# dsp_ice_rev2_release.net
KiCad netlist of a schematic drawn in EAGLE
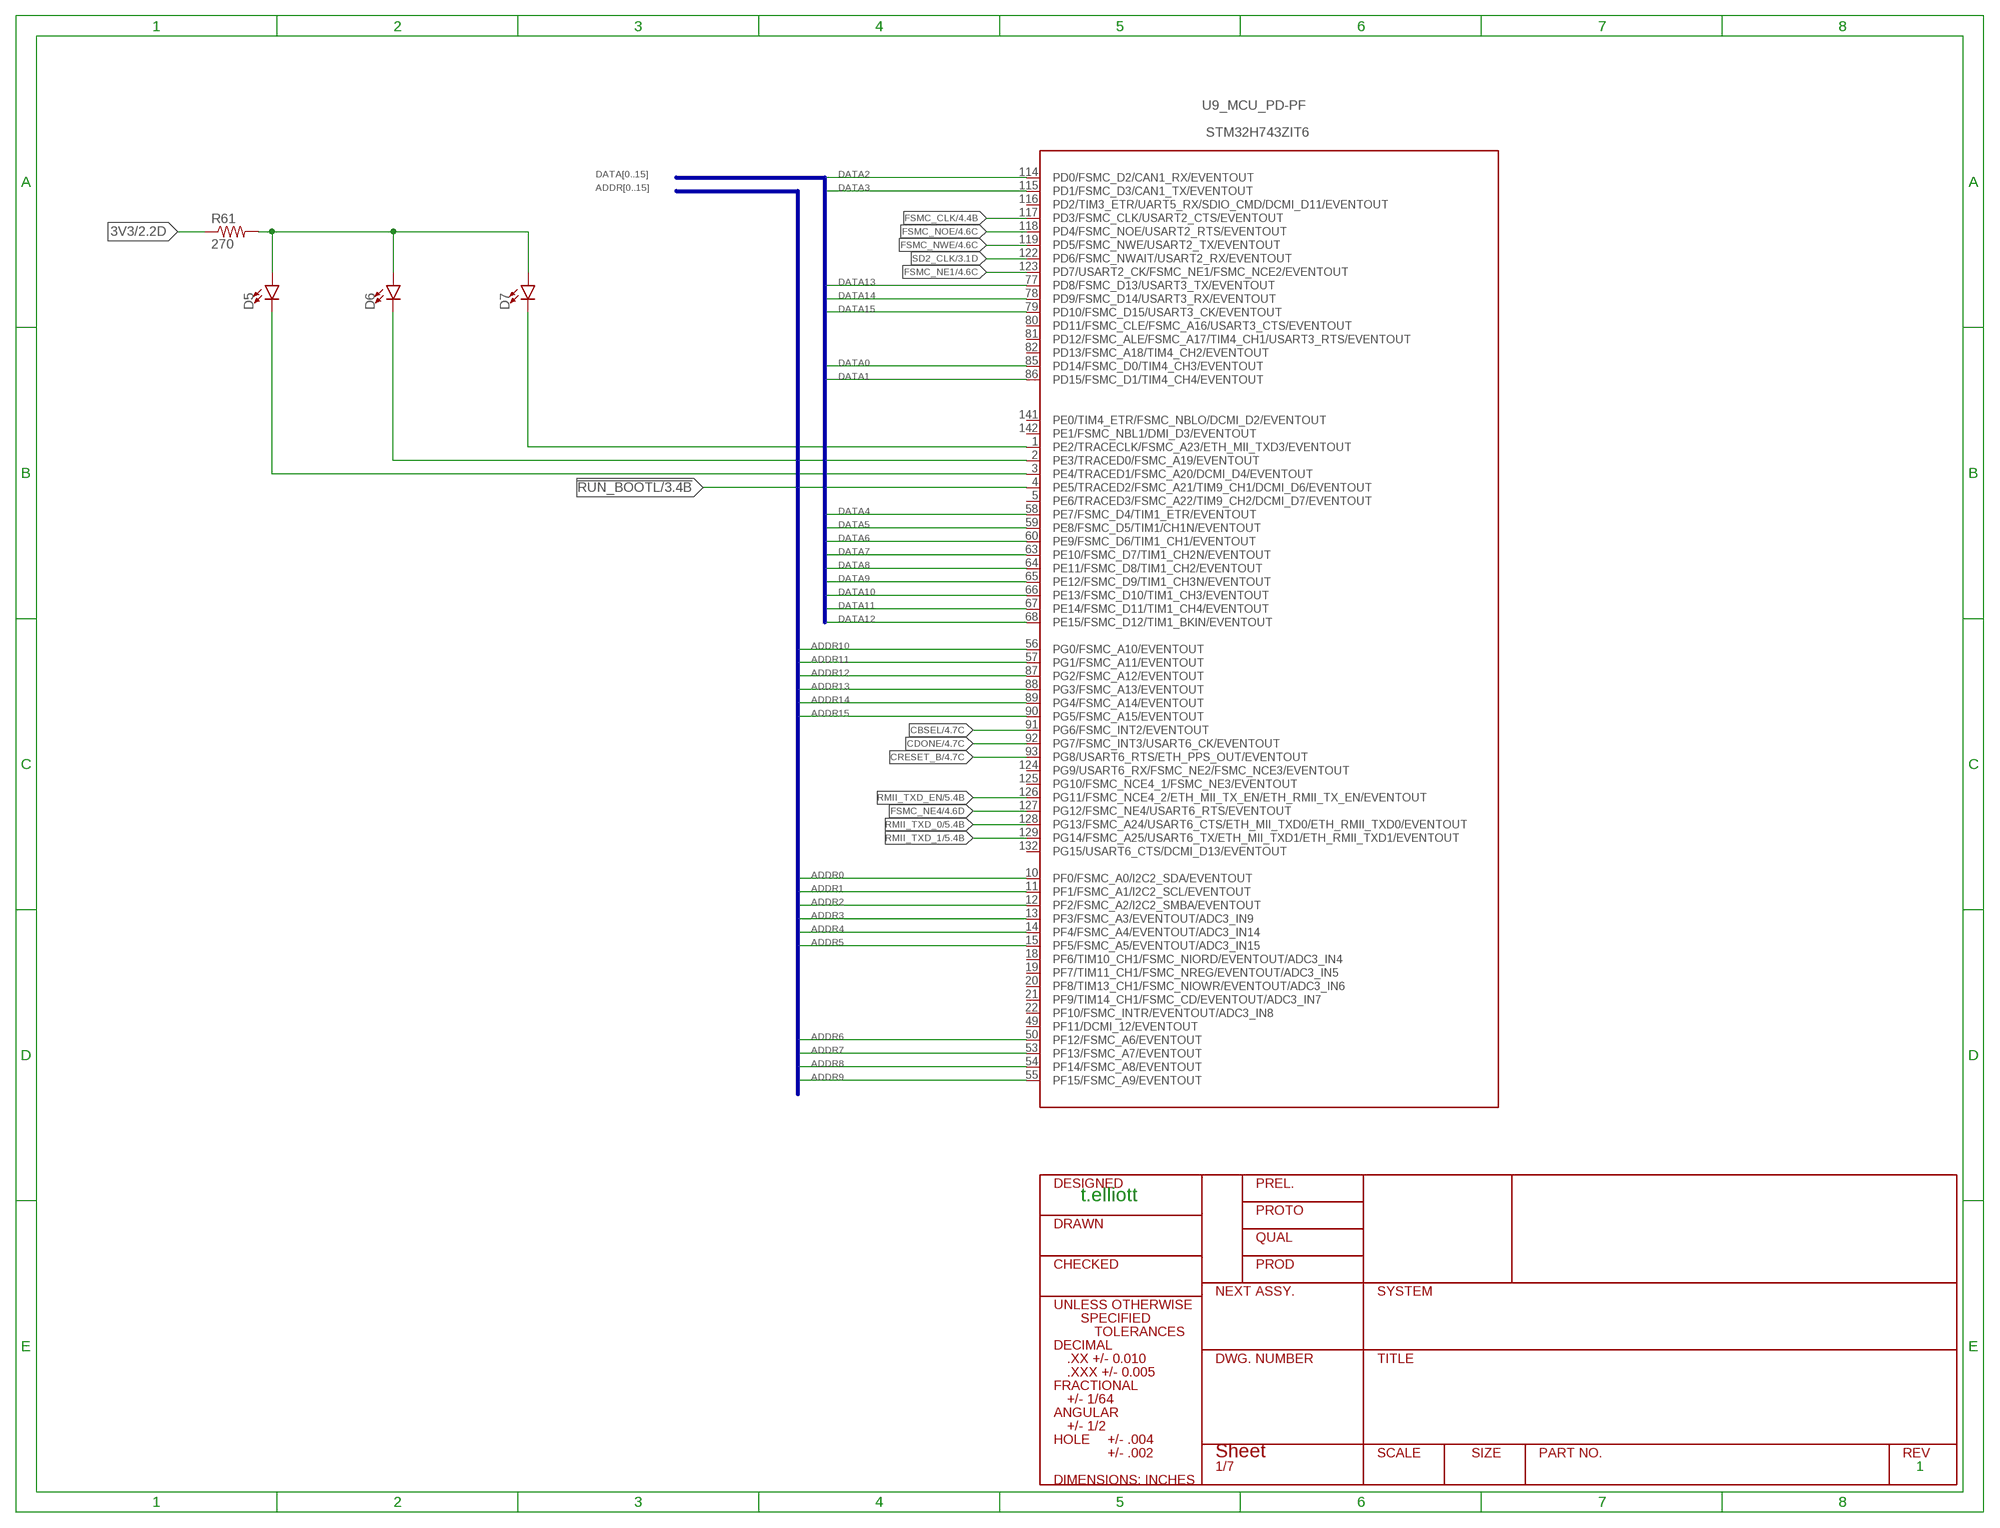
[diagram p0: schematic, sheet 1]
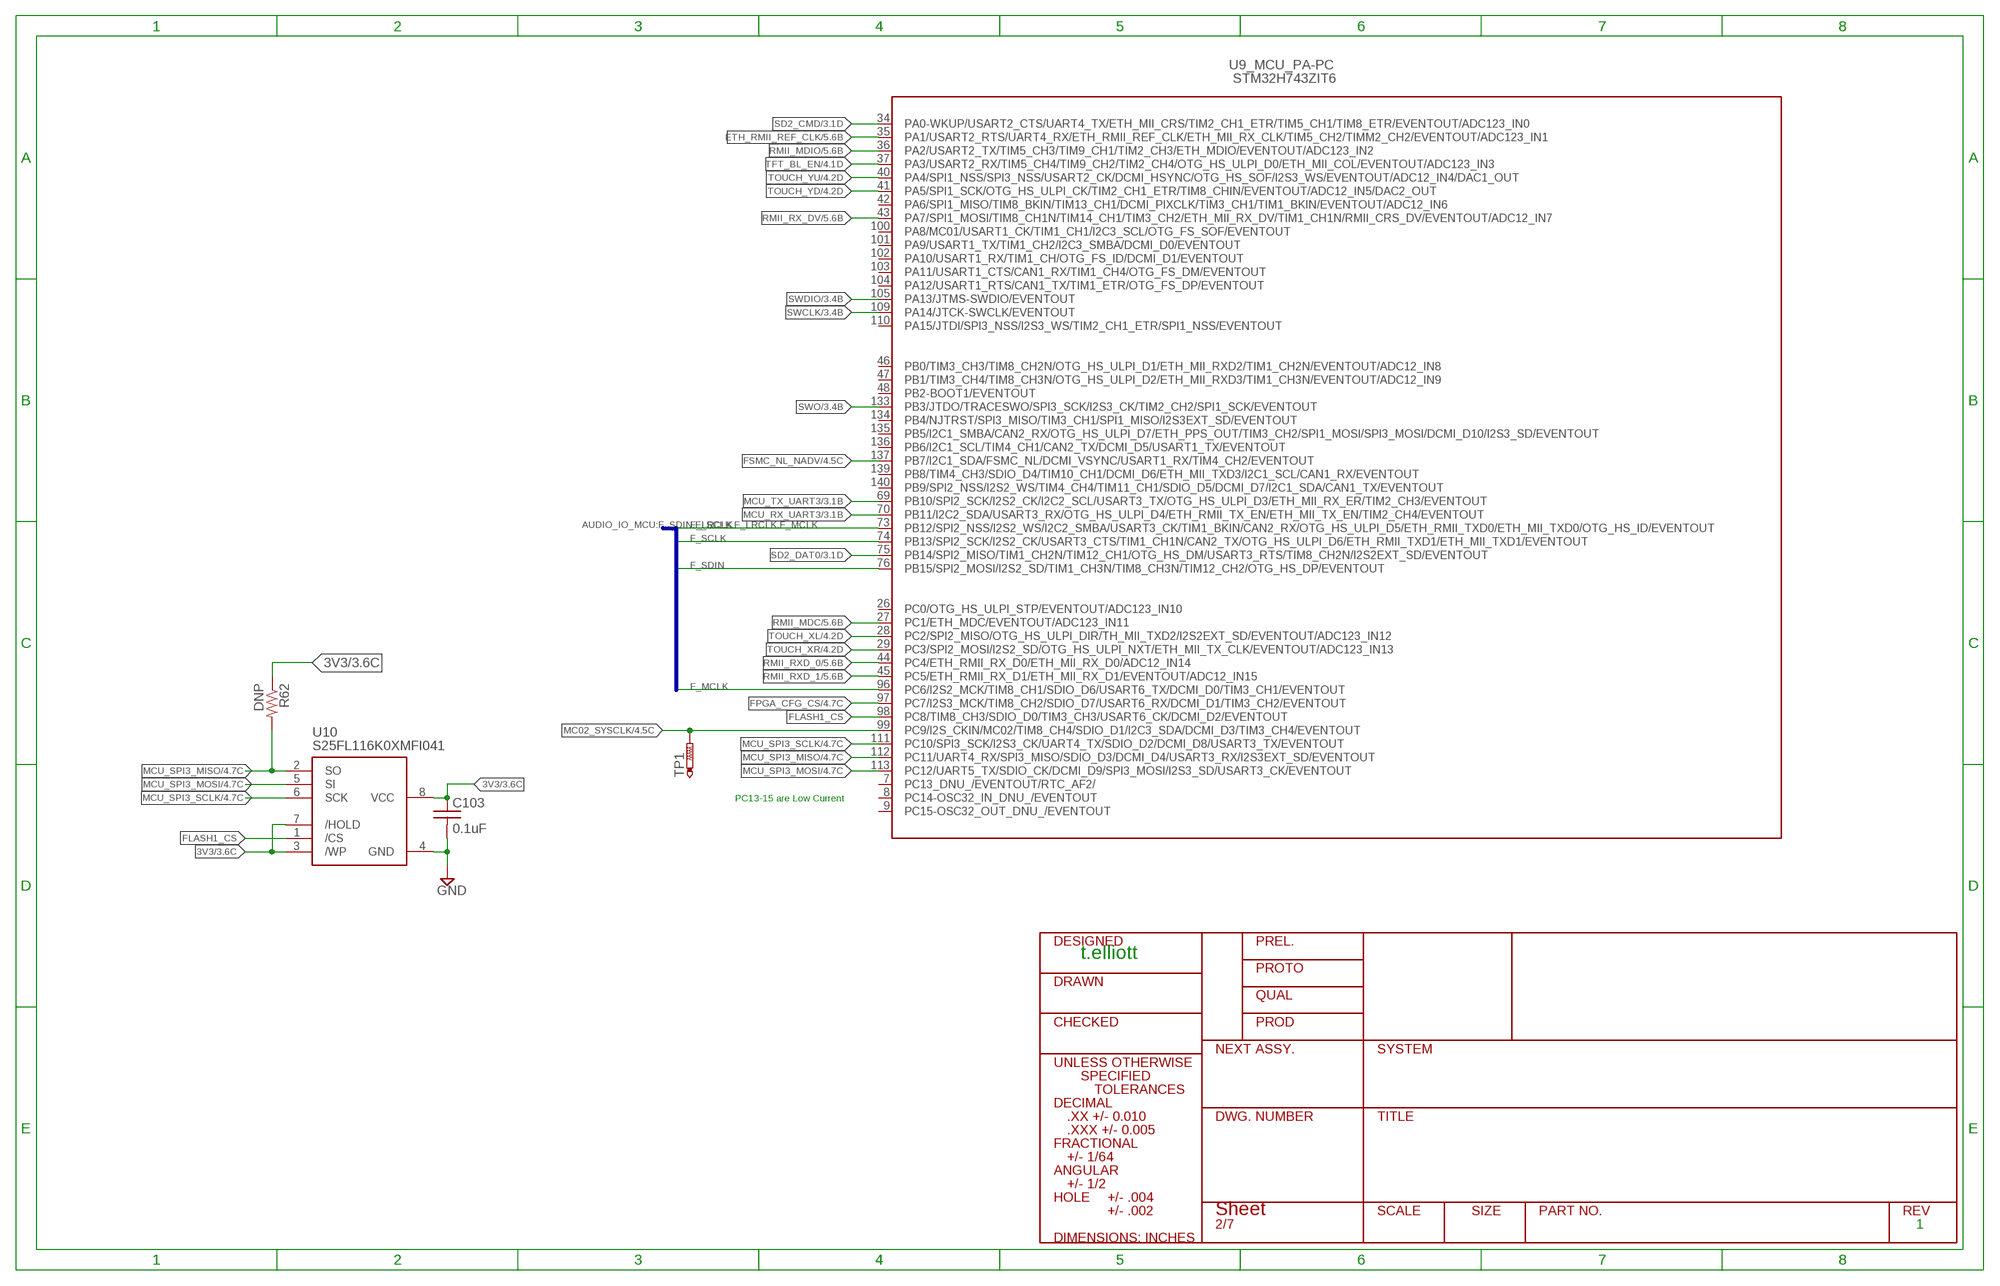
[diagram p1: schematic, sheet 2]
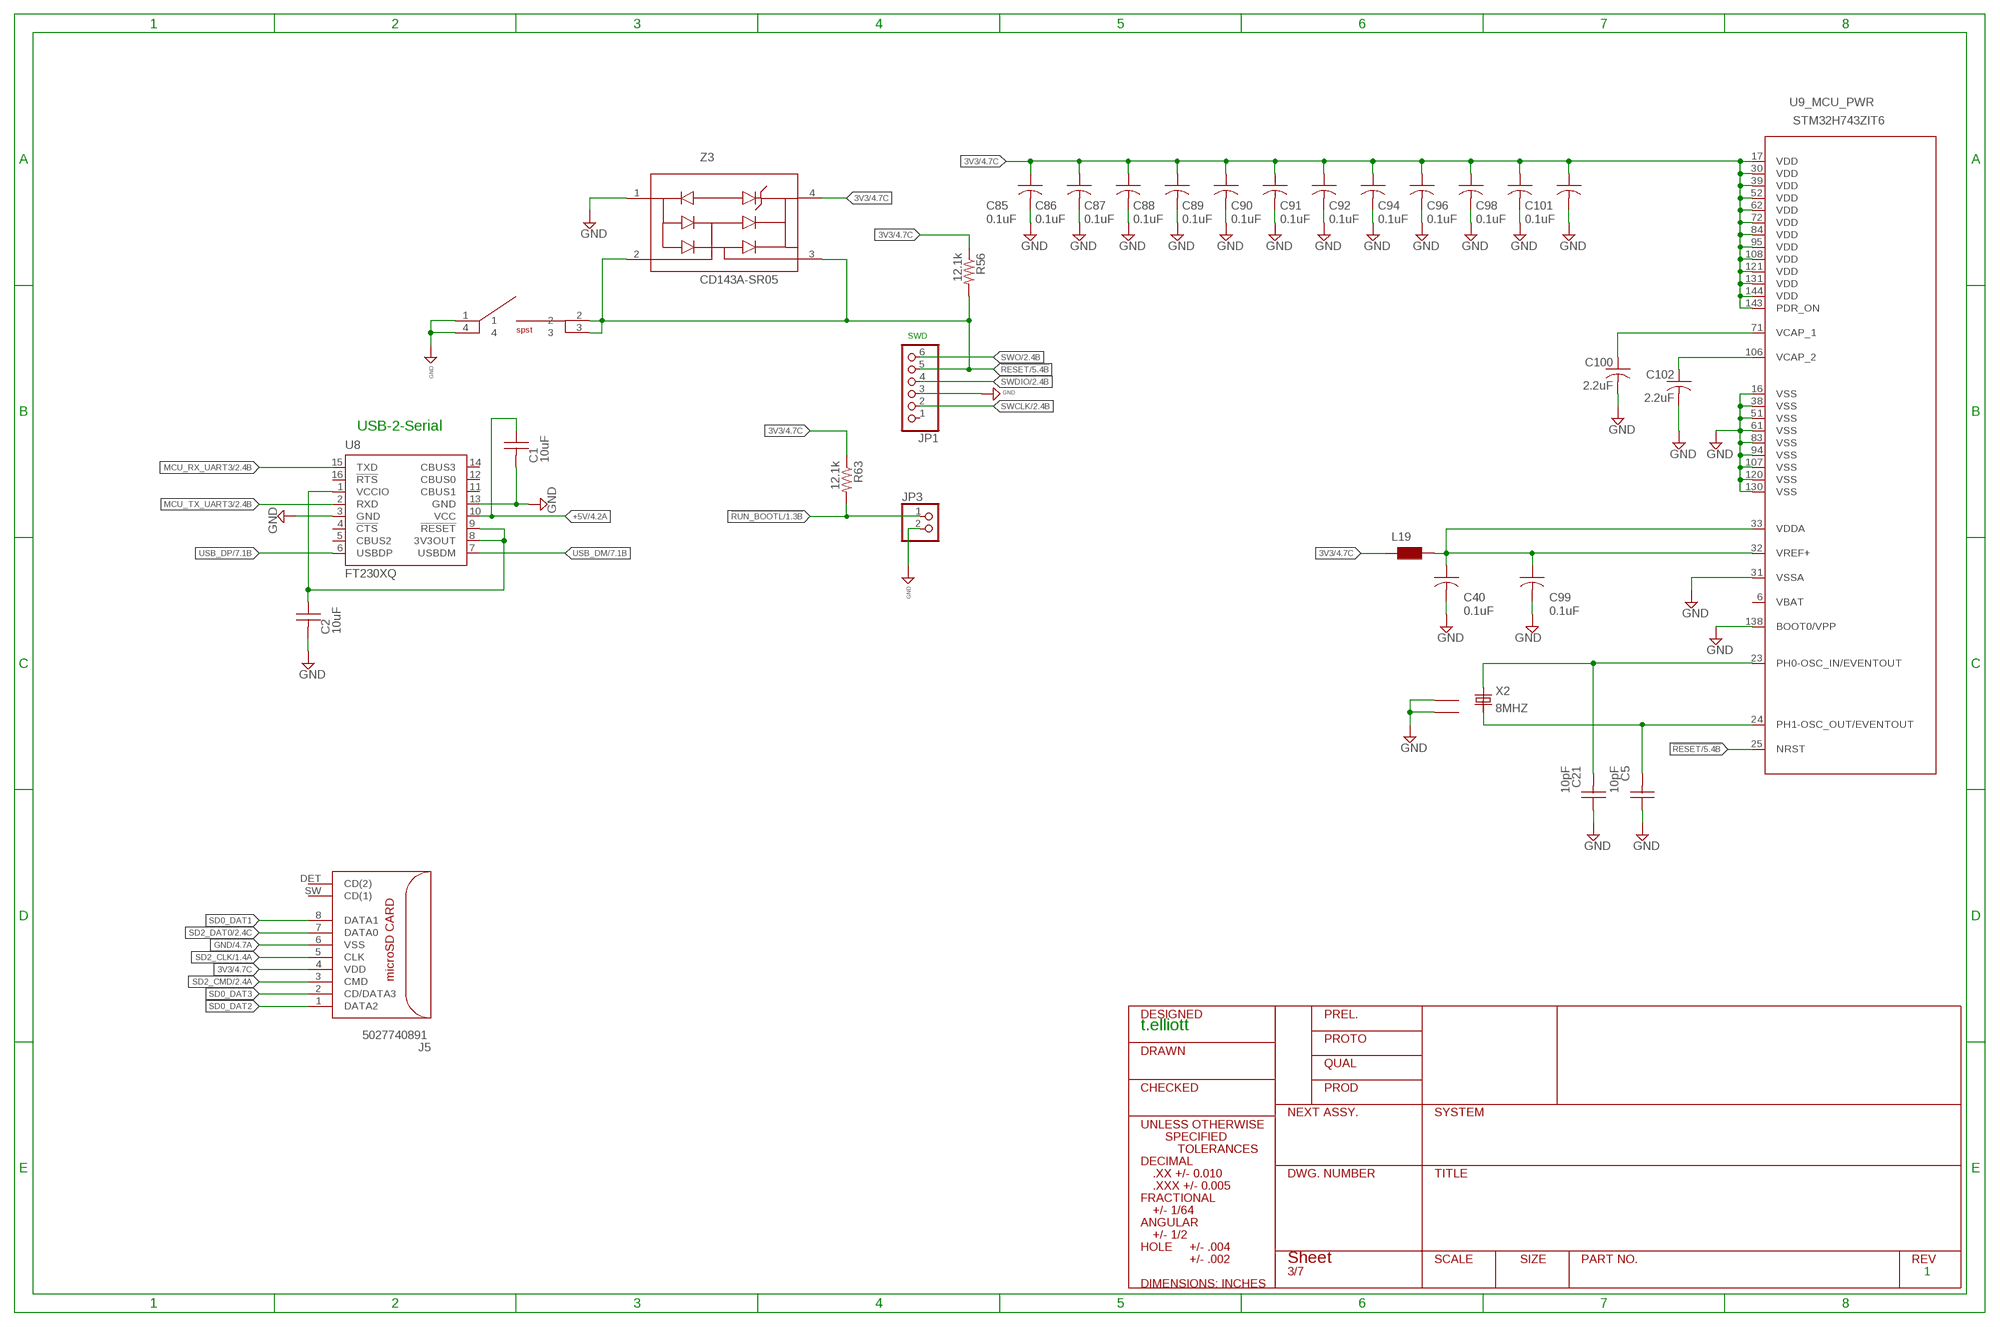
[diagram p2: schematic, sheet 3]
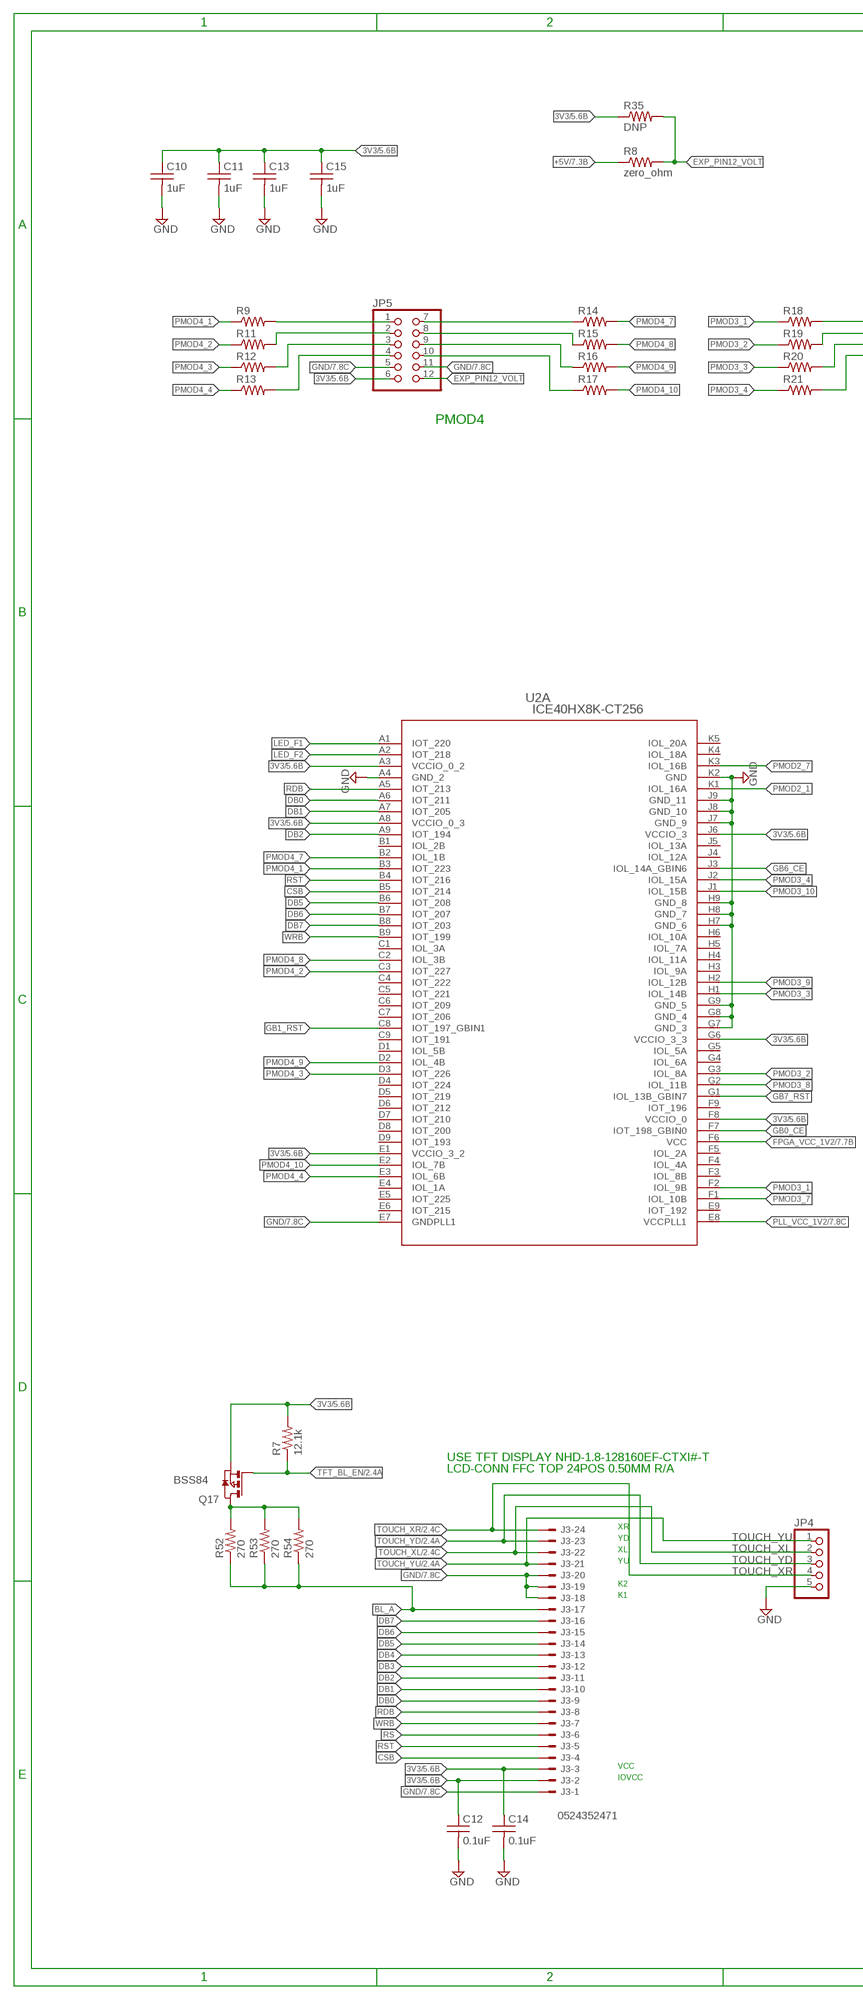
[diagram p3: schematic, sheet 4, part 1 of 2]
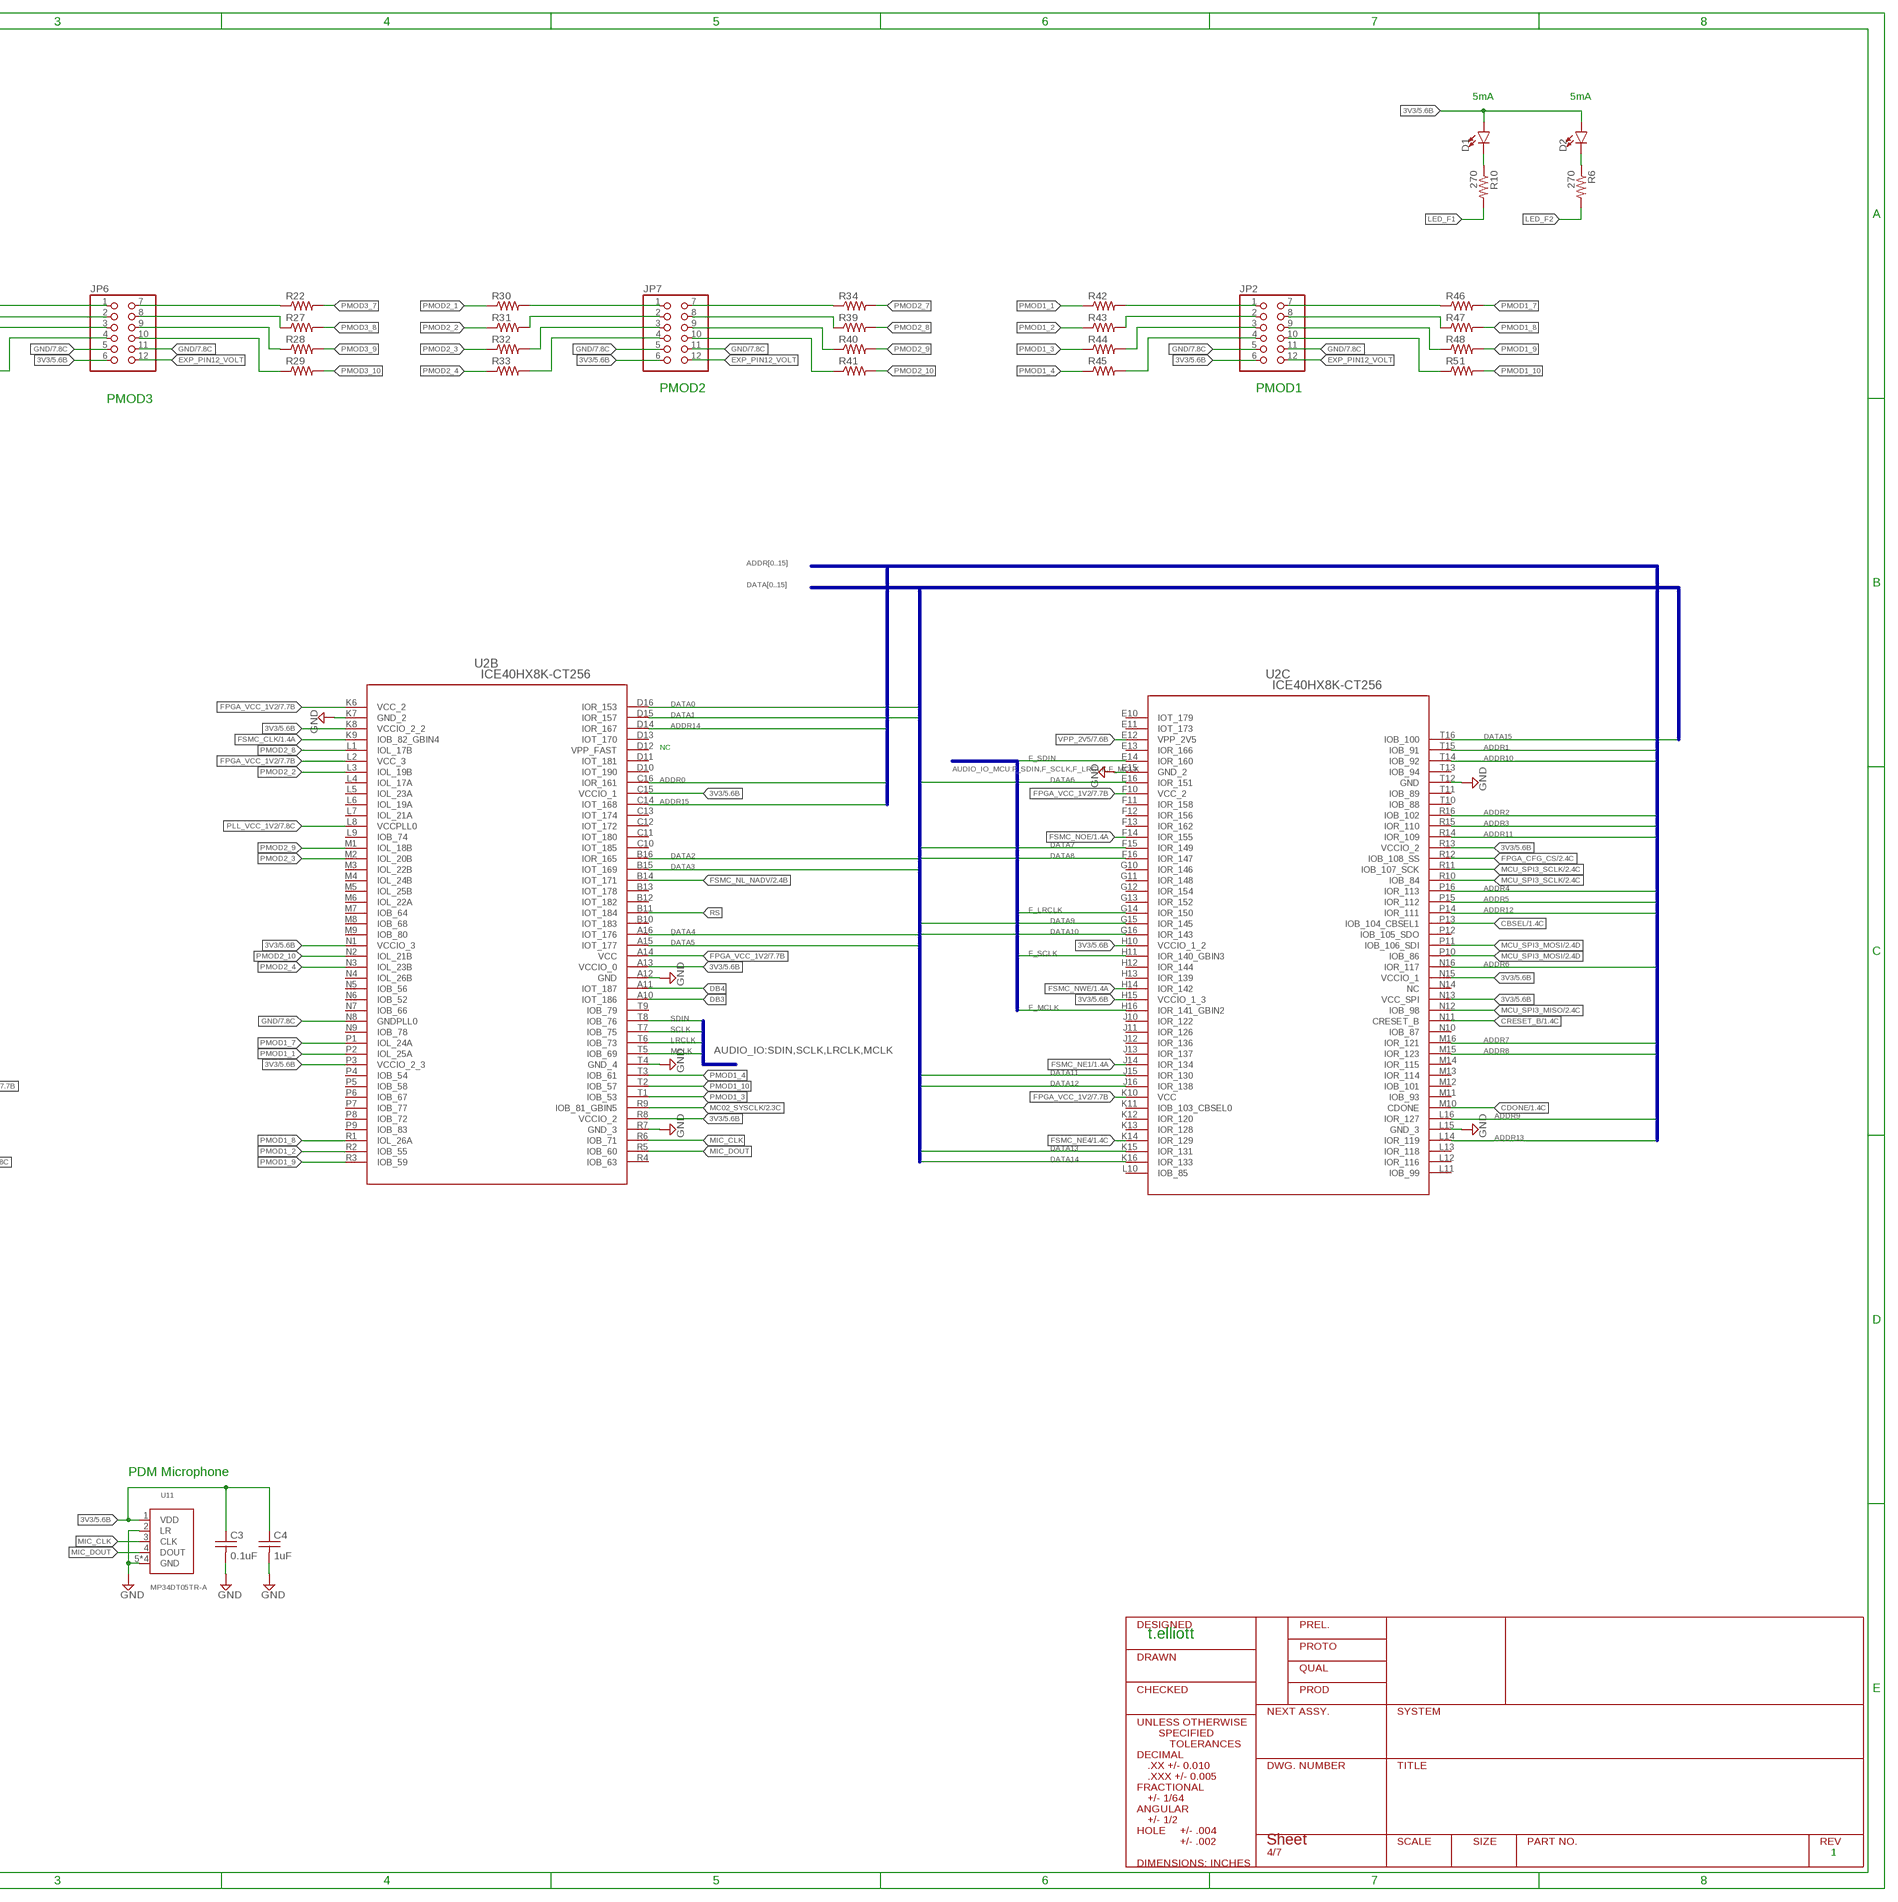
[diagram p4: schematic, sheet 4, part 2 of 2]
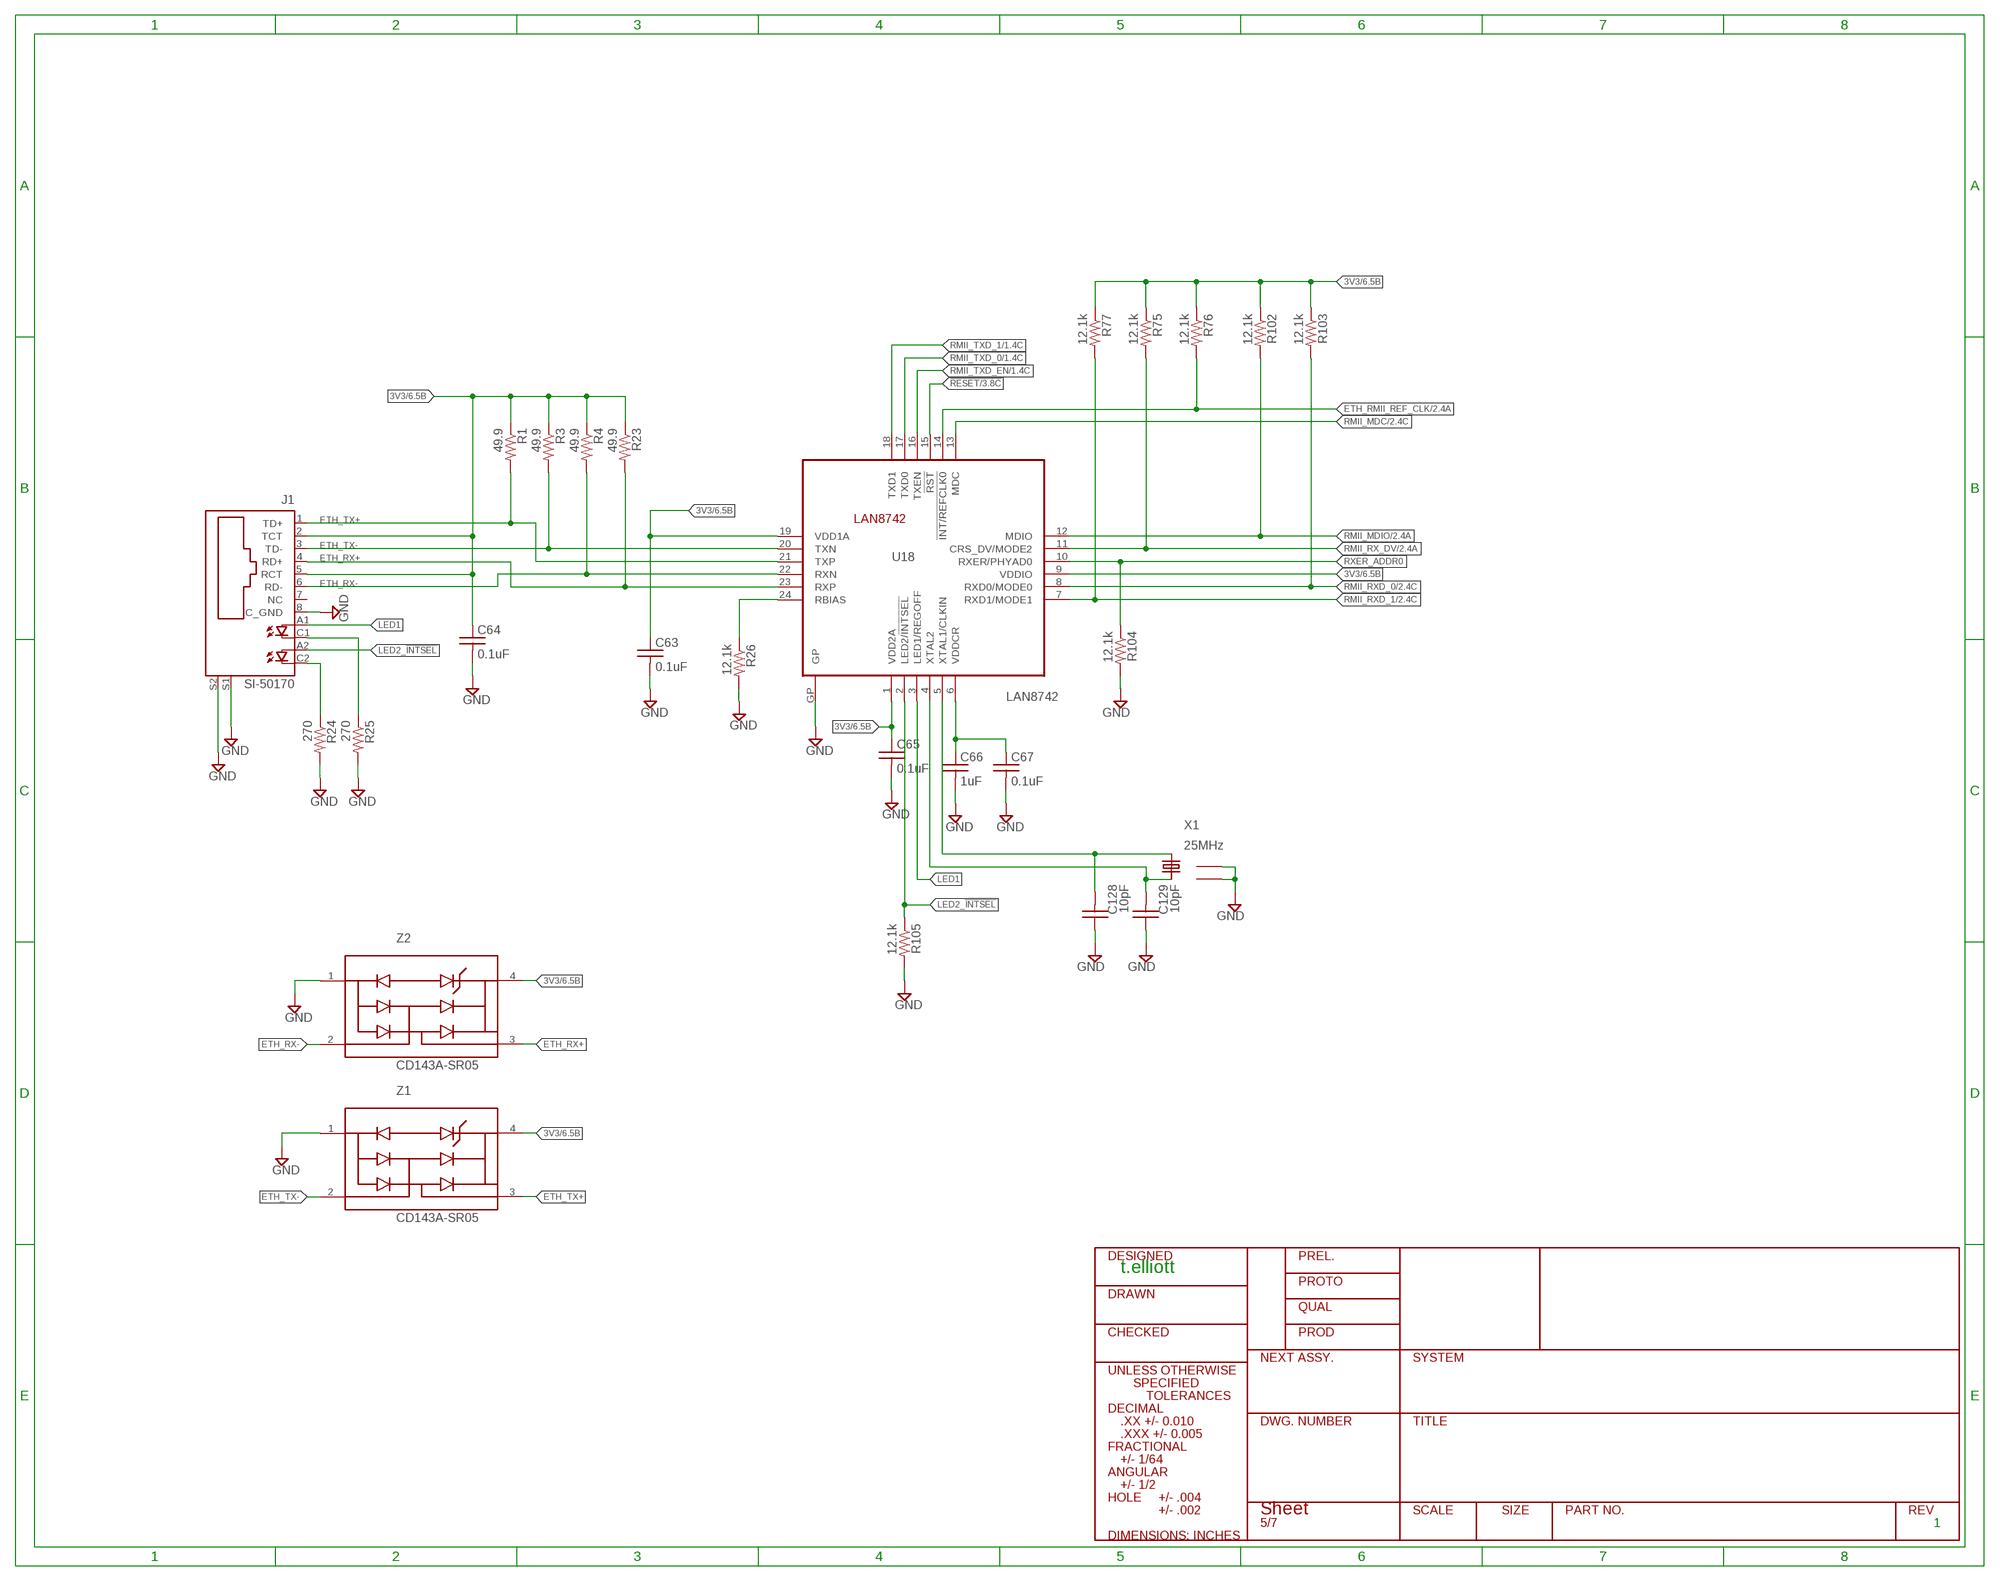
[diagram p5: schematic, sheet 5]
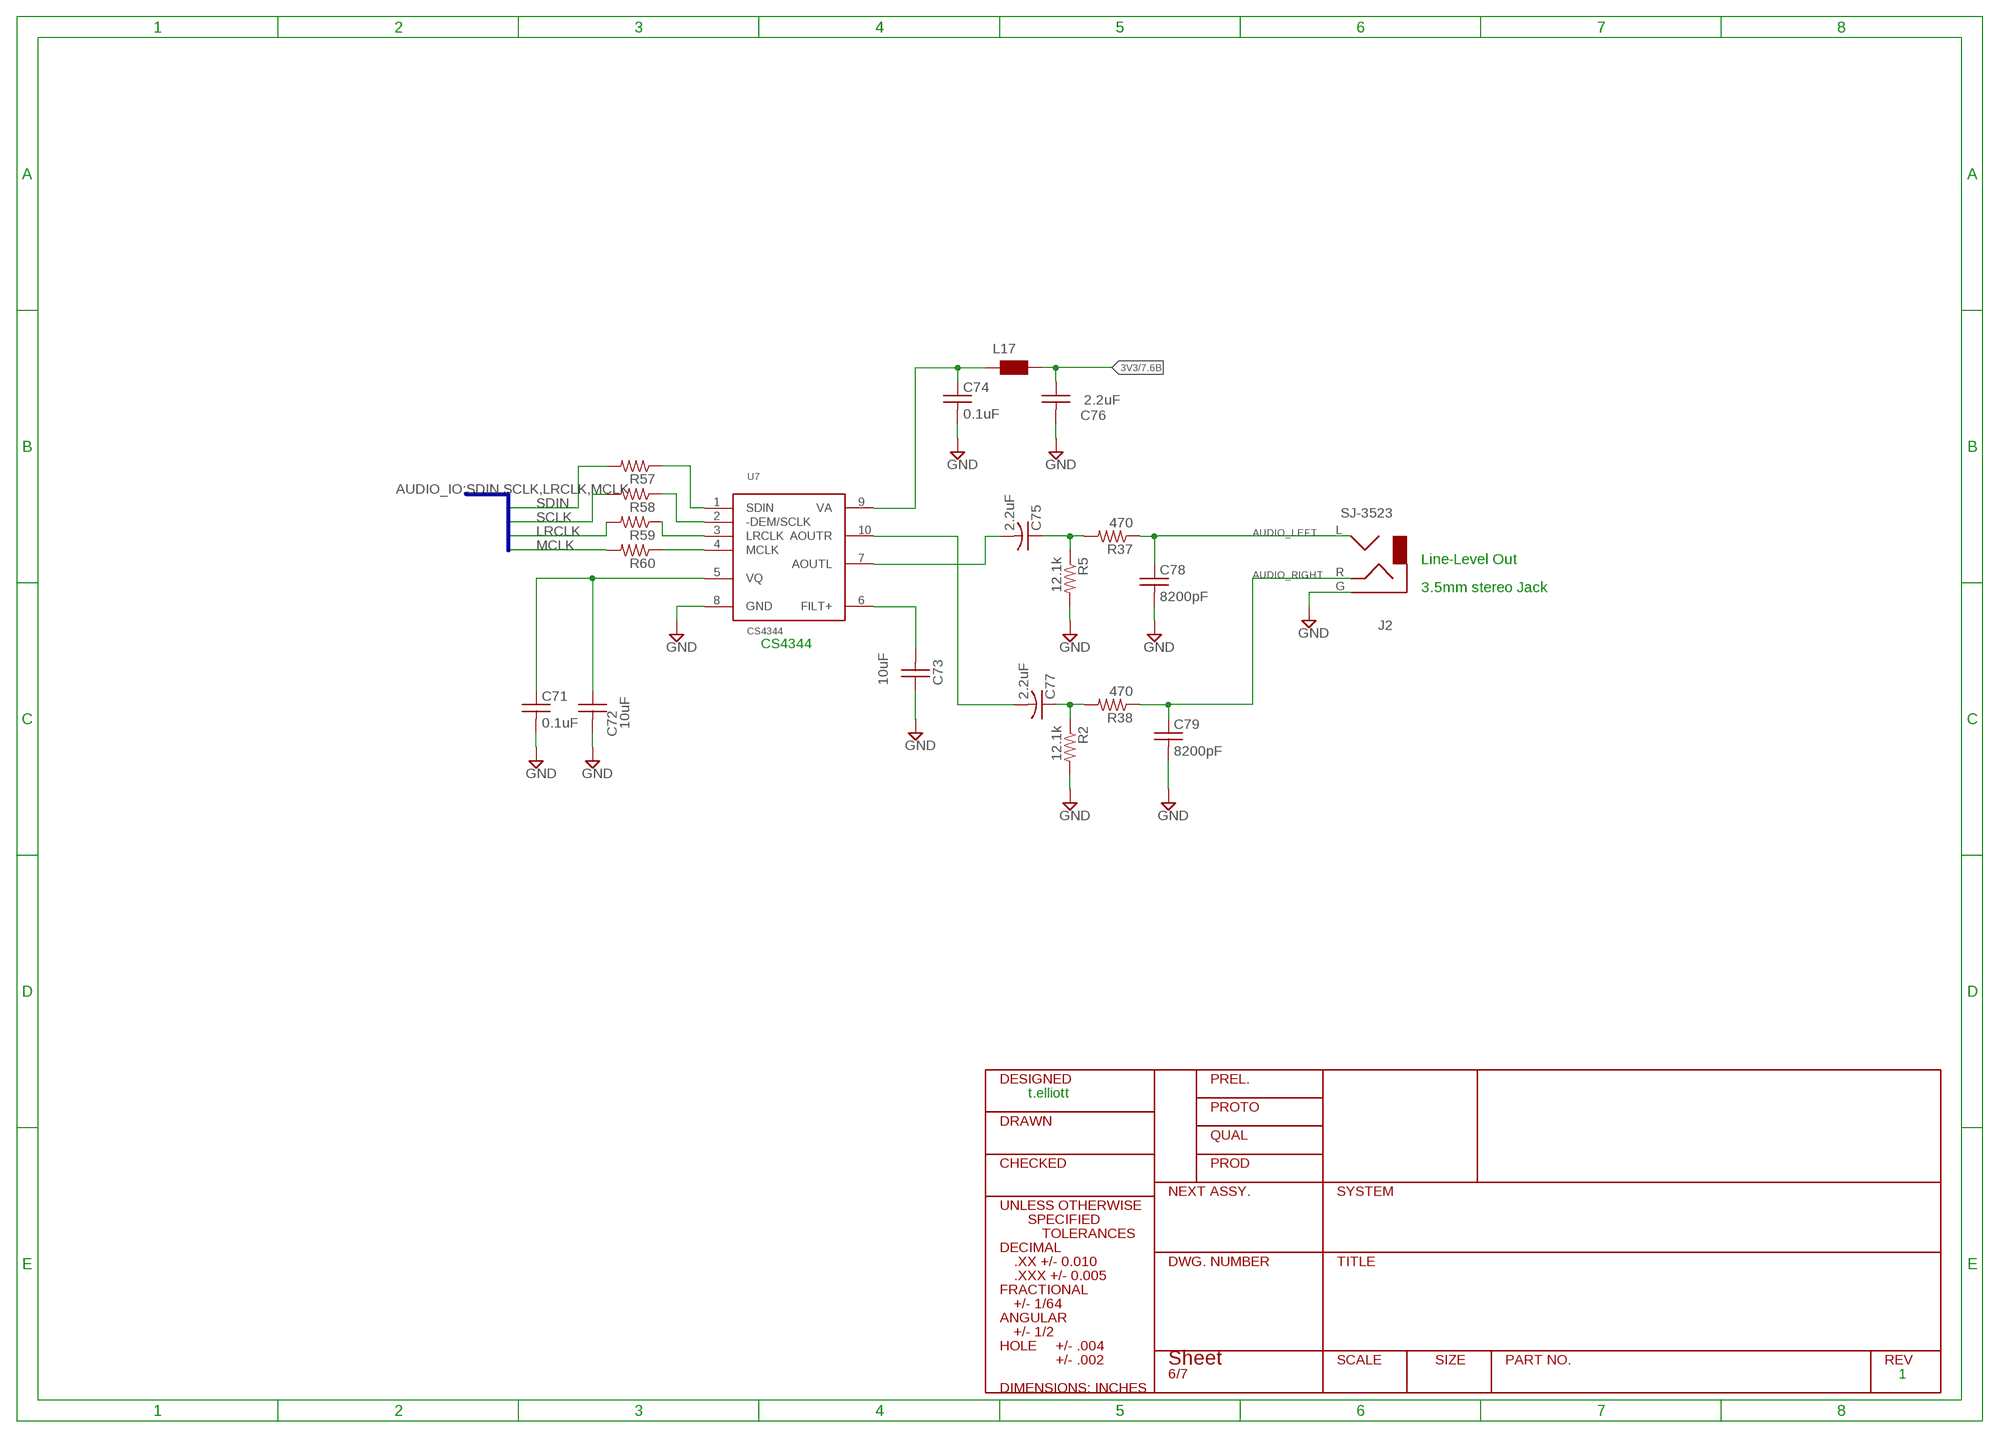
[diagram p6: schematic, sheet 6]
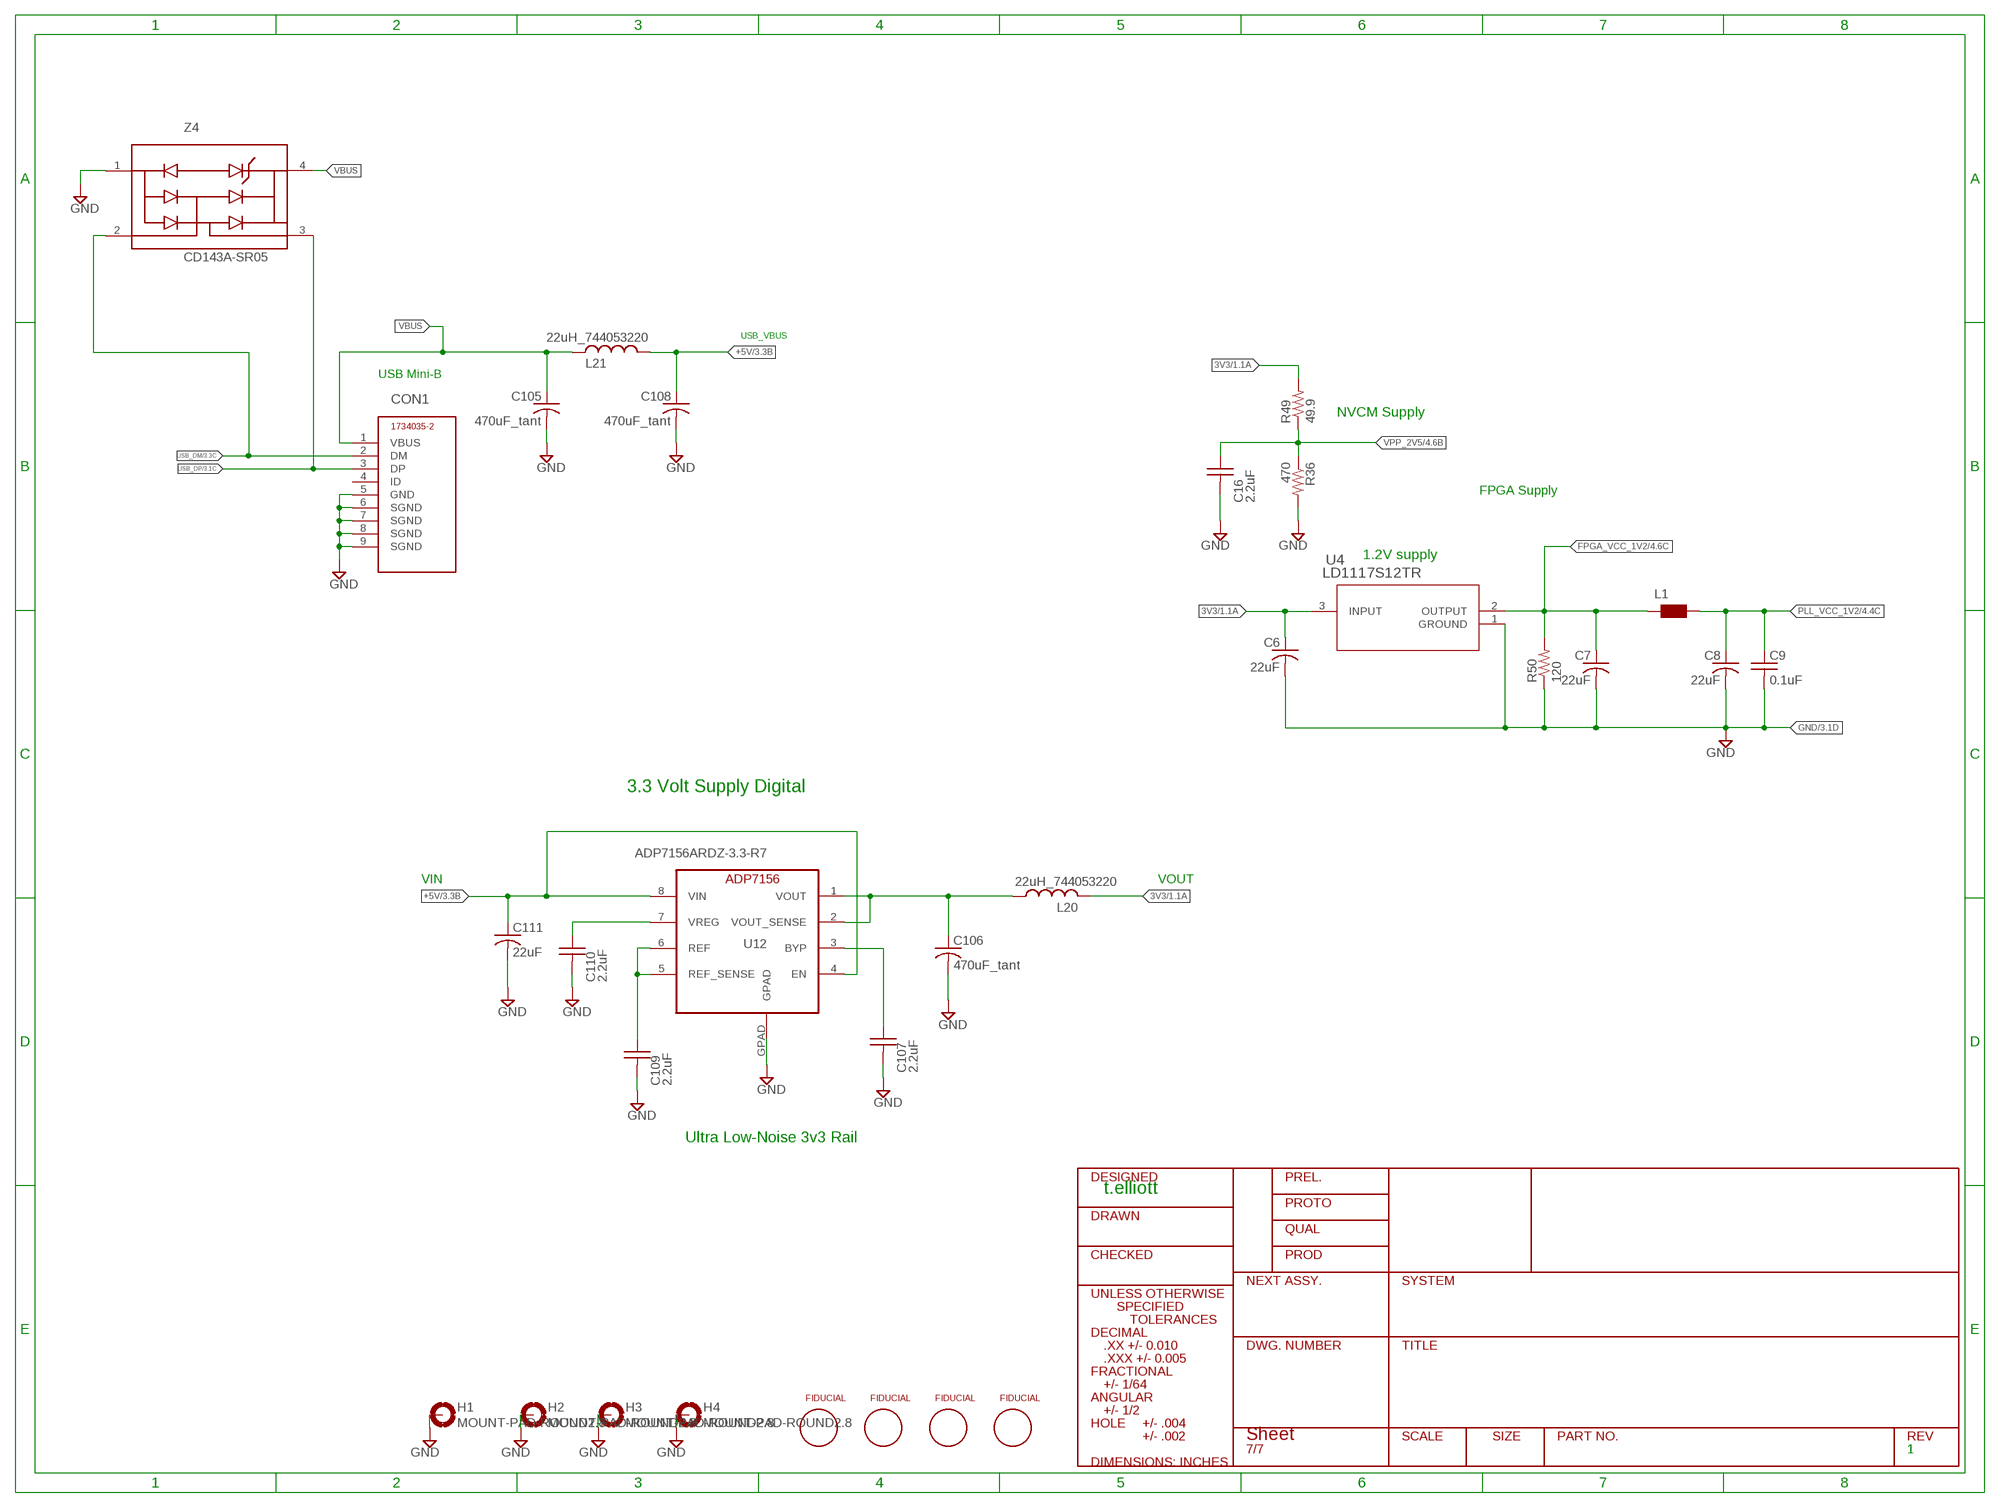
[diagram p7: schematic, sheet 7]

(export (version "E")
  (design (tool "Eeschema 10.0.6"))
  (components
    (comp (ref "C3")
      (value "0.1uF")
      (footprint "eagle-import:C0603")
      (libsource (lib "eagle-import") (part "C-USC0603"))
    )
    (comp (ref "C4")
      (value "1uF")
      (footprint "eagle-import:C0603")
      (libsource (lib "eagle-import") (part "C-USC0603"))
    )
    (comp (ref "C10")
      (value "1uF")
      (footprint "eagle-import:C0603")
      (libsource (lib "eagle-import") (part "C-USC0603"))
    )
    (comp (ref "C11")
      (value "1uF")
      (footprint "eagle-import:C0603")
      (libsource (lib "eagle-import") (part "C-USC0603"))
    )
    (comp (ref "C12")
      (value "0.1uF")
      (footprint "eagle-import:C0603")
      (libsource (lib "eagle-import") (part "C-USC0603"))
    )
    (comp (ref "C13")
      (value "1uF")
      (footprint "eagle-import:C0603")
      (libsource (lib "eagle-import") (part "C-USC0603"))
    )
    (comp (ref "C14")
      (value "0.1uF")
      (footprint "eagle-import:C0603")
      (libsource (lib "eagle-import") (part "C-USC0603"))
    )
    (comp (ref "C15")
      (value "1uF")
      (footprint "eagle-import:C0603")
      (libsource (lib "eagle-import") (part "C-USC0603"))
    )
    (comp (ref "D1")
      (value "LED1206")
      (footprint "eagle-import:LED-1206")
      (libsource (lib "eagle-import") (part "LED1206"))
    )
    (comp (ref "D2")
      (value "LED1206")
      (footprint "eagle-import:LED-1206")
      (libsource (lib "eagle-import") (part "LED1206"))
    )
    (comp (ref "J3")
      (value "0524352471")
      (footprint "eagle-import:52745-2490")
      (libsource (lib "eagle-import") (part "52745-2490"))
    )
    (comp (ref "JP2")
      (value "PINHD-2X6")
      (footprint "eagle-import:2X06")
      (libsource (lib "eagle-import") (part "PINHD-2X6"))
    )
    (comp (ref "JP4")
      (value "PINHD-1X5")
      (footprint "eagle-import:1X05")
      (libsource (lib "eagle-import") (part "PINHD-1X5"))
    )
    (comp (ref "JP5")
      (value "PINHD-2X6")
      (footprint "eagle-import:2X06")
      (libsource (lib "eagle-import") (part "PINHD-2X6"))
    )
    (comp (ref "JP6")
      (value "PINHD-2X6")
      (footprint "eagle-import:2X06")
      (libsource (lib "eagle-import") (part "PINHD-2X6"))
    )
    (comp (ref "JP7")
      (value "PINHD-2X6")
      (footprint "eagle-import:2X06")
      (libsource (lib "eagle-import") (part "PINHD-2X6"))
    )
    (comp (ref "Q17")
      (value "BSS84")
      (footprint "eagle-import:SOT23_BSS84_PACKAGE")
      (libsource (lib "eagle-import") (part "BSS84"))
    )
    (comp (ref "R6")
      (value "270")
      (footprint "eagle-import:R0603")
      (libsource (lib "eagle-import") (part "R-US_R0603"))
    )
    (comp (ref "R7")
      (value "12.1k")
      (footprint "eagle-import:R0603")
      (libsource (lib "eagle-import") (part "R-US_R0603"))
    )
    (comp (ref "R8")
      (value "zero_ohm")
      (footprint "eagle-import:R1206W")
      (libsource (lib "eagle-import") (part "R-US_R1206W"))
    )
    (comp (ref "R9")
      (value "10")
      (footprint "eagle-import:R0603")
      (libsource (lib "eagle-import") (part "R-US_R0603"))
    )
    (comp (ref "R10")
      (value "270")
      (footprint "eagle-import:R0603")
      (libsource (lib "eagle-import") (part "R-US_R0603"))
    )
    (comp (ref "R11")
      (value "10")
      (footprint "eagle-import:R0603")
      (libsource (lib "eagle-import") (part "R-US_R0603"))
    )
    (comp (ref "R12")
      (value "10")
      (footprint "eagle-import:R0603")
      (libsource (lib "eagle-import") (part "R-US_R0603"))
    )
    (comp (ref "R13")
      (value "10")
      (footprint "eagle-import:R0603")
      (libsource (lib "eagle-import") (part "R-US_R0603"))
    )
    (comp (ref "R14")
      (value "10")
      (footprint "eagle-import:R0603")
      (libsource (lib "eagle-import") (part "R-US_R0603"))
    )
    (comp (ref "R15")
      (value "10")
      (footprint "eagle-import:R0603")
      (libsource (lib "eagle-import") (part "R-US_R0603"))
    )
    (comp (ref "R16")
      (value "10")
      (footprint "eagle-import:R0603")
      (libsource (lib "eagle-import") (part "R-US_R0603"))
    )
    (comp (ref "R17")
      (value "10")
      (footprint "eagle-import:R0603")
      (libsource (lib "eagle-import") (part "R-US_R0603"))
    )
    (comp (ref "R18")
      (value "10")
      (footprint "eagle-import:R0603")
      (libsource (lib "eagle-import") (part "R-US_R0603"))
    )
    (comp (ref "R19")
      (value "10")
      (footprint "eagle-import:R0603")
      (libsource (lib "eagle-import") (part "R-US_R0603"))
    )
    (comp (ref "R20")
      (value "10")
      (footprint "eagle-import:R0603")
      (libsource (lib "eagle-import") (part "R-US_R0603"))
    )
    (comp (ref "R21")
      (value "10")
      (footprint "eagle-import:R0603")
      (libsource (lib "eagle-import") (part "R-US_R0603"))
    )
    (comp (ref "R22")
      (value "10")
      (footprint "eagle-import:R0603")
      (libsource (lib "eagle-import") (part "R-US_R0603"))
    )
    (comp (ref "R27")
      (value "10")
      (footprint "eagle-import:R0603")
      (libsource (lib "eagle-import") (part "R-US_R0603"))
    )
    (comp (ref "R28")
      (value "10")
      (footprint "eagle-import:R0603")
      (libsource (lib "eagle-import") (part "R-US_R0603"))
    )
    (comp (ref "R29")
      (value "10")
      (footprint "eagle-import:R0603")
      (libsource (lib "eagle-import") (part "R-US_R0603"))
    )
    (comp (ref "R30")
      (value "10")
      (footprint "eagle-import:R0603")
      (libsource (lib "eagle-import") (part "R-US_R0603"))
    )
    (comp (ref "R31")
      (value "10")
      (footprint "eagle-import:R0603")
      (libsource (lib "eagle-import") (part "R-US_R0603"))
    )
    (comp (ref "R32")
      (value "10")
      (footprint "eagle-import:R0603")
      (libsource (lib "eagle-import") (part "R-US_R0603"))
    )
    (comp (ref "R33")
      (value "10")
      (footprint "eagle-import:R0603")
      (libsource (lib "eagle-import") (part "R-US_R0603"))
    )
    (comp (ref "R34")
      (value "10")
      (footprint "eagle-import:R0603")
      (libsource (lib "eagle-import") (part "R-US_R0603"))
    )
    (comp (ref "R35")
      (value "DNP")
      (footprint "eagle-import:R1206W")
      (libsource (lib "eagle-import") (part "R-US_R1206W"))
    )
    (comp (ref "R39")
      (value "10")
      (footprint "eagle-import:R0603")
      (libsource (lib "eagle-import") (part "R-US_R0603"))
    )
    (comp (ref "R40")
      (value "10")
      (footprint "eagle-import:R0603")
      (libsource (lib "eagle-import") (part "R-US_R0603"))
    )
    (comp (ref "R41")
      (value "10")
      (footprint "eagle-import:R0603")
      (libsource (lib "eagle-import") (part "R-US_R0603"))
    )
    (comp (ref "R42")
      (value "10")
      (footprint "eagle-import:R0603")
      (libsource (lib "eagle-import") (part "R-US_R0603"))
    )
    (comp (ref "R43")
      (value "10")
      (footprint "eagle-import:R0603")
      (libsource (lib "eagle-import") (part "R-US_R0603"))
    )
    (comp (ref "R44")
      (value "10")
      (footprint "eagle-import:R0603")
      (libsource (lib "eagle-import") (part "R-US_R0603"))
    )
    (comp (ref "R45")
      (value "10")
      (footprint "eagle-import:R0603")
      (libsource (lib "eagle-import") (part "R-US_R0603"))
    )
    (comp (ref "R46")
      (value "10")
      (footprint "eagle-import:R0603")
      (libsource (lib "eagle-import") (part "R-US_R0603"))
    )
    (comp (ref "R47")
      (value "10")
      (footprint "eagle-import:R0603")
      (libsource (lib "eagle-import") (part "R-US_R0603"))
    )
    (comp (ref "R48")
      (value "10")
      (footprint "eagle-import:R0603")
      (libsource (lib "eagle-import") (part "R-US_R0603"))
    )
    (comp (ref "R51")
      (value "10")
      (footprint "eagle-import:R0603")
      (libsource (lib "eagle-import") (part "R-US_R0603"))
    )
    (comp (ref "R52")
      (value "270")
      (footprint "eagle-import:R0603")
      (libsource (lib "eagle-import") (part "R-US_R0603"))
    )
    (comp (ref "R53")
      (value "270")
      (footprint "eagle-import:R0603")
      (libsource (lib "eagle-import") (part "R-US_R0603"))
    )
    (comp (ref "R54")
      (value "270")
      (footprint "eagle-import:R0603")
      (libsource (lib "eagle-import") (part "R-US_R0603"))
    )
    (comp (ref "U2")
      (value "ICE40HX8K-CT256")
      (footprint "eagle-import:CABGA256")
      (fields (field (name "MANUFACTURER_PART_NUMBER") "ICE40HX8KCT256"))
      (libsource (lib "eagle-import") (part "ICE40HX8K-CT256"))
    )
    (comp (ref "U11")
      (value "MP34DT05TR-A")
      (footprint "eagle-import:HCLGA5P-3X4X1MM")
      (libsource (lib "eagle-import") (part "MICROPHONE-MP34DT01"))
    )
    (comp (ref "C103")
      (value "0.1uF")
      (footprint "eagle-import:C0603")
      (libsource (lib "eagle-import") (part "misclib3_C-USC0603"))
    )
    (comp (ref "R62")
      (value "DNP")
      (footprint "eagle-import:R0603")
      (libsource (lib "eagle-import") (part "R-US_R0603"))
    )
    (comp (ref "TP1")
      (value "PTR1TP08R")
      (footprint "eagle-import:TP08R")
      (libsource (lib "eagle-import") (part "PTR1TP08R"))
    )
    (comp (ref "U9")
      (value "STM32H743ZIT6")
      (footprint "eagle-import:STM32F407_144")
      (libsource (lib "eagle-import") (part "STM32F407_144_MG144"))
    )
    (comp (ref "U10")
      (value "S25FL116K0XMFI041")
      (footprint "eagle-import:SO8")
      (libsource (lib "eagle-import") (part "AT25F512ASOIC"))
    )
    (comp (ref "C1")
      (value "10uF")
      (footprint "eagle-import:C0805")
      (libsource (lib "eagle-import") (part "misclib3_C-USC0805"))
    )
    (comp (ref "C2")
      (value "10uF")
      (footprint "eagle-import:C0805")
      (libsource (lib "eagle-import") (part "misclib3_C-USC0805"))
    )
    (comp (ref "C5")
      (value "10pF")
      (footprint "eagle-import:C0402")
      (libsource (lib "eagle-import") (part "C-USC0402"))
    )
    (comp (ref "C21")
      (value "10pF")
      (footprint "eagle-import:C0402")
      (libsource (lib "eagle-import") (part "C-USC0402"))
    )
    (comp (ref "C40")
      (value "0.1uF")
      (footprint "eagle-import:0402")
      (libsource (lib "eagle-import") (part "CAPACITOR0402"))
    )
    (comp (ref "C85")
      (value "0.1uF")
      (footprint "eagle-import:0402")
      (libsource (lib "eagle-import") (part "CAPACITOR0402"))
    )
    (comp (ref "C86")
      (value "0.1uF")
      (footprint "eagle-import:0402")
      (libsource (lib "eagle-import") (part "CAPACITOR0402"))
    )
    (comp (ref "C87")
      (value "0.1uF")
      (footprint "eagle-import:0402")
      (libsource (lib "eagle-import") (part "CAPACITOR0402"))
    )
    (comp (ref "C88")
      (value "0.1uF")
      (footprint "eagle-import:0402")
      (libsource (lib "eagle-import") (part "CAPACITOR0402"))
    )
    (comp (ref "C89")
      (value "0.1uF")
      (footprint "eagle-import:0402")
      (libsource (lib "eagle-import") (part "CAPACITOR0402"))
    )
    (comp (ref "C90")
      (value "0.1uF")
      (footprint "eagle-import:0402")
      (libsource (lib "eagle-import") (part "CAPACITOR0402"))
    )
    (comp (ref "C91")
      (value "0.1uF")
      (footprint "eagle-import:0402")
      (libsource (lib "eagle-import") (part "CAPACITOR0402"))
    )
    (comp (ref "C92")
      (value "0.1uF")
      (footprint "eagle-import:0402")
      (libsource (lib "eagle-import") (part "CAPACITOR0402"))
    )
    (comp (ref "C94")
      (value "0.1uF")
      (footprint "eagle-import:0402")
      (libsource (lib "eagle-import") (part "CAPACITOR0402"))
    )
    (comp (ref "C96")
      (value "0.1uF")
      (footprint "eagle-import:0402")
      (libsource (lib "eagle-import") (part "CAPACITOR0402"))
    )
    (comp (ref "C98")
      (value "0.1uF")
      (footprint "eagle-import:0402")
      (libsource (lib "eagle-import") (part "CAPACITOR0402"))
    )
    (comp (ref "C99")
      (value "0.1uF")
      (footprint "eagle-import:0402")
      (libsource (lib "eagle-import") (part "CAPACITOR0402"))
    )
    (comp (ref "C100")
      (value "2.2uF")
      (footprint "eagle-import:C0805")
      (libsource (lib "eagle-import") (part "resistor_C-USC0805"))
    )
    (comp (ref "C101")
      (value "0.1uF")
      (footprint "eagle-import:0402")
      (libsource (lib "eagle-import") (part "CAPACITOR0402"))
    )
    (comp (ref "C102")
      (value "2.2uF")
      (footprint "eagle-import:C0805")
      (libsource (lib "eagle-import") (part "resistor_C-USC0805"))
    )
    (comp (ref "J5")
      (value "5027740891")
      (footprint "eagle-import:SD-502774-001")
      (libsource (lib "eagle-import") (part "SD-502774-001"))
    )
    (comp (ref "JP1")
      (value "PINHD-1X6")
      (footprint "eagle-import:1X06")
      (libsource (lib "eagle-import") (part "PINHD-1X6"))
    )
    (comp (ref "JP3")
      (value "PINHD-1X2")
      (footprint "eagle-import:1X02")
      (libsource (lib "eagle-import") (part "PINHD-1X2"))
    )
    (comp (ref "L19")
      (value "WE-CBF_0603")
      (footprint "eagle-import:0603")
      (libsource (lib "eagle-import") (part "WE-CBF_0603"))
    )
    (comp (ref "R56")
      (value "12.1k")
      (footprint "eagle-import:R0603")
      (libsource (lib "eagle-import") (part "R-US_R0603"))
    )
    (comp (ref "R63")
      (value "12.1k")
      (footprint "eagle-import:R0603")
      (libsource (lib "eagle-import") (part "R-US_R0603"))
    )
    (comp (ref "SW3")
      (value "HOKURIKU_KSM06_6X6MM_SWITCH1")
      (footprint "eagle-import:TACTILE_6X6MM")
      (libsource (lib "eagle-import") (part "HOKURIKU_KSM06_6X6MM_SWITCH1"))
    )
    (comp (ref "U8")
      (value "FT230XQ")
      (footprint "eagle-import:QFN16")
      (libsource (lib "eagle-import") (part "FT230XQ"))
    )
    (comp (ref "X2")
      (value "8MHZ")
      (footprint "eagle-import:ECS-250-20-30B-DU_CRYSTAL")
      (libsource (lib "eagle-import") (part "ECS-250-20-30B-DUDU"))
    )
    (comp (ref "Z3")
      (value "CD143A-SR05")
      (footprint "eagle-import:SR2.8.TCT_1PRIMARY")
      (libsource (lib "eagle-import") (part "SR2.8_TVS"))
    )
    (comp (ref "D5")
      (value "LED1206")
      (footprint "eagle-import:LED-1206")
      (libsource (lib "eagle-import") (part "LED1206"))
    )
    (comp (ref "D6")
      (value "LED1206")
      (footprint "eagle-import:LED-1206")
      (libsource (lib "eagle-import") (part "LED1206"))
    )
    (comp (ref "D7")
      (value "LED1206")
      (footprint "eagle-import:LED-1206")
      (libsource (lib "eagle-import") (part "LED1206"))
    )
    (comp (ref "R61")
      (value "270")
      (footprint "eagle-import:R0603")
      (libsource (lib "eagle-import") (part "R-US_R0603"))
    )
    (comp (ref "C6")
      (value "22uF")
      (footprint "eagle-import:1210K")
      (libsource (lib "eagle-import") (part "CAPACITOR1210K"))
    )
    (comp (ref "C7")
      (value "22uF")
      (footprint "eagle-import:1210K")
      (libsource (lib "eagle-import") (part "CAPACITOR1210K"))
    )
    (comp (ref "C8")
      (value "22uF")
      (footprint "eagle-import:1210K")
      (libsource (lib "eagle-import") (part "CAPACITOR1210K"))
    )
    (comp (ref "C9")
      (value "0.1uF")
      (footprint "eagle-import:C0603")
      (libsource (lib "eagle-import") (part "misclib3_C-USC0603"))
    )
    (comp (ref "C16")
      (value "2.2uF")
      (footprint "eagle-import:C0805")
      (libsource (lib "eagle-import") (part "misclib3_C-USC0805"))
    )
    (comp (ref "C105")
      (value "470uF_tant")
      (footprint "eagle-import:1210K")
      (libsource (lib "eagle-import") (part "CAPACITOR1210K"))
    )
    (comp (ref "C106")
      (value "470uF_tant")
      (footprint "eagle-import:1210K")
      (libsource (lib "eagle-import") (part "CAPACITOR1210K"))
    )
    (comp (ref "C107")
      (value "2.2uF")
      (footprint "eagle-import:C0805")
      (libsource (lib "eagle-import") (part "misclib3_C-USC0805"))
    )
    (comp (ref "C108")
      (value "470uF_tant")
      (footprint "eagle-import:1210K")
      (libsource (lib "eagle-import") (part "CAPACITOR1210K"))
    )
    (comp (ref "C109")
      (value "2.2uF")
      (footprint "eagle-import:C0805")
      (libsource (lib "eagle-import") (part "misclib3_C-USC0805"))
    )
    (comp (ref "C110")
      (value "2.2uF")
      (footprint "eagle-import:C0805")
      (libsource (lib "eagle-import") (part "misclib3_C-USC0805"))
    )
    (comp (ref "C111")
      (value "22uF")
      (footprint "eagle-import:1210K")
      (libsource (lib "eagle-import") (part "CAPACITOR1210K"))
    )
    (comp (ref "CON1")
      (value "1734035-2")
      (footprint "eagle-import:1734035-2")
      (libsource (lib "eagle-import") (part "1734035-2"))
    )
    (comp (ref "FID1")
      (value "FIDUCIALSMD")
      (footprint "eagle-import:FIDUCIAL")
      (libsource (lib "eagle-import") (part "FIDUCIALSMD"))
    )
    (comp (ref "FID2")
      (value "FIDUCIALSMD")
      (footprint "eagle-import:FIDUCIAL")
      (libsource (lib "eagle-import") (part "FIDUCIALSMD"))
    )
    (comp (ref "FID3")
      (value "FIDUCIALSMD")
      (footprint "eagle-import:FIDUCIAL")
      (libsource (lib "eagle-import") (part "FIDUCIALSMD"))
    )
    (comp (ref "FID4")
      (value "FIDUCIALSMD")
      (footprint "eagle-import:FIDUCIAL")
      (libsource (lib "eagle-import") (part "FIDUCIALSMD"))
    )
    (comp (ref "H1")
      (value "MOUNT-PAD-ROUND2.8")
      (footprint "eagle-import:2,8-PAD")
      (libsource (lib "eagle-import") (part "MOUNT-PAD-ROUND2.8"))
    )
    (comp (ref "H2")
      (value "MOUNT-PAD-ROUND2.8")
      (footprint "eagle-import:2,8-PAD")
      (libsource (lib "eagle-import") (part "MOUNT-PAD-ROUND2.8"))
    )
    (comp (ref "H3")
      (value "MOUNT-PAD-ROUND2.8")
      (footprint "eagle-import:2,8-PAD")
      (libsource (lib "eagle-import") (part "MOUNT-PAD-ROUND2.8"))
    )
    (comp (ref "H4")
      (value "MOUNT-PAD-ROUND2.8")
      (footprint "eagle-import:2,8-PAD")
      (libsource (lib "eagle-import") (part "MOUNT-PAD-ROUND2.8"))
    )
    (comp (ref "L1")
      (value "WE-CBF_0603")
      (footprint "eagle-import:0603")
      (libsource (lib "eagle-import") (part "WE-CBF_0603"))
    )
    (comp (ref "L20")
      (value "22uH_744053220")
      (footprint "eagle-import:POWER-CHOKE_WE-TPC")
      (libsource (lib "eagle-import") (part "L-USWE-TPC"))
    )
    (comp (ref "L21")
      (value "22uH_744053220")
      (footprint "eagle-import:POWER-CHOKE_WE-TPC")
      (libsource (lib "eagle-import") (part "L-USWE-TPC"))
    )
    (comp (ref "R36")
      (value "470")
      (footprint "eagle-import:R0402")
      (libsource (lib "eagle-import") (part "misclib3_R-US_R0402"))
    )
    (comp (ref "R49")
      (value "49.9")
      (footprint "eagle-import:R0603")
      (libsource (lib "eagle-import") (part "R-US_R0603"))
    )
    (comp (ref "R50")
      (value "120")
      (footprint "eagle-import:R0603")
      (libsource (lib "eagle-import") (part "R-US_R0603"))
    )
    (comp (ref "U4")
      (value "LD1117S12TR")
      (footprint "eagle-import:SOT-223")
      (libsource (lib "eagle-import") (part "LD1117S12TR"))
    )
    (comp (ref "U12")
      (value "ADP7156ARDZ-3.3-R7")
      (footprint "eagle-import:SO8")
      (libsource (lib "eagle-import") (part "ADP7156SO8"))
    )
    (comp (ref "Z4")
      (value "CD143A-SR05")
      (footprint "eagle-import:SR2.8.TCT_1PRIMARY")
      (libsource (lib "eagle-import") (part "SR2.8_TVS"))
    )
    (comp (ref "C71")
      (value "0.1uF")
      (footprint "eagle-import:C0603")
      (libsource (lib "eagle-import") (part "misclib3_C-USC0603"))
    )
    (comp (ref "C72")
      (value "10uF")
      (footprint "eagle-import:C0805")
      (libsource (lib "eagle-import") (part "misclib3_C-USC0805"))
    )
    (comp (ref "C73")
      (value "10uF")
      (footprint "eagle-import:C0805")
      (libsource (lib "eagle-import") (part "misclib3_C-USC0805"))
    )
    (comp (ref "C74")
      (value "0.1uF")
      (footprint "eagle-import:C0603")
      (libsource (lib "eagle-import") (part "misclib3_C-USC0603"))
    )
    (comp (ref "C75")
      (value "2.2uF")
      (footprint "eagle-import:C0805")
      (libsource (lib "eagle-import") (part "resistor_C-USC0805"))
    )
    (comp (ref "C76")
      (value "2.2uF")
      (footprint "eagle-import:C0805")
      (libsource (lib "eagle-import") (part "misclib3_C-USC0805"))
    )
    (comp (ref "C77")
      (value "2.2uF")
      (footprint "eagle-import:C0805")
      (libsource (lib "eagle-import") (part "resistor_C-USC0805"))
    )
    (comp (ref "C78")
      (value "8200pF")
      (footprint "eagle-import:C0603")
      (libsource (lib "eagle-import") (part "misclib3_C-USC0603"))
    )
    (comp (ref "C79")
      (value "8200pF")
      (footprint "eagle-import:C0603")
      (libsource (lib "eagle-import") (part "misclib3_C-USC0603"))
    )
    (comp (ref "J2")
      (value "SJ-3523")
      (footprint "eagle-import:SJ-3523")
      (libsource (lib "eagle-import") (part "CUI_SJ-3523SMT"))
    )
    (comp (ref "L17")
      (value "WE-CBF_0603")
      (footprint "eagle-import:0603")
      (libsource (lib "eagle-import") (part "WE-CBF_0603"))
    )
    (comp (ref "R2")
      (value "12.1k")
      (footprint "eagle-import:R0603")
      (libsource (lib "eagle-import") (part "R-US_R0603"))
    )
    (comp (ref "R5")
      (value "12.1k")
      (footprint "eagle-import:R0603")
      (libsource (lib "eagle-import") (part "R-US_R0603"))
    )
    (comp (ref "R37")
      (value "470")
      (footprint "eagle-import:R0402")
      (libsource (lib "eagle-import") (part "misclib3_R-US_R0402"))
    )
    (comp (ref "R38")
      (value "470")
      (footprint "eagle-import:R0402")
      (libsource (lib "eagle-import") (part "misclib3_R-US_R0402"))
    )
    (comp (ref "R57")
      (value "470")
      (footprint "eagle-import:R0402")
      (libsource (lib "eagle-import") (part "misclib3_R-US_R0402"))
    )
    (comp (ref "R58")
      (value "470")
      (footprint "eagle-import:R0402")
      (libsource (lib "eagle-import") (part "misclib3_R-US_R0402"))
    )
    (comp (ref "R59")
      (value "470")
      (footprint "eagle-import:R0402")
      (libsource (lib "eagle-import") (part "misclib3_R-US_R0402"))
    )
    (comp (ref "R60")
      (value "470")
      (footprint "eagle-import:R0402")
      (libsource (lib "eagle-import") (part "misclib3_R-US_R0402"))
    )
    (comp (ref "U7")
      (value "CS4344")
      (footprint "eagle-import:MSOP10")
      (libsource (lib "eagle-import") (part "CS4344"))
    )
    (comp (ref "C63")
      (value "0.1uF")
      (footprint "eagle-import:C0603")
      (libsource (lib "eagle-import") (part "C-USC0603"))
    )
    (comp (ref "C64")
      (value "0.1uF")
      (footprint "eagle-import:C0603")
      (libsource (lib "eagle-import") (part "C-USC0603"))
    )
    (comp (ref "C65")
      (value "0.1uF")
      (footprint "eagle-import:C0603")
      (libsource (lib "eagle-import") (part "C-USC0603"))
    )
    (comp (ref "C66")
      (value "1uF")
      (footprint "eagle-import:C0603")
      (libsource (lib "eagle-import") (part "C-USC0603"))
    )
    (comp (ref "C67")
      (value "0.1uF")
      (footprint "eagle-import:C0603")
      (libsource (lib "eagle-import") (part "C-USC0603"))
    )
    (comp (ref "C128")
      (value "10pF")
      (footprint "eagle-import:C0402")
      (libsource (lib "eagle-import") (part "C-USC0402"))
    )
    (comp (ref "C129")
      (value "10pF")
      (footprint "eagle-import:C0402")
      (libsource (lib "eagle-import") (part "C-USC0402"))
    )
    (comp (ref "J1")
      (value "SI-50170")
      (footprint "eagle-import:SI-50170")
      (libsource (lib "eagle-import") (part "SI-50170"))
    )
    (comp (ref "R1")
      (value "49.9")
      (footprint "eagle-import:R0603")
      (libsource (lib "eagle-import") (part "R-US_R0603"))
    )
    (comp (ref "R3")
      (value "49.9")
      (footprint "eagle-import:R0603")
      (libsource (lib "eagle-import") (part "R-US_R0603"))
    )
    (comp (ref "R4")
      (value "49.9")
      (footprint "eagle-import:R0603")
      (libsource (lib "eagle-import") (part "R-US_R0603"))
    )
    (comp (ref "R23")
      (value "49.9")
      (footprint "eagle-import:R0603")
      (libsource (lib "eagle-import") (part "R-US_R0603"))
    )
    (comp (ref "R24")
      (value "270")
      (footprint "eagle-import:R0603")
      (libsource (lib "eagle-import") (part "R-US_R0603"))
    )
    (comp (ref "R25")
      (value "270")
      (footprint "eagle-import:R0603")
      (libsource (lib "eagle-import") (part "R-US_R0603"))
    )
    (comp (ref "R26")
      (value "12.1k")
      (footprint "eagle-import:R0603")
      (libsource (lib "eagle-import") (part "R-US_R0603"))
    )
    (comp (ref "R75")
      (value "12.1k")
      (footprint "eagle-import:R0603")
      (libsource (lib "eagle-import") (part "R-US_R0603"))
    )
    (comp (ref "R76")
      (value "12.1k")
      (footprint "eagle-import:R0603")
      (libsource (lib "eagle-import") (part "R-US_R0603"))
    )
    (comp (ref "R77")
      (value "12.1k")
      (footprint "eagle-import:R0603")
      (libsource (lib "eagle-import") (part "R-US_R0603"))
    )
    (comp (ref "R102")
      (value "12.1k")
      (footprint "eagle-import:R0603")
      (libsource (lib "eagle-import") (part "R-US_R0603"))
    )
    (comp (ref "R103")
      (value "12.1k")
      (footprint "eagle-import:R0603")
      (libsource (lib "eagle-import") (part "R-US_R0603"))
    )
    (comp (ref "R104")
      (value "12.1k")
      (footprint "eagle-import:R0603")
      (libsource (lib "eagle-import") (part "R-US_R0603"))
    )
    (comp (ref "R105")
      (value "12.1k")
      (footprint "eagle-import:R0603")
      (libsource (lib "eagle-import") (part "R-US_R0603"))
    )
    (comp (ref "U18")
      (value "LAN8742")
      (footprint "eagle-import:QFN-24")
      (libsource (lib "eagle-import") (part "LAN8742"))
    )
    (comp (ref "X1")
      (value "25MHz")
      (footprint "eagle-import:ECS-250-20-30B-DU_CRYSTAL")
      (libsource (lib "eagle-import") (part "ECS-250-20-30B-DUDU"))
    )
    (comp (ref "Z1")
      (value "CD143A-SR05")
      (footprint "eagle-import:SR2.8.TCT_1PRIMARY")
      (libsource (lib "eagle-import") (part "SR2.8_TVS"))
    )
    (comp (ref "Z2")
      (value "CD143A-SR05")
      (footprint "eagle-import:SR2.8.TCT_1PRIMARY")
      (libsource (lib "eagle-import") (part "SR2.8_TVS"))
    )
  )
  (nets
    (net (code "5") (name "+5V") (class "Default")
      (node (ref "C1") (pin "1") (pinfunction "1_1") (pintype "passive"))
      (node (ref "C108") (pin "A") (pinfunction "A_A") (pintype "passive"))
      (node (ref "C111") (pin "A") (pinfunction "A_A") (pintype "passive"))
      (node (ref "L21") (pin "1") (pinfunction "1_1") (pintype "passive"))
      (node (ref "R8") (pin "1") (pinfunction "1_1") (pintype "passive"))
      (node (ref "U12") (pin "4") (pinfunction "EN_4") (pintype "passive"))
      (node (ref "U12") (pin "8") (pinfunction "VIN_8") (pintype "passive"))
      (node (ref "U8") (pin "10") (pinfunction "VCC_10") (pintype "power_in"))
    )
    (net (code "14") (name "3V3") (class "Default")
      (node (ref "C10") (pin "1") (pinfunction "1_1") (pintype "passive"))
      (node (ref "C101") (pin "1") (pinfunction "A_1") (pintype "passive"))
      (node (ref "C103") (pin "1") (pinfunction "1_1") (pintype "passive"))
      (node (ref "C11") (pin "1") (pinfunction "1_1") (pintype "passive"))
      (node (ref "C12") (pin "1") (pinfunction "1_1") (pintype "passive"))
      (node (ref "C13") (pin "1") (pinfunction "1_1") (pintype "passive"))
      (node (ref "C14") (pin "1") (pinfunction "1_1") (pintype "passive"))
      (node (ref "C15") (pin "1") (pinfunction "1_1") (pintype "passive"))
      (node (ref "C3") (pin "1") (pinfunction "1_1") (pintype "passive"))
      (node (ref "C4") (pin "1") (pinfunction "1_1") (pintype "passive"))
      (node (ref "C6") (pin "A") (pinfunction "A_A") (pintype "passive"))
      (node (ref "C63") (pin "1") (pinfunction "1_1") (pintype "passive"))
      (node (ref "C64") (pin "1") (pinfunction "1_1") (pintype "passive"))
      (node (ref "C65") (pin "1") (pinfunction "1_1") (pintype "passive"))
      (node (ref "C76") (pin "1") (pinfunction "1_1") (pintype "passive"))
      (node (ref "C85") (pin "1") (pinfunction "A_1") (pintype "passive"))
      (node (ref "C86") (pin "1") (pinfunction "A_1") (pintype "passive"))
      (node (ref "C87") (pin "1") (pinfunction "A_1") (pintype "passive"))
      (node (ref "C88") (pin "1") (pinfunction "A_1") (pintype "passive"))
      (node (ref "C89") (pin "1") (pinfunction "A_1") (pintype "passive"))
      (node (ref "C90") (pin "1") (pinfunction "A_1") (pintype "passive"))
      (node (ref "C91") (pin "1") (pinfunction "A_1") (pintype "passive"))
      (node (ref "C92") (pin "1") (pinfunction "A_1") (pintype "passive"))
      (node (ref "C94") (pin "1") (pinfunction "A_1") (pintype "passive"))
      (node (ref "C96") (pin "1") (pinfunction "A_1") (pintype "passive"))
      (node (ref "C98") (pin "1") (pinfunction "A_1") (pintype "passive"))
      (node (ref "D1") (pin "A") (pinfunction "A_A") (pintype "passive"))
      (node (ref "D2") (pin "A") (pinfunction "A_A") (pintype "passive"))
      (node (ref "J1") (pin "2") (pinfunction "TCT_2") (pintype "passive"))
      (node (ref "J1") (pin "5") (pinfunction "RCT_5") (pintype "passive"))
      (node (ref "J3") (pin "2") (pinfunction "S_2") (pintype "passive"))
      (node (ref "J3") (pin "3") (pinfunction "S_3") (pintype "passive"))
      (node (ref "J5") (pin "4") (pinfunction "VDD_4") (pintype "bidirectional"))
      (node (ref "JP2") (pin "6") (pinfunction "11_6") (pintype "passive"))
      (node (ref "JP5") (pin "6") (pinfunction "11_6") (pintype "passive"))
      (node (ref "JP6") (pin "6") (pinfunction "11_6") (pintype "passive"))
      (node (ref "JP7") (pin "6") (pinfunction "11_6") (pintype "passive"))
      (node (ref "L17") (pin "2") (pinfunction "2_2") (pintype "passive"))
      (node (ref "L19") (pin "1") (pinfunction "1_1") (pintype "passive"))
      (node (ref "L20") (pin "2") (pinfunction "2_2") (pintype "passive"))
      (node (ref "Q17") (pin "2") (pinfunction "S_2") (pintype "passive"))
      (node (ref "R1") (pin "1") (pinfunction "1_1") (pintype "passive"))
      (node (ref "R102") (pin "1") (pinfunction "1_1") (pintype "passive"))
      (node (ref "R103") (pin "1") (pinfunction "1_1") (pintype "passive"))
      (node (ref "R23") (pin "1") (pinfunction "1_1") (pintype "passive"))
      (node (ref "R3") (pin "1") (pinfunction "1_1") (pintype "passive"))
      (node (ref "R35") (pin "1") (pinfunction "1_1") (pintype "passive"))
      (node (ref "R4") (pin "1") (pinfunction "1_1") (pintype "passive"))
      (node (ref "R49") (pin "2") (pinfunction "2_2") (pintype "passive"))
      (node (ref "R56") (pin "1") (pinfunction "1_1") (pintype "passive"))
      (node (ref "R61") (pin "1") (pinfunction "1_1") (pintype "passive"))
      (node (ref "R62") (pin "1") (pinfunction "1_1") (pintype "passive"))
      (node (ref "R63") (pin "1") (pinfunction "1_1") (pintype "passive"))
      (node (ref "R7") (pin "2") (pinfunction "2_2") (pintype "passive"))
      (node (ref "R75") (pin "1") (pinfunction "1_1") (pintype "passive"))
      (node (ref "R76") (pin "1") (pinfunction "1_1") (pintype "passive"))
      (node (ref "R77") (pin "1") (pinfunction "1_1") (pintype "passive"))
      (node (ref "U10") (pin "3") (pinfunction "/WP_3") (pintype "input"))
      (node (ref "U10") (pin "7") (pinfunction "/HOLD_7") (pintype "input"))
      (node (ref "U10") (pin "8") (pinfunction "VCC_8") (pintype "power_in"))
      (node (ref "U11") (pin "1") (pinfunction "VDD_1") (pintype "passive"))
      (node (ref "U18") (pin "1") (pinfunction "VDD2A_1") (pintype "passive"))
      (node (ref "U18") (pin "19") (pinfunction "VDD1A_19") (pintype "passive"))
      (node (ref "U18") (pin "9") (pinfunction "VDDIO_9") (pintype "passive"))
      (node (ref "U2") (pin "A13") (pinfunction "VCCIO_0_A13") (pintype "power_in"))
      (node (ref "U2") (pin "A3") (pinfunction "VCCIO_0_2_A3") (pintype "power_in"))
      (node (ref "U2") (pin "A8") (pinfunction "VCCIO_0_3_A8") (pintype "power_in"))
      (node (ref "U2") (pin "C15") (pinfunction "VCCIO_1_C15") (pintype "power_in"))
      (node (ref "U2") (pin "E1") (pinfunction "VCCIO_3_2_E1") (pintype "power_in"))
      (node (ref "U2") (pin "F8") (pinfunction "VCCIO_0_F8") (pintype "power_in"))
      (node (ref "U2") (pin "G6") (pinfunction "VCCIO_3_3_G6") (pintype "power_in"))
      (node (ref "U2") (pin "H10") (pinfunction "VCCIO_1_2_H10") (pintype "power_in"))
      (node (ref "U2") (pin "H15") (pinfunction "VCCIO_1_3_H15") (pintype "power_in"))
      (node (ref "U2") (pin "J6") (pinfunction "VCCIO_3_J6") (pintype "power_in"))
      (node (ref "U2") (pin "K8") (pinfunction "VCCIO_2_2_K8") (pintype "power_in"))
      (node (ref "U2") (pin "N1") (pinfunction "VCCIO_3_N1") (pintype "power_in"))
      (node (ref "U2") (pin "N13") (pinfunction "VCC_SPI_N13") (pintype "power_in"))
      (node (ref "U2") (pin "N15") (pinfunction "VCCIO_1_N15") (pintype "power_in"))
      (node (ref "U2") (pin "P3") (pinfunction "VCCIO_2_3_P3") (pintype "power_in"))
      (node (ref "U2") (pin "R13") (pinfunction "VCCIO_2_R13") (pintype "power_in"))
      (node (ref "U2") (pin "R8") (pinfunction "VCCIO_2_R8") (pintype "power_in"))
      (node (ref "U4") (pin "3") (pinfunction "INPUT_3") (pintype "passive"))
      (node (ref "U9") (pin "108") (pinfunction "VDD_108") (pintype "passive"))
      (node (ref "U9") (pin "121") (pinfunction "VDD_121") (pintype "passive"))
      (node (ref "U9") (pin "131") (pinfunction "VDD_131") (pintype "passive"))
      (node (ref "U9") (pin "143") (pinfunction "PDR_ON_143") (pintype "passive"))
      (node (ref "U9") (pin "144") (pinfunction "VDD_144") (pintype "passive"))
      (node (ref "U9") (pin "17") (pinfunction "VDD_17") (pintype "passive"))
      (node (ref "U9") (pin "30") (pinfunction "VDD_30") (pintype "passive"))
      (node (ref "U9") (pin "39") (pinfunction "VDD_39") (pintype "passive"))
      (node (ref "U9") (pin "52") (pinfunction "VDD_52") (pintype "passive"))
      (node (ref "U9") (pin "62") (pinfunction "VDD_62") (pintype "passive"))
      (node (ref "U9") (pin "72") (pinfunction "VDD_72") (pintype "passive"))
      (node (ref "U9") (pin "84") (pinfunction "VDD_84") (pintype "passive"))
      (node (ref "U9") (pin "95") (pinfunction "VDD_95") (pintype "passive"))
      (node (ref "Z1") (pin "4") (pinfunction "REF_4") (pintype "passive"))
      (node (ref "Z2") (pin "4") (pinfunction "REF_4") (pintype "passive"))
      (node (ref "Z3") (pin "4") (pinfunction "REF_4") (pintype "passive"))
    )
    (net (code "15") (name "ADDR0") (class "Default")
      (node (ref "U2") (pin "C16") (pinfunction "IOR_161_C16") (pintype "bidirectional"))
      (node (ref "U9") (pin "10") (pinfunction "PF0/FSMC_A0/I2C2_SDA/EVENTOUT_10") (pintype "passive"))
    )
    (net (code "16") (name "ADDR1") (class "Default")
      (node (ref "U2") (pin "T15") (pinfunction "IOB_91_T15") (pintype "bidirectional"))
      (node (ref "U9") (pin "11") (pinfunction "PF1/FSMC_A1/I2C2_SCL/EVENTOUT_11") (pintype "passive"))
    )
    (net (code "17") (name "ADDR2") (class "Default")
      (node (ref "U2") (pin "R16") (pinfunction "IOB_102_R16") (pintype "bidirectional"))
      (node (ref "U9") (pin "12") (pinfunction "PF2/FSMC_A2/I2C2_SMBA/EVENTOUT_12") (pintype "passive"))
    )
    (net (code "18") (name "ADDR3") (class "Default")
      (node (ref "U2") (pin "R15") (pinfunction "IOR_110_R15") (pintype "bidirectional"))
      (node (ref "U9") (pin "13") (pinfunction "PF3/FSMC_A3/EVENTOUT/ADC3_IN9_13") (pintype "passive"))
    )
    (net (code "19") (name "ADDR4") (class "Default")
      (node (ref "U2") (pin "P16") (pinfunction "IOR_113_P16") (pintype "bidirectional"))
      (node (ref "U9") (pin "14") (pinfunction "PF4/FSMC_A4/EVENTOUT/ADC3_IN14_14") (pintype "passive"))
    )
    (net (code "20") (name "ADDR5") (class "Default")
      (node (ref "U2") (pin "P15") (pinfunction "IOR_112_P15") (pintype "bidirectional"))
      (node (ref "U9") (pin "15") (pinfunction "PF5/FSMC_A5/EVENTOUT/ADC3_IN15_15") (pintype "passive"))
    )
    (net (code "21") (name "ADDR6") (class "Default")
      (node (ref "U2") (pin "N16") (pinfunction "IOR_117_N16") (pintype "bidirectional"))
      (node (ref "U9") (pin "50") (pinfunction "PF12/FSMC_A6/EVENTOUT_50") (pintype "passive"))
    )
    (net (code "22") (name "ADDR7") (class "Default")
      (node (ref "U2") (pin "M16") (pinfunction "IOR_121_M16") (pintype "bidirectional"))
      (node (ref "U9") (pin "53") (pinfunction "PF13/FSMC_A7/EVENTOUT_53") (pintype "passive"))
    )
    (net (code "23") (name "ADDR8") (class "Default")
      (node (ref "U2") (pin "M15") (pinfunction "IOR_123_M15") (pintype "bidirectional"))
      (node (ref "U9") (pin "54") (pinfunction "PF14/FSMC_A8/EVENTOUT_54") (pintype "passive"))
    )
    (net (code "24") (name "ADDR9") (class "Default")
      (node (ref "U2") (pin "L16") (pinfunction "IOR_127_L16") (pintype "bidirectional"))
      (node (ref "U9") (pin "55") (pinfunction "PF15/FSMC_A9/EVENTOUT_55") (pintype "passive"))
    )
    (net (code "25") (name "ADDR10") (class "Default")
      (node (ref "U2") (pin "T14") (pinfunction "IOB_92_T14") (pintype "bidirectional"))
      (node (ref "U9") (pin "56") (pinfunction "PG0/FSMC_A10/EVENTOUT_56") (pintype "passive"))
    )
    (net (code "26") (name "ADDR11") (class "Default")
      (node (ref "U2") (pin "R14") (pinfunction "IOR_109_R14") (pintype "bidirectional"))
      (node (ref "U9") (pin "57") (pinfunction "PG1/FSMC_A11/EVENTOUT_57") (pintype "passive"))
    )
    (net (code "27") (name "ADDR12") (class "Default")
      (node (ref "U2") (pin "P14") (pinfunction "IOR_111_P14") (pintype "bidirectional"))
      (node (ref "U9") (pin "87") (pinfunction "PG2/FSMC_A12/EVENTOUT_87") (pintype "passive"))
    )
    (net (code "28") (name "ADDR13") (class "Default")
      (node (ref "U2") (pin "L14") (pinfunction "IOR_119_L14") (pintype "bidirectional"))
      (node (ref "U9") (pin "88") (pinfunction "PG3/FSMC_A13/EVENTOUT_88") (pintype "passive"))
    )
    (net (code "29") (name "ADDR14") (class "Default")
      (node (ref "U2") (pin "D14") (pinfunction "IOR_167_D14") (pintype "bidirectional"))
      (node (ref "U9") (pin "89") (pinfunction "PG4/FSMC_A14/EVENTOUT_89") (pintype "passive"))
    )
    (net (code "30") (name "ADDR15") (class "Default")
      (node (ref "U2") (pin "C14") (pinfunction "IOT_168_C14") (pintype "bidirectional"))
      (node (ref "U9") (pin "90") (pinfunction "PG5/FSMC_A15/EVENTOUT_90") (pintype "passive"))
    )
    (net (code "31") (name "AUDIO_LEFT") (class "Default")
      (node (ref "C79") (pin "1") (pinfunction "1_1") (pintype "passive"))
      (node (ref "J2") (pin "R") (pinfunction "R_R") (pintype "passive"))
      (node (ref "R38") (pin "1") (pinfunction "1_1") (pintype "passive"))
    )
    (net (code "32") (name "AUDIO_RIGHT") (class "Default")
      (node (ref "C78") (pin "1") (pinfunction "1_1") (pintype "passive"))
      (node (ref "J2") (pin "L") (pinfunction "L_L") (pintype "passive"))
      (node (ref "R37") (pin "1") (pinfunction "1_1") (pintype "passive"))
    )
    (net (code "33") (name "BL_A") (class "Default")
      (node (ref "J3") (pin "17") (pinfunction "S_17") (pintype "passive"))
      (node (ref "R52") (pin "1") (pinfunction "1_1") (pintype "passive"))
      (node (ref "R53") (pin "1") (pinfunction "1_1") (pintype "passive"))
      (node (ref "R54") (pin "1") (pinfunction "1_1") (pintype "passive"))
    )
    (net (code "34") (name "CBSEL") (class "Default")
      (node (ref "U2") (pin "P13") (pinfunction "IOB_104_CBSEL1_P13") (pintype "bidirectional"))
      (node (ref "U9") (pin "91") (pinfunction "PG6/FSMC_INT2/EVENTOUT_91") (pintype "passive"))
    )
    (net (code "35") (name "CDONE") (class "Default")
      (node (ref "U2") (pin "M10") (pinfunction "CDONE_M10") (pintype "passive"))
      (node (ref "U9") (pin "92") (pinfunction "PG7/FSMC_INT3/USART6_CK/EVENTOUT_92") (pintype "passive"))
    )
    (net (code "36") (name "CRESET_B") (class "Default")
      (node (ref "U2") (pin "N11") (pinfunction "CRESET_B_N11") (pintype "passive"))
      (node (ref "U9") (pin "93") (pinfunction "PG8/USART6_RTS/ETH_PPS_OUT/EVENTOUT_93") (pintype "passive"))
    )
    (net (code "37") (name "CSB") (class "Default")
      (node (ref "J3") (pin "4") (pinfunction "S_4") (pintype "passive"))
      (node (ref "U2") (pin "B5") (pinfunction "IOT_214_B5") (pintype "bidirectional"))
    )
    (net (code "38") (name "DATA0") (class "Default")
      (node (ref "U2") (pin "D16") (pinfunction "IOR_153_D16") (pintype "bidirectional"))
      (node (ref "U9") (pin "85") (pinfunction "PD14/FSMC_D0/TIM4_CH3/EVENTOUT_85") (pintype "passive"))
    )
    (net (code "39") (name "DATA1") (class "Default")
      (node (ref "U2") (pin "D15") (pinfunction "IOR_157_D15") (pintype "bidirectional"))
      (node (ref "U9") (pin "86") (pinfunction "PD15/FSMC_D1/TIM4_CH4/EVENTOUT_86") (pintype "passive"))
    )
    (net (code "40") (name "DATA2") (class "Default")
      (node (ref "U2") (pin "B16") (pinfunction "IOR_165_B16") (pintype "bidirectional"))
      (node (ref "U9") (pin "114") (pinfunction "PD0/FSMC_D2/CAN1_RX/EVENTOUT_114") (pintype "passive"))
    )
    (net (code "41") (name "DATA3") (class "Default")
      (node (ref "U2") (pin "B15") (pinfunction "IOT_169_B15") (pintype "bidirectional"))
      (node (ref "U9") (pin "115") (pinfunction "PD1/FSMC_D3/CAN1_TX/EVENTOUT_115") (pintype "passive"))
    )
    (net (code "42") (name "DATA4") (class "Default")
      (node (ref "U2") (pin "A16") (pinfunction "IOT_176_A16") (pintype "bidirectional"))
      (node (ref "U9") (pin "58") (pinfunction "PE7/FSMC_D4/TIM1_ETR/EVENTOUT_58") (pintype "passive"))
    )
    (net (code "43") (name "DATA5") (class "Default")
      (node (ref "U2") (pin "A15") (pinfunction "IOT_177_A15") (pintype "bidirectional"))
      (node (ref "U9") (pin "59") (pinfunction "PE8/FSMC_D5/TIM1/CH1N/EVENTOUT_59") (pintype "passive"))
    )
    (net (code "44") (name "DATA6") (class "Default")
      (node (ref "U2") (pin "E16") (pinfunction "IOR_151_E16") (pintype "bidirectional"))
      (node (ref "U9") (pin "60") (pinfunction "PE9/FSMC_D6/TIM1_CH1/EVENTOUT_60") (pintype "passive"))
    )
    (net (code "45") (name "DATA7") (class "Default")
      (node (ref "U2") (pin "F15") (pinfunction "IOR_149_F15") (pintype "bidirectional"))
      (node (ref "U9") (pin "63") (pinfunction "PE10/FSMC_D7/TIM1_CH2N/EVENTOUT_63") (pintype "passive"))
    )
    (net (code "46") (name "DATA8") (class "Default")
      (node (ref "U2") (pin "F16") (pinfunction "IOR_147_F16") (pintype "bidirectional"))
      (node (ref "U9") (pin "64") (pinfunction "PE11/FSMC_D8/TIM1_CH2/EVENTOUT_64") (pintype "passive"))
    )
    (net (code "47") (name "DATA9") (class "Default")
      (node (ref "U2") (pin "G15") (pinfunction "IOR_145_G15") (pintype "bidirectional"))
      (node (ref "U9") (pin "65") (pinfunction "PE12/FSMC_D9/TIM1_CH3N/EVENTOUT_65") (pintype "passive"))
    )
    (net (code "48") (name "DATA10") (class "Default")
      (node (ref "U2") (pin "G16") (pinfunction "IOR_143_G16") (pintype "bidirectional"))
      (node (ref "U9") (pin "66") (pinfunction "PE13/FSMC_D10/TIM1_CH3/EVENTOUT_66") (pintype "passive"))
    )
    (net (code "49") (name "DATA11") (class "Default")
      (node (ref "U2") (pin "J15") (pinfunction "IOR_130_J15") (pintype "bidirectional"))
      (node (ref "U9") (pin "67") (pinfunction "PE14/FSMC_D11/TIM1_CH4/EVENTOUT_67") (pintype "passive"))
    )
    (net (code "50") (name "DATA12") (class "Default")
      (node (ref "U2") (pin "J16") (pinfunction "IOR_138_J16") (pintype "bidirectional"))
      (node (ref "U9") (pin "68") (pinfunction "PE15/FSMC_D12/TIM1_BKIN/EVENTOUT_68") (pintype "passive"))
    )
    (net (code "51") (name "DATA13") (class "Default")
      (node (ref "U2") (pin "K15") (pinfunction "IOR_131_K15") (pintype "bidirectional"))
      (node (ref "U9") (pin "77") (pinfunction "PD8/FSMC_D13/USART3_TX/EVENTOUT_77") (pintype "passive"))
    )
    (net (code "52") (name "DATA14") (class "Default")
      (node (ref "U2") (pin "K16") (pinfunction "IOR_133_K16") (pintype "bidirectional"))
      (node (ref "U9") (pin "78") (pinfunction "PD9/FSMC_D14/USART3_RX/EVENTOUT_78") (pintype "passive"))
    )
    (net (code "53") (name "DATA15") (class "Default")
      (node (ref "U2") (pin "T16") (pinfunction "IOB_100_T16") (pintype "bidirectional"))
      (node (ref "U9") (pin "79") (pinfunction "PD10/FSMC_D15/USART3_CK/EVENTOUT_79") (pintype "passive"))
    )
    (net (code "54") (name "DB0") (class "Default")
      (node (ref "J3") (pin "9") (pinfunction "S_9") (pintype "passive"))
      (node (ref "U2") (pin "A6") (pinfunction "IOT_211_A6") (pintype "bidirectional"))
    )
    (net (code "55") (name "DB1") (class "Default")
      (node (ref "J3") (pin "10") (pinfunction "S_10") (pintype "passive"))
      (node (ref "U2") (pin "A7") (pinfunction "IOT_205_A7") (pintype "bidirectional"))
    )
    (net (code "56") (name "DB2") (class "Default")
      (node (ref "J3") (pin "11") (pinfunction "S_11") (pintype "passive"))
      (node (ref "U2") (pin "A9") (pinfunction "IOT_194_A9") (pintype "bidirectional"))
    )
    (net (code "57") (name "DB3") (class "Default")
      (node (ref "J3") (pin "12") (pinfunction "S_12") (pintype "passive"))
      (node (ref "U2") (pin "A10") (pinfunction "IOT_186_A10") (pintype "bidirectional"))
    )
    (net (code "58") (name "DB4") (class "Default")
      (node (ref "J3") (pin "13") (pinfunction "S_13") (pintype "passive"))
      (node (ref "U2") (pin "A11") (pinfunction "IOT_187_A11") (pintype "bidirectional"))
    )
    (net (code "59") (name "DB5") (class "Default")
      (node (ref "J3") (pin "14") (pinfunction "S_14") (pintype "passive"))
      (node (ref "U2") (pin "B6") (pinfunction "IOT_208_B6") (pintype "bidirectional"))
    )
    (net (code "60") (name "DB6") (class "Default")
      (node (ref "J3") (pin "15") (pinfunction "S_15") (pintype "passive"))
      (node (ref "U2") (pin "B7") (pinfunction "IOT_207_B7") (pintype "bidirectional"))
    )
    (net (code "61") (name "DB7") (class "Default")
      (node (ref "J3") (pin "16") (pinfunction "S_16") (pintype "passive"))
      (node (ref "U2") (pin "B8") (pinfunction "IOT_203_B8") (pintype "bidirectional"))
    )
    (net (code "62") (name "ETH_RMII_REF_CLK") (class "Default")
      (node (ref "R76") (pin "2") (pinfunction "2_2") (pintype "passive"))
      (node (ref "U18") (pin "14") (pinfunction "~{INT/REFCLK0}_14") (pintype "passive"))
      (node (ref "U9") (pin "35") (pinfunction "PA1/USART2_RTS/UART4_RX/ETH_RMII_REF_CLK/ETH_MII_RX_CLK/TIM5_CH2/TIMM2_CH2/EVENTOUT/ADC123_IN1_35") (pintype "passive"))
    )
    (net (code "63") (name "ETH_RX+") (class "Default")
      (node (ref "J1") (pin "4") (pinfunction "RD+_4") (pintype "passive"))
      (node (ref "R23") (pin "2") (pinfunction "2_2") (pintype "passive"))
      (node (ref "U18") (pin "23") (pinfunction "RXP_23") (pintype "passive"))
      (node (ref "Z2") (pin "3") (pinfunction "I/O_3") (pintype "passive"))
    )
    (net (code "64") (name "ETH_RX-") (class "Default")
      (node (ref "J1") (pin "6") (pinfunction "RD-_6") (pintype "passive"))
      (node (ref "R4") (pin "2") (pinfunction "2_2") (pintype "passive"))
      (node (ref "U18") (pin "22") (pinfunction "RXN_22") (pintype "passive"))
      (node (ref "Z2") (pin "2") (pinfunction "I/O_2") (pintype "passive"))
    )
    (net (code "65") (name "ETH_TX+") (class "Default")
      (node (ref "J1") (pin "1") (pinfunction "TD+_1") (pintype "passive"))
      (node (ref "R1") (pin "2") (pinfunction "2_2") (pintype "passive"))
      (node (ref "U18") (pin "21") (pinfunction "TXP_21") (pintype "passive"))
      (node (ref "Z1") (pin "3") (pinfunction "I/O_3") (pintype "passive"))
    )
    (net (code "66") (name "ETH_TX-") (class "Default")
      (node (ref "J1") (pin "3") (pinfunction "TD-_3") (pintype "passive"))
      (node (ref "R3") (pin "2") (pinfunction "2_2") (pintype "passive"))
      (node (ref "U18") (pin "20") (pinfunction "TXN_20") (pintype "passive"))
      (node (ref "Z1") (pin "2") (pinfunction "I/O_2") (pintype "passive"))
    )
    (net (code "67") (name "EXP_PIN12_VOLT") (class "Default")
      (node (ref "JP2") (pin "12") (pinfunction "12_12") (pintype "passive"))
      (node (ref "JP5") (pin "12") (pinfunction "12_12") (pintype "passive"))
      (node (ref "JP6") (pin "12") (pinfunction "12_12") (pintype "passive"))
      (node (ref "JP7") (pin "12") (pinfunction "12_12") (pintype "passive"))
      (node (ref "R35") (pin "2") (pinfunction "2_2") (pintype "passive"))
      (node (ref "R8") (pin "2") (pinfunction "2_2") (pintype "passive"))
    )
    (net (code "68") (name "FLASH1_CS") (class "Default")
      (node (ref "U10") (pin "1") (pinfunction "/CS_1") (pintype "input"))
      (node (ref "U9") (pin "98") (pinfunction "PC8/TIM8_CH3/SDIO_D0/TIM3_CH3/USART6_CK/DCMI_D2/EVENTOUT_98") (pintype "passive"))
    )
    (net (code "69") (name "FPGA_CFG_CS") (class "Default")
      (node (ref "U2") (pin "R12") (pinfunction "IOB_108_SS_R12") (pintype "bidirectional"))
      (node (ref "U9") (pin "97") (pinfunction "PC7/I2S3_MCK/TIM8_CH2/SDIO_D7/USART6_RX/DCMI_D1/TIM3_CH2/EVENTOUT_97") (pintype "passive"))
    )
    (net (code "70") (name "FPGA_VCC_1V2") (class "Default")
      (node (ref "C7") (pin "A") (pinfunction "A_A") (pintype "passive"))
      (node (ref "L1") (pin "1") (pinfunction "1_1") (pintype "passive"))
      (node (ref "R50") (pin "2") (pinfunction "2_2") (pintype "passive"))
      (node (ref "U2") (pin "A14") (pinfunction "VCC_A14") (pintype "power_in"))
      (node (ref "U2") (pin "F10") (pinfunction "VCC_2_F10") (pintype "power_in"))
      (node (ref "U2") (pin "F6") (pinfunction "VCC_F6") (pintype "power_in"))
      (node (ref "U2") (pin "K10") (pinfunction "VCC_K10") (pintype "power_in"))
      (node (ref "U2") (pin "K6") (pinfunction "VCC_2_K6") (pintype "power_in"))
      (node (ref "U2") (pin "L2") (pinfunction "VCC_3_L2") (pintype "power_in"))
      (node (ref "U4") (pin "2") (pinfunction "OUTPUT_2") (pintype "passive"))
    )
    (net (code "71") (name "FSMC_CLK") (class "Default")
      (node (ref "U2") (pin "K9") (pinfunction "IOB_82_GBIN4_K9") (pintype "bidirectional"))
      (node (ref "U9") (pin "117") (pinfunction "PD3/FSMC_CLK/USART2_CTS/EVENTOUT_117") (pintype "passive"))
    )
    (net (code "72") (name "FSMC_NE1") (class "Default")
      (node (ref "U2") (pin "J14") (pinfunction "IOR_134_J14") (pintype "bidirectional"))
      (node (ref "U9") (pin "123") (pinfunction "PD7/USART2_CK/FSMC_NE1/FSMC_NCE2/EVENTOUT_123") (pintype "passive"))
    )
    (net (code "73") (name "FSMC_NE4") (class "Default")
      (node (ref "U2") (pin "K14") (pinfunction "IOR_129_K14") (pintype "bidirectional"))
      (node (ref "U9") (pin "127") (pinfunction "PG12/FSMC_NE4/USART6_RTS/EVENTOUT_127") (pintype "passive"))
    )
    (net (code "74") (name "FSMC_NL_NADV") (class "Default")
      (node (ref "U2") (pin "B14") (pinfunction "IOT_171_B14") (pintype "bidirectional"))
      (node (ref "U9") (pin "137") (pinfunction "PB7/I2C1_SDA/FSMC_NL/DCMI_VSYNC/USART1_RX/TIM4_CH2/EVENTOUT_137") (pintype "passive"))
    )
    (net (code "75") (name "FSMC_NOE") (class "Default")
      (node (ref "U2") (pin "F14") (pinfunction "IOR_155_F14") (pintype "bidirectional"))
      (node (ref "U9") (pin "118") (pinfunction "PD4/FSMC_NOE/USART2_RTS/EVENTOUT_118") (pintype "passive"))
    )
    (net (code "76") (name "FSMC_NWE") (class "Default")
      (node (ref "U2") (pin "H14") (pinfunction "IOR_142_H14") (pintype "bidirectional"))
      (node (ref "U9") (pin "119") (pinfunction "PD5/FSMC_NWE/USART2_TX/EVENTOUT_119") (pintype "passive"))
    )
    (net (code "77") (name "F_LRCLK") (class "Default")
      (node (ref "U2") (pin "G14") (pinfunction "IOR_150_G14") (pintype "bidirectional"))
      (node (ref "U9") (pin "73") (pinfunction "PB12/SPI2_NSS/I2S2_WS/I2C2_SMBA/USART3_CK/TIM1_BKIN/CAN2_RX/OTG_HS_ULPI_D5/ETH_RMII_TXD0/ETH_MII_TXD0/OTG_HS_ID/EVENTOUT_73") (pintype "passive"))
    )
    (net (code "78") (name "F_MCLK") (class "Default")
      (node (ref "U2") (pin "H16") (pinfunction "IOR_141_GBIN2_H16") (pintype "bidirectional"))
      (node (ref "U9") (pin "96") (pinfunction "PC6/I2S2_MCK/TIM8_CH1/SDIO_D6/USART6_TX/DCMI_D0/TIM3_CH1/EVENTOUT_96") (pintype "passive"))
    )
    (net (code "79") (name "F_SCLK") (class "Default")
      (node (ref "U2") (pin "H11") (pinfunction "IOR_140_GBIN3_H11") (pintype "bidirectional"))
      (node (ref "U9") (pin "74") (pinfunction "PB13/SPI2_SCK/I2S2_CK/USART3_CTS/TIM1_CH1N/CAN2_TX/OTG_HS_ULPI_D6/ETH_RMII_TXD1/ETH_MII_TXD1/EVENTOUT_74") (pintype "passive"))
    )
    (net (code "80") (name "F_SDIN") (class "Default")
      (node (ref "U2") (pin "E14") (pinfunction "IOR_160_E14") (pintype "bidirectional"))
      (node (ref "U9") (pin "76") (pinfunction "PB15/SPI2_MOSI/I2S2_SD/TIM1_CH3N/TIM8_CH3N/TIM12_CH2/OTG_HS_DP/EVENTOUT_76") (pintype "passive"))
    )
    (net (code "81") (name "GB0_CE") (class "Default")
      (node (ref "U2") (pin "F7") (pinfunction "IOT_198_GBIN0_F7") (pintype "bidirectional"))
    )
    (net (code "82") (name "GB1_RST") (class "Default")
      (node (ref "U2") (pin "C8") (pinfunction "IOT_197_GBIN1_C8") (pintype "bidirectional"))
    )
    (net (code "83") (name "GB6_CE") (class "Default")
      (node (ref "U2") (pin "J3") (pinfunction "IOL_14A_GBIN6_J3") (pintype "bidirectional"))
    )
    (net (code "84") (name "GB7_RST") (class "Default")
      (node (ref "U2") (pin "G1") (pinfunction "IOL_13B_GBIN7_G1") (pintype "bidirectional"))
    )
    (net (code "85") (name "GND") (class "Default")
      (node (ref "C1") (pin "2") (pinfunction "2_2") (pintype "passive"))
      (node (ref "C10") (pin "2") (pinfunction "2_2") (pintype "passive"))
      (node (ref "C100") (pin "2") (pinfunction "2_2") (pintype "passive"))
      (node (ref "C101") (pin "2") (pinfunction "C_2") (pintype "passive"))
      (node (ref "C102") (pin "2") (pinfunction "2_2") (pintype "passive"))
      (node (ref "C103") (pin "2") (pinfunction "2_2") (pintype "passive"))
      (node (ref "C105") (pin "C") (pinfunction "C_C") (pintype "passive"))
      (node (ref "C106") (pin "C") (pinfunction "C_C") (pintype "passive"))
      (node (ref "C107") (pin "2") (pinfunction "2_2") (pintype "passive"))
      (node (ref "C108") (pin "C") (pinfunction "C_C") (pintype "passive"))
      (node (ref "C109") (pin "2") (pinfunction "2_2") (pintype "passive"))
      (node (ref "C11") (pin "2") (pinfunction "2_2") (pintype "passive"))
      (node (ref "C110") (pin "2") (pinfunction "2_2") (pintype "passive"))
      (node (ref "C111") (pin "C") (pinfunction "C_C") (pintype "passive"))
      (node (ref "C12") (pin "2") (pinfunction "2_2") (pintype "passive"))
      (node (ref "C128") (pin "1") (pinfunction "1_1") (pintype "passive"))
      (node (ref "C129") (pin "1") (pinfunction "1_1") (pintype "passive"))
      (node (ref "C13") (pin "2") (pinfunction "2_2") (pintype "passive"))
      (node (ref "C14") (pin "2") (pinfunction "2_2") (pintype "passive"))
      (node (ref "C15") (pin "2") (pinfunction "2_2") (pintype "passive"))
      (node (ref "C16") (pin "2") (pinfunction "2_2") (pintype "passive"))
      (node (ref "C2") (pin "2") (pinfunction "2_2") (pintype "passive"))
      (node (ref "C21") (pin "1") (pinfunction "1_1") (pintype "passive"))
      (node (ref "C3") (pin "2") (pinfunction "2_2") (pintype "passive"))
      (node (ref "C4") (pin "2") (pinfunction "2_2") (pintype "passive"))
      (node (ref "C40") (pin "2") (pinfunction "C_2") (pintype "passive"))
      (node (ref "C5") (pin "1") (pinfunction "1_1") (pintype "passive"))
      (node (ref "C6") (pin "C") (pinfunction "C_C") (pintype "passive"))
      (node (ref "C63") (pin "2") (pinfunction "2_2") (pintype "passive"))
      (node (ref "C64") (pin "2") (pinfunction "2_2") (pintype "passive"))
      (node (ref "C65") (pin "2") (pinfunction "2_2") (pintype "passive"))
      (node (ref "C66") (pin "2") (pinfunction "2_2") (pintype "passive"))
      (node (ref "C67") (pin "2") (pinfunction "2_2") (pintype "passive"))
      (node (ref "C7") (pin "C") (pinfunction "C_C") (pintype "passive"))
      (node (ref "C71") (pin "2") (pinfunction "2_2") (pintype "passive"))
      (node (ref "C72") (pin "2") (pinfunction "2_2") (pintype "passive"))
      (node (ref "C73") (pin "1") (pinfunction "1_1") (pintype "passive"))
      (node (ref "C74") (pin "2") (pinfunction "2_2") (pintype "passive"))
      (node (ref "C76") (pin "2") (pinfunction "2_2") (pintype "passive"))
      (node (ref "C78") (pin "2") (pinfunction "2_2") (pintype "passive"))
      (node (ref "C79") (pin "2") (pinfunction "2_2") (pintype "passive"))
      (node (ref "C8") (pin "C") (pinfunction "C_C") (pintype "passive"))
      (node (ref "C85") (pin "2") (pinfunction "C_2") (pintype "passive"))
      (node (ref "C86") (pin "2") (pinfunction "C_2") (pintype "passive"))
      (node (ref "C87") (pin "2") (pinfunction "C_2") (pintype "passive"))
      (node (ref "C88") (pin "2") (pinfunction "C_2") (pintype "passive"))
      (node (ref "C89") (pin "2") (pinfunction "C_2") (pintype "passive"))
      (node (ref "C9") (pin "2") (pinfunction "2_2") (pintype "passive"))
      (node (ref "C90") (pin "2") (pinfunction "C_2") (pintype "passive"))
      (node (ref "C91") (pin "2") (pinfunction "C_2") (pintype "passive"))
      (node (ref "C92") (pin "2") (pinfunction "C_2") (pintype "passive"))
      (node (ref "C94") (pin "2") (pinfunction "C_2") (pintype "passive"))
      (node (ref "C96") (pin "2") (pinfunction "C_2") (pintype "passive"))
      (node (ref "C98") (pin "2") (pinfunction "C_2") (pintype "passive"))
      (node (ref "C99") (pin "2") (pinfunction "C_2") (pintype "passive"))
      (node (ref "CON1") (pin "5") (pinfunction "GND_5") (pintype "passive"))
      (node (ref "CON1") (pin "6") (pinfunction "SGND_6") (pintype "passive"))
      (node (ref "CON1") (pin "7") (pinfunction "SGND_7") (pintype "passive"))
      (node (ref "CON1") (pin "8") (pinfunction "SGND_8") (pintype "passive"))
      (node (ref "CON1") (pin "9") (pinfunction "SGND_9") (pintype "passive"))
      (node (ref "H1") (pin "B2,8") (pinfunction "MOUNT_B2,8") (pintype "passive"))
      (node (ref "H2") (pin "B2,8") (pinfunction "MOUNT_B2,8") (pintype "passive"))
      (node (ref "H3") (pin "B2,8") (pinfunction "MOUNT_B2,8") (pintype "passive"))
      (node (ref "H4") (pin "B2,8") (pinfunction "MOUNT_B2,8") (pintype "passive"))
      (node (ref "J1") (pin "8") (pinfunction "C_GND_8") (pintype "passive"))
      (node (ref "J1") (pin "S1") (pinfunction "S1_S1") (pintype "passive"))
      (node (ref "J1") (pin "S2") (pinfunction "S2_S2") (pintype "passive"))
      (node (ref "J2") (pin "G") (pinfunction "G_G") (pintype "passive"))
      (node (ref "J3") (pin "1") (pinfunction "S_1") (pintype "passive"))
      (node (ref "J3") (pin "18") (pinfunction "S_18") (pintype "passive"))
      (node (ref "J3") (pin "19") (pinfunction "S_19") (pintype "passive"))
      (node (ref "J3") (pin "20") (pinfunction "S_20") (pintype "passive"))
      (node (ref "J5") (pin "6") (pinfunction "VSS_6") (pintype "bidirectional"))
      (node (ref "JP1") (pin "3") (pinfunction "3_3") (pintype "passive"))
      (node (ref "JP2") (pin "11") (pinfunction "10_11") (pintype "passive"))
      (node (ref "JP2") (pin "5") (pinfunction "9_5") (pintype "passive"))
      (node (ref "JP3") (pin "2") (pinfunction "2_2") (pintype "passive"))
      (node (ref "JP4") (pin "5") (pinfunction "5_5") (pintype "passive"))
      (node (ref "JP5") (pin "11") (pinfunction "10_11") (pintype "passive"))
      (node (ref "JP5") (pin "5") (pinfunction "9_5") (pintype "passive"))
      (node (ref "JP6") (pin "11") (pinfunction "10_11") (pintype "passive"))
      (node (ref "JP6") (pin "5") (pinfunction "9_5") (pintype "passive"))
      (node (ref "JP7") (pin "11") (pinfunction "10_11") (pintype "passive"))
      (node (ref "JP7") (pin "5") (pinfunction "9_5") (pintype "passive"))
      (node (ref "R104") (pin "2") (pinfunction "2_2") (pintype "passive"))
      (node (ref "R105") (pin "2") (pinfunction "2_2") (pintype "passive"))
      (node (ref "R2") (pin "2") (pinfunction "2_2") (pintype "passive"))
      (node (ref "R24") (pin "2") (pinfunction "2_2") (pintype "passive"))
      (node (ref "R25") (pin "2") (pinfunction "2_2") (pintype "passive"))
      (node (ref "R26") (pin "2") (pinfunction "2_2") (pintype "passive"))
      (node (ref "R36") (pin "2") (pinfunction "2_2") (pintype "passive"))
      (node (ref "R5") (pin "2") (pinfunction "2_2") (pintype "passive"))
      (node (ref "R50") (pin "1") (pinfunction "1_1") (pintype "passive"))
      (node (ref "SW3") (pin "1") (pinfunction "1_1") (pintype "passive"))
      (node (ref "SW3") (pin "4") (pinfunction "4_4") (pintype "passive"))
      (node (ref "U10") (pin "4") (pinfunction "GND_4") (pintype "power_in"))
      (node (ref "U11") (pin "2") (pinfunction "LR_2") (pintype "passive"))
      (node (ref "U11") (pin "5") (pinfunction "GND_5") (pintype "passive"))
      (node (ref "U11") (pin "6") (pinfunction "GND_6") (pintype "passive"))
      (node (ref "U11") (pin "7") (pinfunction "GND_7") (pintype "passive"))
      (node (ref "U11") (pin "8") (pinfunction "GND_8") (pintype "passive"))
      (node (ref "U12") (pin "GPAD") (pinfunction "GPAD_GPAD") (pintype "passive"))
      (node (ref "U18") (pin "GP") (pinfunction "GP_GP") (pintype "passive"))
      (node (ref "U2") (pin "A12") (pinfunction "GND_A12") (pintype "power_in"))
      (node (ref "U2") (pin "A4") (pinfunction "GND_2_A4") (pintype "power_in"))
      (node (ref "U2") (pin "E15") (pinfunction "GND_2_E15") (pintype "power_in"))
      (node (ref "U2") (pin "E7") (pinfunction "GNDPLL1_E7") (pintype "power_in"))
      (node (ref "U2") (pin "G7") (pinfunction "GND_3_G7") (pintype "power_in"))
      (node (ref "U2") (pin "G8") (pinfunction "GND_4_G8") (pintype "power_in"))
      (node (ref "U2") (pin "G9") (pinfunction "GND_5_G9") (pintype "power_in"))
      (node (ref "U2") (pin "H7") (pinfunction "GND_6_H7") (pintype "power_in"))
      (node (ref "U2") (pin "H8") (pinfunction "GND_7_H8") (pintype "power_in"))
      (node (ref "U2") (pin "H9") (pinfunction "GND_8_H9") (pintype "power_in"))
      (node (ref "U2") (pin "J7") (pinfunction "GND_9_J7") (pintype "power_in"))
      (node (ref "U2") (pin "J8") (pinfunction "GND_10_J8") (pintype "power_in"))
      (node (ref "U2") (pin "J9") (pinfunction "GND_11_J9") (pintype "power_in"))
      (node (ref "U2") (pin "K2") (pinfunction "GND_K2") (pintype "power_in"))
      (node (ref "U2") (pin "K7") (pinfunction "GND_2_K7") (pintype "power_in"))
      (node (ref "U2") (pin "L15") (pinfunction "GND_3_L15") (pintype "power_in"))
      (node (ref "U2") (pin "N8") (pinfunction "GNDPLL0_N8") (pintype "power_in"))
      (node (ref "U2") (pin "R7") (pinfunction "GND_3_R7") (pintype "power_in"))
      (node (ref "U2") (pin "T12") (pinfunction "GND_T12") (pintype "power_in"))
      (node (ref "U2") (pin "T4") (pinfunction "GND_4_T4") (pintype "power_in"))
      (node (ref "U4") (pin "1") (pinfunction "GROUND_1") (pintype "passive"))
      (node (ref "U7") (pin "8") (pinfunction "GND_8") (pintype "power_in"))
      (node (ref "U8") (pin "13") (pinfunction "GND_13") (pintype "power_in"))
      (node (ref "U8") (pin "3") (pinfunction "GND_3") (pintype "power_in"))
      (node (ref "U9") (pin "107") (pinfunction "VSS_107") (pintype "passive"))
      (node (ref "U9") (pin "120") (pinfunction "VSS_120") (pintype "passive"))
      (node (ref "U9") (pin "130") (pinfunction "VSS_130") (pintype "passive"))
      (node (ref "U9") (pin "138") (pinfunction "BOOT0/VPP_138") (pintype "passive"))
      (node (ref "U9") (pin "16") (pinfunction "VSS_16") (pintype "passive"))
      (node (ref "U9") (pin "31") (pinfunction "VSSA_31") (pintype "passive"))
      (node (ref "U9") (pin "38") (pinfunction "VSS_38") (pintype "passive"))
      (node (ref "U9") (pin "51") (pinfunction "VSS_51") (pintype "passive"))
      (node (ref "U9") (pin "61") (pinfunction "VSS_61") (pintype "passive"))
      (node (ref "U9") (pin "83") (pinfunction "VSS_83") (pintype "passive"))
      (node (ref "U9") (pin "94") (pinfunction "VSS_94") (pintype "passive"))
      (node (ref "X1") (pin "GND@1") (pinfunction "1_GND@1") (pintype "passive"))
      (node (ref "X1") (pin "GND@2") (pinfunction "2_GND@2") (pintype "passive"))
      (node (ref "X2") (pin "GND@1") (pinfunction "1_GND@1") (pintype "passive"))
      (node (ref "X2") (pin "GND@2") (pinfunction "2_GND@2") (pintype "passive"))
      (node (ref "Z1") (pin "1") (pinfunction "GND_1") (pintype "passive"))
      (node (ref "Z2") (pin "1") (pinfunction "GND_1") (pintype "passive"))
      (node (ref "Z3") (pin "1") (pinfunction "GND_1") (pintype "passive"))
      (node (ref "Z4") (pin "1") (pinfunction "GND_1") (pintype "passive"))
    )
    (net (code "86") (name "LED1") (class "Default")
      (node (ref "J1") (pin "A1") (pinfunction "A_A1") (pintype "passive"))
      (node (ref "U18") (pin "3") (pinfunction "LED1/REGOFF_3") (pintype "passive"))
    )
    (net (code "87") (name "LED2_~{INTSEL}") (class "Default")
      (node (ref "J1") (pin "A2") (pinfunction "A1_A2") (pintype "passive"))
      (node (ref "R105") (pin "1") (pinfunction "1_1") (pintype "passive"))
      (node (ref "U18") (pin "2") (pinfunction "LED2/~{INTSEL}_2") (pintype "passive"))
    )
    (net (code "88") (name "LED_F1") (class "Default")
      (node (ref "R10") (pin "2") (pinfunction "2_2") (pintype "passive"))
      (node (ref "U2") (pin "A1") (pinfunction "IOT_220_A1") (pintype "bidirectional"))
    )
    (net (code "89") (name "LED_F2") (class "Default")
      (node (ref "R6") (pin "2") (pinfunction "2_2") (pintype "passive"))
      (node (ref "U2") (pin "A2") (pinfunction "IOT_218_A2") (pintype "bidirectional"))
    )
    (net (code "90") (name "LRCLK") (class "Default")
      (node (ref "R59") (pin "2") (pinfunction "2_2") (pintype "passive"))
      (node (ref "U2") (pin "T6") (pinfunction "IOB_73_T6") (pintype "bidirectional"))
    )
    (net (code "91") (name "MC02_SYSCLK") (class "Default")
      (node (ref "TP1") (pin "TP") (pinfunction "TP_TP") (pintype "input"))
      (node (ref "U2") (pin "R9") (pinfunction "IOB_81_GBIN5_R9") (pintype "bidirectional"))
      (node (ref "U9") (pin "99") (pinfunction "PC9/I2S_CKIN/MC02/TIM8_CH4/SDIO_D1/I2C3_SDA/DCMI_D3/TIM3_CH4/EVENTOUT_99") (pintype "passive"))
    )
    (net (code "92") (name "MCLK") (class "Default")
      (node (ref "R60") (pin "2") (pinfunction "2_2") (pintype "passive"))
      (node (ref "U2") (pin "T5") (pinfunction "IOB_69_T5") (pintype "bidirectional"))
    )
    (net (code "93") (name "MCU_RX_UART3") (class "Default")
      (node (ref "U8") (pin "15") (pinfunction "TXD_15") (pintype "output"))
      (node (ref "U9") (pin "70") (pinfunction "PB11/I2C2_SDA/USART3_RX/OTG_HS_ULPI_D4/ETH_RMII_TX_EN/ETH_MII_TX_EN/TIM2_CH4/EVENTOUT_70") (pintype "passive"))
    )
    (net (code "94") (name "MCU_SPI3_MISO") (class "Default")
      (node (ref "R62") (pin "2") (pinfunction "2_2") (pintype "passive"))
      (node (ref "U10") (pin "2") (pinfunction "SO_2") (pintype "output"))
      (node (ref "U2") (pin "N12") (pinfunction "IOB_98_N12") (pintype "bidirectional"))
      (node (ref "U9") (pin "112") (pinfunction "PC11/UART4_RX/SPI3_MISO/SDIO_D3/DCMI_D4/USART3_RX/I2S3EXT_SD/EVENTOUT_112") (pintype "passive"))
    )
    (net (code "95") (name "MCU_SPI3_MOSI") (class "Default")
      (node (ref "U10") (pin "5") (pinfunction "SI_5") (pintype "input"))
      (node (ref "U2") (pin "P10") (pinfunction "IOB_86_P10") (pintype "bidirectional"))
      (node (ref "U2") (pin "P11") (pinfunction "IOB_106_SDI_P11") (pintype "bidirectional"))
      (node (ref "U9") (pin "113") (pinfunction "PC12/UART5_TX/SDIO_CK/DCMI_D9/SPI3_MOSI/I2S3_SD/USART3_CK/EVENTOUT_113") (pintype "passive"))
    )
    (net (code "96") (name "MCU_SPI3_SCLK") (class "Default")
      (node (ref "U10") (pin "6") (pinfunction "SCK_6") (pintype "input"))
      (node (ref "U2") (pin "R10") (pinfunction "IOB_84_R10") (pintype "bidirectional"))
      (node (ref "U2") (pin "R11") (pinfunction "IOB_107_SCK_R11") (pintype "bidirectional"))
      (node (ref "U9") (pin "111") (pinfunction "PC10/SPI3_SCK/I2S3_CK/UART4_TX/SDIO_D2/DCMI_D8/USART3_TX/EVENTOUT_111") (pintype "passive"))
    )
    (net (code "97") (name "MCU_TX_UART3") (class "Default")
      (node (ref "U8") (pin "2") (pinfunction "RXD_2") (pintype "input"))
      (node (ref "U9") (pin "69") (pinfunction "PB10/SPI2_SCK/I2S2_CK/I2C2_SCL/USART3_TX/OTG_HS_ULPI_D3/ETH_MII_RX_ER/TIM2_CH3/EVENTOUT_69") (pintype "passive"))
    )
    (net (code "98") (name "MIC_CLK") (class "Default")
      (node (ref "U11") (pin "3") (pinfunction "CLK_3") (pintype "passive"))
      (node (ref "U2") (pin "R6") (pinfunction "IOB_71_R6") (pintype "bidirectional"))
    )
    (net (code "99") (name "MIC_DOUT") (class "Default")
      (node (ref "U11") (pin "4") (pinfunction "DOUT_4") (pintype "passive"))
      (node (ref "U2") (pin "R5") (pinfunction "IOB_60_R5") (pintype "bidirectional"))
    )
    (net (code "100") (name "Net-(C40-A)") (class "Default")
      (node (ref "C40") (pin "1") (pinfunction "A_1") (pintype "passive"))
      (node (ref "C99") (pin "1") (pinfunction "A_1") (pintype "passive"))
      (node (ref "L19") (pin "2") (pinfunction "2_2") (pintype "passive"))
      (node (ref "U9") (pin "32") (pinfunction "VREF+_32") (pintype "passive"))
      (node (ref "U9") (pin "33") (pinfunction "VDDA_33") (pintype "passive"))
    )
    (net (code "101") (name "Net-(C75-Pad1)") (class "Default")
      (node (ref "C75") (pin "1") (pinfunction "1_1") (pintype "passive"))
      (node (ref "R37") (pin "2") (pinfunction "2_2") (pintype "passive"))
      (node (ref "R5") (pin "1") (pinfunction "1_1") (pintype "passive"))
    )
    (net (code "102") (name "Net-(C77-Pad1)") (class "Default")
      (node (ref "C77") (pin "1") (pinfunction "1_1") (pintype "passive"))
      (node (ref "R2") (pin "1") (pinfunction "1_1") (pintype "passive"))
      (node (ref "R38") (pin "2") (pinfunction "2_2") (pintype "passive"))
    )
    (net (code "103") (name "Net-(D1-PadC)") (class "Default")
      (node (ref "D1") (pin "C") (pinfunction "C_C") (pintype "passive"))
      (node (ref "R10") (pin "1") (pinfunction "1_1") (pintype "passive"))
    )
    (net (code "104") (name "Net-(D2-PadC)") (class "Default")
      (node (ref "D2") (pin "C") (pinfunction "C_C") (pintype "passive"))
      (node (ref "R6") (pin "1") (pinfunction "1_1") (pintype "passive"))
    )
    (net (code "105") (name "Net-(D5-PadA)") (class "Default")
      (node (ref "D5") (pin "A") (pinfunction "A_A") (pintype "passive"))
      (node (ref "D6") (pin "A") (pinfunction "A_A") (pintype "passive"))
      (node (ref "D7") (pin "A") (pinfunction "A_A") (pintype "passive"))
      (node (ref "R61") (pin "2") (pinfunction "2_2") (pintype "passive"))
    )
    (net (code "106") (name "Net-(J1-C)") (class "Default")
      (node (ref "J1") (pin "C1") (pinfunction "C_C1") (pintype "passive"))
      (node (ref "R25") (pin "1") (pinfunction "1_1") (pintype "passive"))
    )
    (net (code "107") (name "Net-(J1-C1)") (class "Default")
      (node (ref "J1") (pin "C2") (pinfunction "C1_C2") (pintype "passive"))
      (node (ref "R24") (pin "1") (pinfunction "1_1") (pintype "passive"))
    )
    (net (code "108") (name "Net-(JP2-2)") (class "Default")
      (node (ref "JP2") (pin "7") (pinfunction "2_7") (pintype "passive"))
      (node (ref "R46") (pin "1") (pinfunction "1_1") (pintype "passive"))
    )
    (net (code "109") (name "Net-(JP2-3)") (class "Default")
      (node (ref "JP2") (pin "2") (pinfunction "3_2") (pintype "passive"))
      (node (ref "R43") (pin "2") (pinfunction "2_2") (pintype "passive"))
    )
    (net (code "110") (name "Net-(JP2-4)") (class "Default")
      (node (ref "JP2") (pin "8") (pinfunction "4_8") (pintype "passive"))
      (node (ref "R47") (pin "1") (pinfunction "1_1") (pintype "passive"))
    )
    (net (code "111") (name "Net-(JP2-5)") (class "Default")
      (node (ref "JP2") (pin "3") (pinfunction "5_3") (pintype "passive"))
      (node (ref "R44") (pin "2") (pinfunction "2_2") (pintype "passive"))
    )
    (net (code "112") (name "Net-(JP2-6)") (class "Default")
      (node (ref "JP2") (pin "9") (pinfunction "6_9") (pintype "passive"))
      (node (ref "R48") (pin "1") (pinfunction "1_1") (pintype "passive"))
    )
    (net (code "113") (name "Net-(JP2-7)") (class "Default")
      (node (ref "JP2") (pin "4") (pinfunction "7_4") (pintype "passive"))
      (node (ref "R45") (pin "2") (pinfunction "2_2") (pintype "passive"))
    )
    (net (code "114") (name "Net-(JP2-8)") (class "Default")
      (node (ref "JP2") (pin "10") (pinfunction "8_10") (pintype "passive"))
      (node (ref "R51") (pin "1") (pinfunction "1_1") (pintype "passive"))
    )
    (net (code "115") (name "Net-(JP2-Pad1)") (class "Default")
      (node (ref "JP2") (pin "1") (pinfunction "1_1") (pintype "passive"))
      (node (ref "R42") (pin "2") (pinfunction "2_2") (pintype "passive"))
    )
    (net (code "116") (name "Net-(JP5-2)") (class "Default")
      (node (ref "JP5") (pin "7") (pinfunction "2_7") (pintype "passive"))
      (node (ref "R14") (pin "1") (pinfunction "1_1") (pintype "passive"))
    )
    (net (code "117") (name "Net-(JP5-3)") (class "Default")
      (node (ref "JP5") (pin "2") (pinfunction "3_2") (pintype "passive"))
      (node (ref "R11") (pin "2") (pinfunction "2_2") (pintype "passive"))
    )
    (net (code "118") (name "Net-(JP5-4)") (class "Default")
      (node (ref "JP5") (pin "8") (pinfunction "4_8") (pintype "passive"))
      (node (ref "R15") (pin "1") (pinfunction "1_1") (pintype "passive"))
    )
    (net (code "119") (name "Net-(JP5-5)") (class "Default")
      (node (ref "JP5") (pin "3") (pinfunction "5_3") (pintype "passive"))
      (node (ref "R12") (pin "2") (pinfunction "2_2") (pintype "passive"))
    )
    (net (code "120") (name "Net-(JP5-6)") (class "Default")
      (node (ref "JP5") (pin "9") (pinfunction "6_9") (pintype "passive"))
      (node (ref "R16") (pin "1") (pinfunction "1_1") (pintype "passive"))
    )
    (net (code "121") (name "Net-(JP5-7)") (class "Default")
      (node (ref "JP5") (pin "4") (pinfunction "7_4") (pintype "passive"))
      (node (ref "R13") (pin "2") (pinfunction "2_2") (pintype "passive"))
    )
    (net (code "122") (name "Net-(JP5-8)") (class "Default")
      (node (ref "JP5") (pin "10") (pinfunction "8_10") (pintype "passive"))
      (node (ref "R17") (pin "1") (pinfunction "1_1") (pintype "passive"))
    )
    (net (code "123") (name "Net-(JP5-Pad1)") (class "Default")
      (node (ref "JP5") (pin "1") (pinfunction "1_1") (pintype "passive"))
      (node (ref "R9") (pin "2") (pinfunction "2_2") (pintype "passive"))
    )
    (net (code "124") (name "Net-(JP6-2)") (class "Default")
      (node (ref "JP6") (pin "7") (pinfunction "2_7") (pintype "passive"))
      (node (ref "R22") (pin "1") (pinfunction "1_1") (pintype "passive"))
    )
    (net (code "125") (name "Net-(JP6-3)") (class "Default")
      (node (ref "JP6") (pin "2") (pinfunction "3_2") (pintype "passive"))
      (node (ref "R19") (pin "2") (pinfunction "2_2") (pintype "passive"))
    )
    (net (code "126") (name "Net-(JP6-4)") (class "Default")
      (node (ref "JP6") (pin "8") (pinfunction "4_8") (pintype "passive"))
      (node (ref "R27") (pin "1") (pinfunction "1_1") (pintype "passive"))
    )
    (net (code "127") (name "Net-(JP6-5)") (class "Default")
      (node (ref "JP6") (pin "3") (pinfunction "5_3") (pintype "passive"))
      (node (ref "R20") (pin "2") (pinfunction "2_2") (pintype "passive"))
    )
    (net (code "128") (name "Net-(JP6-6)") (class "Default")
      (node (ref "JP6") (pin "9") (pinfunction "6_9") (pintype "passive"))
      (node (ref "R28") (pin "1") (pinfunction "1_1") (pintype "passive"))
    )
    (net (code "129") (name "Net-(JP6-7)") (class "Default")
      (node (ref "JP6") (pin "4") (pinfunction "7_4") (pintype "passive"))
      (node (ref "R21") (pin "2") (pinfunction "2_2") (pintype "passive"))
    )
    (net (code "130") (name "Net-(JP6-8)") (class "Default")
      (node (ref "JP6") (pin "10") (pinfunction "8_10") (pintype "passive"))
      (node (ref "R29") (pin "1") (pinfunction "1_1") (pintype "passive"))
    )
    (net (code "131") (name "Net-(JP6-Pad1)") (class "Default")
      (node (ref "JP6") (pin "1") (pinfunction "1_1") (pintype "passive"))
      (node (ref "R18") (pin "2") (pinfunction "2_2") (pintype "passive"))
    )
    (net (code "132") (name "Net-(JP7-2)") (class "Default")
      (node (ref "JP7") (pin "7") (pinfunction "2_7") (pintype "passive"))
      (node (ref "R34") (pin "1") (pinfunction "1_1") (pintype "passive"))
    )
    (net (code "133") (name "Net-(JP7-3)") (class "Default")
      (node (ref "JP7") (pin "2") (pinfunction "3_2") (pintype "passive"))
      (node (ref "R31") (pin "2") (pinfunction "2_2") (pintype "passive"))
    )
    (net (code "134") (name "Net-(JP7-4)") (class "Default")
      (node (ref "JP7") (pin "8") (pinfunction "4_8") (pintype "passive"))
      (node (ref "R39") (pin "1") (pinfunction "1_1") (pintype "passive"))
    )
    (net (code "135") (name "Net-(JP7-5)") (class "Default")
      (node (ref "JP7") (pin "3") (pinfunction "5_3") (pintype "passive"))
      (node (ref "R32") (pin "2") (pinfunction "2_2") (pintype "passive"))
    )
    (net (code "136") (name "Net-(JP7-6)") (class "Default")
      (node (ref "JP7") (pin "9") (pinfunction "6_9") (pintype "passive"))
      (node (ref "R40") (pin "1") (pinfunction "1_1") (pintype "passive"))
    )
    (net (code "137") (name "Net-(JP7-7)") (class "Default")
      (node (ref "JP7") (pin "4") (pinfunction "7_4") (pintype "passive"))
      (node (ref "R33") (pin "2") (pinfunction "2_2") (pintype "passive"))
    )
    (net (code "138") (name "Net-(JP7-8)") (class "Default")
      (node (ref "JP7") (pin "10") (pinfunction "8_10") (pintype "passive"))
      (node (ref "R41") (pin "1") (pinfunction "1_1") (pintype "passive"))
    )
    (net (code "139") (name "Net-(JP7-Pad1)") (class "Default")
      (node (ref "JP7") (pin "1") (pinfunction "1_1") (pintype "passive"))
      (node (ref "R30") (pin "2") (pinfunction "2_2") (pintype "passive"))
    )
    (net (code "140") (name "Net-(Q17-D)") (class "Default")
      (node (ref "Q17") (pin "3") (pinfunction "D_3") (pintype "passive"))
      (node (ref "R52") (pin "2") (pinfunction "2_2") (pintype "passive"))
      (node (ref "R53") (pin "2") (pinfunction "2_2") (pintype "passive"))
      (node (ref "R54") (pin "2") (pinfunction "2_2") (pintype "passive"))
    )
    (net (code "141") (name "Net-(U7--DEM{slash}SCLK)") (class "Default")
      (node (ref "R58") (pin "1") (pinfunction "1_1") (pintype "passive"))
      (node (ref "U7") (pin "2") (pinfunction "-DEM/SCLK_2") (pintype "input"))
    )
    (net (code "142") (name "Net-(U7-AOUTL)") (class "Default")
      (node (ref "C75") (pin "2") (pinfunction "2_2") (pintype "passive"))
      (node (ref "U7") (pin "7") (pinfunction "AOUTL_7") (pintype "output"))
    )
    (net (code "143") (name "Net-(U7-AOUTR)") (class "Default")
      (node (ref "C77") (pin "2") (pinfunction "2_2") (pintype "passive"))
      (node (ref "U7") (pin "10") (pinfunction "AOUTR_10") (pintype "output"))
    )
    (net (code "144") (name "Net-(U7-FILT+)") (class "Default")
      (node (ref "C73") (pin "2") (pinfunction "2_2") (pintype "passive"))
      (node (ref "U7") (pin "6") (pinfunction "FILT+_6") (pintype "passive"))
    )
    (net (code "145") (name "Net-(U7-LRCLK)") (class "Default")
      (node (ref "R59") (pin "1") (pinfunction "1_1") (pintype "passive"))
      (node (ref "U7") (pin "3") (pinfunction "LRCLK_3") (pintype "input"))
    )
    (net (code "146") (name "Net-(U7-MCLK)") (class "Default")
      (node (ref "R60") (pin "1") (pinfunction "1_1") (pintype "passive"))
      (node (ref "U7") (pin "4") (pinfunction "MCLK_4") (pintype "input"))
    )
    (net (code "147") (name "Net-(U7-SDIN)") (class "Default")
      (node (ref "R57") (pin "1") (pinfunction "1_1") (pintype "passive"))
      (node (ref "U7") (pin "1") (pinfunction "SDIN_1") (pintype "input"))
    )
    (net (code "148") (name "Net-(U7-VA)") (class "Default")
      (node (ref "C74") (pin "1") (pinfunction "1_1") (pintype "passive"))
      (node (ref "L17") (pin "1") (pinfunction "1_1") (pintype "passive"))
      (node (ref "U7") (pin "9") (pinfunction "VA_9") (pintype "power_in"))
    )
    (net (code "149") (name "Net-(U7-VQ)") (class "Default")
      (node (ref "C71") (pin "1") (pinfunction "1_1") (pintype "passive"))
      (node (ref "C72") (pin "1") (pinfunction "1_1") (pintype "passive"))
      (node (ref "U7") (pin "5") (pinfunction "VQ_5") (pintype "passive"))
    )
    (net (code "150") (name "Net-(U8-3V3OUT)") (class "Default")
      (node (ref "C2") (pin "1") (pinfunction "1_1") (pintype "passive"))
      (node (ref "U8") (pin "1") (pinfunction "VCCIO_1") (pintype "power_in"))
      (node (ref "U8") (pin "8") (pinfunction "3V3OUT_8") (pintype "output"))
      (node (ref "U8") (pin "9") (pinfunction "~{RESET}_9") (pintype "input"))
    )
    (net (code "151") (name "Net-(U9B-PE2{slash}TRACECLK{slash}FSMC_A23{slash}ETH_MII_TXD3{slash}EVENTOUT)") (class "Default")
      (node (ref "D7") (pin "C") (pinfunction "C_C") (pintype "passive"))
      (node (ref "U9") (pin "1") (pinfunction "PE2/TRACECLK/FSMC_A23/ETH_MII_TXD3/EVENTOUT_1") (pintype "passive"))
    )
    (net (code "152") (name "Net-(U9B-PE3{slash}TRACED0{slash}FSMC_A19{slash}EVENTOUT)") (class "Default")
      (node (ref "D6") (pin "C") (pinfunction "C_C") (pintype "passive"))
      (node (ref "U9") (pin "2") (pinfunction "PE3/TRACED0/FSMC_A19/EVENTOUT_2") (pintype "passive"))
    )
    (net (code "153") (name "Net-(U9B-PE4{slash}TRACED1{slash}FSMC_A20{slash}DCMI_D4{slash}EVENTOUT)") (class "Default")
      (node (ref "D5") (pin "C") (pinfunction "C_C") (pintype "passive"))
      (node (ref "U9") (pin "3") (pinfunction "PE4/TRACED1/FSMC_A20/DCMI_D4/EVENTOUT_3") (pintype "passive"))
    )
    (net (code "154") (name "Net-(U9C-PH0-OSC_IN{slash}EVENTOUT)") (class "Default")
      (node (ref "C21") (pin "2") (pinfunction "2_2") (pintype "passive"))
      (node (ref "U9") (pin "23") (pinfunction "PH0-OSC_IN/EVENTOUT_23") (pintype "passive"))
      (node (ref "X2") (pin "1") (pinfunction "P$1_1") (pintype "passive"))
    )
    (net (code "155") (name "Net-(U9C-PH1-OSC_OUT{slash}EVENTOUT)") (class "Default")
      (node (ref "C5") (pin "2") (pinfunction "2_2") (pintype "passive"))
      (node (ref "U9") (pin "24") (pinfunction "PH1-OSC_OUT/EVENTOUT_24") (pintype "passive"))
      (node (ref "X2") (pin "3") (pinfunction "P$2_3") (pintype "passive"))
    )
    (net (code "156") (name "Net-(U9C-VCAP_1)") (class "Default")
      (node (ref "C100") (pin "1") (pinfunction "1_1") (pintype "passive"))
      (node (ref "U9") (pin "71") (pinfunction "VCAP_1_71") (pintype "passive"))
    )
    (net (code "157") (name "Net-(U9C-VCAP_2)") (class "Default")
      (node (ref "C102") (pin "1") (pinfunction "1_1") (pintype "passive"))
      (node (ref "U9") (pin "106") (pinfunction "VCAP_2_106") (pintype "passive"))
    )
    (net (code "158") (name "Net-(U12-BYP)") (class "Default")
      (node (ref "C107") (pin "1") (pinfunction "1_1") (pintype "passive"))
      (node (ref "U12") (pin "3") (pinfunction "BYP_3") (pintype "passive"))
    )
    (net (code "159") (name "Net-(U12-REF)") (class "Default")
      (node (ref "C109") (pin "1") (pinfunction "1_1") (pintype "passive"))
      (node (ref "U12") (pin "5") (pinfunction "REF_SENSE_5") (pintype "passive"))
      (node (ref "U12") (pin "6") (pinfunction "REF_6") (pintype "passive"))
    )
    (net (code "160") (name "Net-(U12-VOUT)") (class "Default")
      (node (ref "C106") (pin "A") (pinfunction "A_A") (pintype "passive"))
      (node (ref "L20") (pin "1") (pinfunction "1_1") (pintype "passive"))
      (node (ref "U12") (pin "1") (pinfunction "VOUT_1") (pintype "passive"))
      (node (ref "U12") (pin "2") (pinfunction "VOUT_SENSE_2") (pintype "passive"))
    )
    (net (code "161") (name "Net-(U12-VREG)") (class "Default")
      (node (ref "C110") (pin "1") (pinfunction "1_1") (pintype "passive"))
      (node (ref "U12") (pin "7") (pinfunction "VREG_7") (pintype "passive"))
    )
    (net (code "162") (name "Net-(U18-RBIAS)") (class "Default")
      (node (ref "R26") (pin "1") (pinfunction "1_1") (pintype "passive"))
      (node (ref "U18") (pin "24") (pinfunction "RBIAS_24") (pintype "passive"))
    )
    (net (code "163") (name "Net-(U18-VDDCR)") (class "Default")
      (node (ref "C66") (pin "1") (pinfunction "1_1") (pintype "passive"))
      (node (ref "C67") (pin "1") (pinfunction "1_1") (pintype "passive"))
      (node (ref "U18") (pin "6") (pinfunction "VDDCR_6") (pintype "passive"))
    )
    (net (code "164") (name "Net-(U18-XTAL1{slash}CLKIN)") (class "Default")
      (node (ref "C128") (pin "2") (pinfunction "2_2") (pintype "passive"))
      (node (ref "U18") (pin "5") (pinfunction "XTAL1/CLKIN_5") (pintype "passive"))
      (node (ref "X1") (pin "1") (pinfunction "P$1_1") (pintype "passive"))
    )
    (net (code "165") (name "Net-(U18-XTAL2)") (class "Default")
      (node (ref "C129") (pin "2") (pinfunction "2_2") (pintype "passive"))
      (node (ref "U18") (pin "4") (pinfunction "XTAL2_4") (pintype "passive"))
      (node (ref "X1") (pin "3") (pinfunction "P$2_3") (pintype "passive"))
    )
    (net (code "166") (name "PLL_VCC_1V2") (class "Default")
      (node (ref "C8") (pin "A") (pinfunction "A_A") (pintype "passive"))
      (node (ref "C9") (pin "1") (pinfunction "1_1") (pintype "passive"))
      (node (ref "L1") (pin "2") (pinfunction "2_2") (pintype "passive"))
      (node (ref "U2") (pin "E8") (pinfunction "VCCPLL1_E8") (pintype "power_in"))
      (node (ref "U2") (pin "L8") (pinfunction "VCCPLL0_L8") (pintype "power_in"))
    )
    (net (code "167") (name "PMOD1_1") (class "Default")
      (node (ref "R42") (pin "1") (pinfunction "1_1") (pintype "passive"))
      (node (ref "U2") (pin "P2") (pinfunction "IOL_25A_P2") (pintype "bidirectional"))
    )
    (net (code "168") (name "PMOD1_2") (class "Default")
      (node (ref "R43") (pin "1") (pinfunction "1_1") (pintype "passive"))
      (node (ref "U2") (pin "R2") (pinfunction "IOB_55_R2") (pintype "bidirectional"))
    )
    (net (code "169") (name "PMOD1_3") (class "Default")
      (node (ref "R44") (pin "1") (pinfunction "1_1") (pintype "passive"))
      (node (ref "U2") (pin "T1") (pinfunction "IOB_53_T1") (pintype "bidirectional"))
    )
    (net (code "170") (name "PMOD1_4") (class "Default")
      (node (ref "R45") (pin "1") (pinfunction "1_1") (pintype "passive"))
      (node (ref "U2") (pin "T3") (pinfunction "IOB_61_T3") (pintype "bidirectional"))
    )
    (net (code "171") (name "PMOD1_7") (class "Default")
      (node (ref "R46") (pin "2") (pinfunction "2_2") (pintype "passive"))
      (node (ref "U2") (pin "P1") (pinfunction "IOL_24A_P1") (pintype "bidirectional"))
    )
    (net (code "172") (name "PMOD1_8") (class "Default")
      (node (ref "R47") (pin "2") (pinfunction "2_2") (pintype "passive"))
      (node (ref "U2") (pin "R1") (pinfunction "IOL_26A_R1") (pintype "bidirectional"))
    )
    (net (code "173") (name "PMOD1_9") (class "Default")
      (node (ref "R48") (pin "2") (pinfunction "2_2") (pintype "passive"))
      (node (ref "U2") (pin "R3") (pinfunction "IOB_59_R3") (pintype "bidirectional"))
    )
    (net (code "174") (name "PMOD1_10") (class "Default")
      (node (ref "R51") (pin "2") (pinfunction "2_2") (pintype "passive"))
      (node (ref "U2") (pin "T2") (pinfunction "IOB_57_T2") (pintype "bidirectional"))
    )
    (net (code "175") (name "PMOD2_1") (class "Default")
      (node (ref "R30") (pin "1") (pinfunction "1_1") (pintype "passive"))
      (node (ref "U2") (pin "K1") (pinfunction "IOL_16A_K1") (pintype "bidirectional"))
    )
    (net (code "176") (name "PMOD2_2") (class "Default")
      (node (ref "R31") (pin "1") (pinfunction "1_1") (pintype "passive"))
      (node (ref "U2") (pin "L3") (pinfunction "IOL_19B_L3") (pintype "bidirectional"))
    )
    (net (code "177") (name "PMOD2_3") (class "Default")
      (node (ref "R32") (pin "1") (pinfunction "1_1") (pintype "passive"))
      (node (ref "U2") (pin "M2") (pinfunction "IOL_20B_M2") (pintype "bidirectional"))
    )
    (net (code "178") (name "PMOD2_4") (class "Default")
      (node (ref "R33") (pin "1") (pinfunction "1_1") (pintype "passive"))
      (node (ref "U2") (pin "N3") (pinfunction "IOL_23B_N3") (pintype "bidirectional"))
    )
    (net (code "179") (name "PMOD2_7") (class "Default")
      (node (ref "R34") (pin "2") (pinfunction "2_2") (pintype "passive"))
      (node (ref "U2") (pin "K3") (pinfunction "IOL_16B_K3") (pintype "bidirectional"))
    )
    (net (code "180") (name "PMOD2_8") (class "Default")
      (node (ref "R39") (pin "2") (pinfunction "2_2") (pintype "passive"))
      (node (ref "U2") (pin "L1") (pinfunction "IOL_17B_L1") (pintype "bidirectional"))
    )
    (net (code "181") (name "PMOD2_9") (class "Default")
      (node (ref "R40") (pin "2") (pinfunction "2_2") (pintype "passive"))
      (node (ref "U2") (pin "M1") (pinfunction "IOL_18B_M1") (pintype "bidirectional"))
    )
    (net (code "182") (name "PMOD2_10") (class "Default")
      (node (ref "R41") (pin "2") (pinfunction "2_2") (pintype "passive"))
      (node (ref "U2") (pin "N2") (pinfunction "IOL_21B_N2") (pintype "bidirectional"))
    )
    (net (code "183") (name "PMOD3_1") (class "Default")
      (node (ref "R18") (pin "1") (pinfunction "1_1") (pintype "passive"))
      (node (ref "U2") (pin "F2") (pinfunction "IOL_9B_F2") (pintype "bidirectional"))
    )
    (net (code "184") (name "PMOD3_2") (class "Default")
      (node (ref "R19") (pin "1") (pinfunction "1_1") (pintype "passive"))
      (node (ref "U2") (pin "G3") (pinfunction "IOL_8A_G3") (pintype "bidirectional"))
    )
    (net (code "185") (name "PMOD3_3") (class "Default")
      (node (ref "R20") (pin "1") (pinfunction "1_1") (pintype "passive"))
      (node (ref "U2") (pin "H1") (pinfunction "IOL_14B_H1") (pintype "bidirectional"))
    )
    (net (code "186") (name "PMOD3_4") (class "Default")
      (node (ref "R21") (pin "1") (pinfunction "1_1") (pintype "passive"))
      (node (ref "U2") (pin "J2") (pinfunction "IOL_15A_J2") (pintype "bidirectional"))
    )
    (net (code "187") (name "PMOD3_7") (class "Default")
      (node (ref "R22") (pin "2") (pinfunction "2_2") (pintype "passive"))
      (node (ref "U2") (pin "F1") (pinfunction "IOL_10B_F1") (pintype "bidirectional"))
    )
    (net (code "188") (name "PMOD3_8") (class "Default")
      (node (ref "R27") (pin "2") (pinfunction "2_2") (pintype "passive"))
      (node (ref "U2") (pin "G2") (pinfunction "IOL_11B_G2") (pintype "bidirectional"))
    )
    (net (code "189") (name "PMOD3_9") (class "Default")
      (node (ref "R28") (pin "2") (pinfunction "2_2") (pintype "passive"))
      (node (ref "U2") (pin "H2") (pinfunction "IOL_12B_H2") (pintype "bidirectional"))
    )
    (net (code "190") (name "PMOD3_10") (class "Default")
      (node (ref "R29") (pin "2") (pinfunction "2_2") (pintype "passive"))
      (node (ref "U2") (pin "J1") (pinfunction "IOL_15B_J1") (pintype "bidirectional"))
    )
    (net (code "191") (name "PMOD4_1") (class "Default")
      (node (ref "R9") (pin "1") (pinfunction "1_1") (pintype "passive"))
      (node (ref "U2") (pin "B3") (pinfunction "IOT_223_B3") (pintype "bidirectional"))
    )
    (net (code "192") (name "PMOD4_2") (class "Default")
      (node (ref "R11") (pin "1") (pinfunction "1_1") (pintype "passive"))
      (node (ref "U2") (pin "C3") (pinfunction "IOT_227_C3") (pintype "bidirectional"))
    )
    (net (code "193") (name "PMOD4_3") (class "Default")
      (node (ref "R12") (pin "1") (pinfunction "1_1") (pintype "passive"))
      (node (ref "U2") (pin "D3") (pinfunction "IOT_226_D3") (pintype "bidirectional"))
    )
    (net (code "194") (name "PMOD4_4") (class "Default")
      (node (ref "R13") (pin "1") (pinfunction "1_1") (pintype "passive"))
      (node (ref "U2") (pin "E3") (pinfunction "IOL_6B_E3") (pintype "bidirectional"))
    )
    (net (code "195") (name "PMOD4_7") (class "Default")
      (node (ref "R14") (pin "2") (pinfunction "2_2") (pintype "passive"))
      (node (ref "U2") (pin "B2") (pinfunction "IOL_1B_B2") (pintype "bidirectional"))
    )
    (net (code "196") (name "PMOD4_8") (class "Default")
      (node (ref "R15") (pin "2") (pinfunction "2_2") (pintype "passive"))
      (node (ref "U2") (pin "C2") (pinfunction "IOL_3B_C2") (pintype "bidirectional"))
    )
    (net (code "197") (name "PMOD4_9") (class "Default")
      (node (ref "R16") (pin "2") (pinfunction "2_2") (pintype "passive"))
      (node (ref "U2") (pin "D2") (pinfunction "IOL_4B_D2") (pintype "bidirectional"))
    )
    (net (code "198") (name "PMOD4_10") (class "Default")
      (node (ref "R17") (pin "2") (pinfunction "2_2") (pintype "passive"))
      (node (ref "U2") (pin "E2") (pinfunction "IOL_7B_E2") (pintype "bidirectional"))
    )
    (net (code "199") (name "RDB") (class "Default")
      (node (ref "J3") (pin "8") (pinfunction "S_8") (pintype "passive"))
      (node (ref "U2") (pin "A5") (pinfunction "IOT_213_A5") (pintype "bidirectional"))
    )
    (net (code "200") (name "RMII_MDC") (class "Default")
      (node (ref "U18") (pin "13") (pinfunction "MDC_13") (pintype "passive"))
      (node (ref "U9") (pin "27") (pinfunction "PC1/ETH_MDC/EVENTOUT/ADC123_IN11_27") (pintype "passive"))
    )
    (net (code "201") (name "RMII_MDIO") (class "Default")
      (node (ref "R102") (pin "2") (pinfunction "2_2") (pintype "passive"))
      (node (ref "U18") (pin "12") (pinfunction "MDIO_12") (pintype "passive"))
      (node (ref "U9") (pin "36") (pinfunction "PA2/USART2_TX/TIM5_CH3/TIM9_CH1/TIM2_CH3/ETH_MDIO/EVENTOUT/ADC123_IN2_36") (pintype "passive"))
    )
    (net (code "202") (name "RMII_RXD_0") (class "Default")
      (node (ref "R103") (pin "2") (pinfunction "2_2") (pintype "passive"))
      (node (ref "U18") (pin "8") (pinfunction "RXD0/MODE0_8") (pintype "passive"))
      (node (ref "U9") (pin "44") (pinfunction "PC4/ETH_RMII_RX_D0/ETH_MII_RX_D0/ADC12_IN14_44") (pintype "passive"))
    )
    (net (code "203") (name "RMII_RXD_1") (class "Default")
      (node (ref "R77") (pin "2") (pinfunction "2_2") (pintype "passive"))
      (node (ref "U18") (pin "7") (pinfunction "RXD1/MODE1_7") (pintype "passive"))
      (node (ref "U9") (pin "45") (pinfunction "PC5/ETH_RMII_RX_D1/ETH_MII_RX_D1/EVENTOUT/ADC12_IN15_45") (pintype "passive"))
    )
    (net (code "204") (name "RMII_RX_DV") (class "Default")
      (node (ref "R75") (pin "2") (pinfunction "2_2") (pintype "passive"))
      (node (ref "U18") (pin "11") (pinfunction "CRS_DV/MODE2_11") (pintype "passive"))
      (node (ref "U9") (pin "43") (pinfunction "PA7/SPI1_MOSI/TIM8_CH1N/TIM14_CH1/TIM3_CH2/ETH_MII_RX_DV/TIM1_CH1N/RMII_CRS_DV/EVENTOUT/ADC12_IN7_43") (pintype "passive"))
    )
    (net (code "205") (name "RMII_TXD_0") (class "Default")
      (node (ref "U18") (pin "17") (pinfunction "TXD0_17") (pintype "passive"))
      (node (ref "U9") (pin "128") (pinfunction "PG13/FSMC_A24/USART6_CTS/ETH_MII_TXD0/ETH_RMII_TXD0/EVENTOUT_128") (pintype "passive"))
    )
    (net (code "206") (name "RMII_TXD_1") (class "Default")
      (node (ref "U18") (pin "18") (pinfunction "TXD1_18") (pintype "passive"))
      (node (ref "U9") (pin "129") (pinfunction "PG14/FSMC_A25/USART6_TX/ETH_MII_TXD1/ETH_RMII_TXD1/EVENTOUT_129") (pintype "passive"))
    )
    (net (code "207") (name "RMII_TXD_EN") (class "Default")
      (node (ref "U18") (pin "16") (pinfunction "TXEN_16") (pintype "passive"))
      (node (ref "U9") (pin "126") (pinfunction "PG11/FSMC_NCE4_2/ETH_MII_TX_EN/ETH_RMII_TX_EN/EVENTOUT_126") (pintype "passive"))
    )
    (net (code "208") (name "RS") (class "Default")
      (node (ref "J3") (pin "6") (pinfunction "S_6") (pintype "passive"))
      (node (ref "U2") (pin "B11") (pinfunction "IOT_184_B11") (pintype "bidirectional"))
    )
    (net (code "209") (name "RST") (class "Default")
      (node (ref "J3") (pin "5") (pinfunction "S_5") (pintype "passive"))
      (node (ref "U2") (pin "B4") (pinfunction "IOT_216_B4") (pintype "bidirectional"))
    )
    (net (code "210") (name "RXER_ADDR0") (class "Default")
      (node (ref "R104") (pin "1") (pinfunction "1_1") (pintype "passive"))
      (node (ref "U18") (pin "10") (pinfunction "RXER/PHYAD0_10") (pintype "passive"))
    )
    (net (code "211") (name "SCLK") (class "Default")
      (node (ref "R58") (pin "2") (pinfunction "2_2") (pintype "passive"))
      (node (ref "U2") (pin "T7") (pinfunction "IOB_75_T7") (pintype "bidirectional"))
    )
    (net (code "212") (name "SD0_DAT1") (class "Default")
      (node (ref "J5") (pin "8") (pinfunction "DATA1_8") (pintype "bidirectional"))
    )
    (net (code "213") (name "SD0_DAT2") (class "Default")
      (node (ref "J5") (pin "1") (pinfunction "DATA2_1") (pintype "bidirectional"))
    )
    (net (code "214") (name "SD0_DAT3") (class "Default")
      (node (ref "J5") (pin "2") (pinfunction "CD/DATA3_2") (pintype "bidirectional"))
    )
    (net (code "215") (name "SD2_CLK") (class "Default")
      (node (ref "J5") (pin "5") (pinfunction "CLK_5") (pintype "bidirectional"))
      (node (ref "U9") (pin "122") (pinfunction "PD6/FSMC_NWAIT/USART2_RX/EVENTOUT_122") (pintype "passive"))
    )
    (net (code "216") (name "SD2_CMD") (class "Default")
      (node (ref "J5") (pin "3") (pinfunction "CMD_3") (pintype "bidirectional"))
      (node (ref "U9") (pin "34") (pinfunction "PA0-WKUP/USART2_CTS/UART4_TX/ETH_MII_CRS/TIM2_CH1_ETR/TIM5_CH1/TIM8_ETR/EVENTOUT/ADC123_IN0_34") (pintype "passive"))
    )
    (net (code "217") (name "SD2_DAT0") (class "Default")
      (node (ref "J5") (pin "7") (pinfunction "DATA0_7") (pintype "bidirectional"))
      (node (ref "U9") (pin "75") (pinfunction "PB14/SPI2_MISO/TIM1_CH2N/TIM12_CH1/OTG_HS_DM/USART3_RTS/TIM8_CH2N/I2S2EXT_SD/EVENTOUT_75") (pintype "passive"))
    )
    (net (code "218") (name "SDIN") (class "Default")
      (node (ref "R57") (pin "2") (pinfunction "2_2") (pintype "passive"))
      (node (ref "U2") (pin "T8") (pinfunction "IOB_76_T8") (pintype "bidirectional"))
    )
    (net (code "219") (name "SWCLK") (class "Default")
      (node (ref "JP1") (pin "2") (pinfunction "2_2") (pintype "passive"))
      (node (ref "U9") (pin "109") (pinfunction "PA14/JTCK-SWCLK/EVENTOUT_109") (pintype "passive"))
    )
    (net (code "220") (name "SWDIO") (class "Default")
      (node (ref "JP1") (pin "4") (pinfunction "4_4") (pintype "passive"))
      (node (ref "U9") (pin "105") (pinfunction "PA13/JTMS-SWDIO/EVENTOUT_105") (pintype "passive"))
    )
    (net (code "221") (name "SWO") (class "Default")
      (node (ref "JP1") (pin "6") (pinfunction "6_6") (pintype "passive"))
      (node (ref "U9") (pin "133") (pinfunction "PB3/JTDO/TRACESWO/SPI3_SCK/I2S3_CK/TIM2_CH2/SPI1_SCK/EVENTOUT_133") (pintype "passive"))
    )
    (net (code "222") (name "TFT_BL_EN") (class "Default")
      (node (ref "Q17") (pin "1") (pinfunction "G_1") (pintype "passive"))
      (node (ref "R7") (pin "1") (pinfunction "1_1") (pintype "passive"))
      (node (ref "U9") (pin "37") (pinfunction "PA3/USART2_RX/TIM5_CH4/TIM9_CH2/TIM2_CH4/OTG_HS_ULPI_D0/ETH_MII_COL/EVENTOUT/ADC123_IN3_37") (pintype "passive"))
    )
    (net (code "223") (name "TOUCH_XL") (class "Default")
      (node (ref "J3") (pin "22") (pinfunction "S_22") (pintype "passive"))
      (node (ref "JP4") (pin "2") (pinfunction "2_2") (pintype "passive"))
      (node (ref "U9") (pin "28") (pinfunction "PC2/SPI2_MISO/OTG_HS_ULPI_DIR/TH_MII_TXD2/I2S2EXT_SD/EVENTOUT/ADC123_IN12_28") (pintype "passive"))
    )
    (net (code "224") (name "TOUCH_XR") (class "Default")
      (node (ref "J3") (pin "24") (pinfunction "S_24") (pintype "passive"))
      (node (ref "JP4") (pin "4") (pinfunction "4_4") (pintype "passive"))
      (node (ref "U9") (pin "29") (pinfunction "PC3/SPI2_MOSI/I2S2_SD/OTG_HS_ULPI_NXT/ETH_MII_TX_CLK/EVENTOUT/ADC123_IN13_29") (pintype "passive"))
    )
    (net (code "225") (name "TOUCH_YD") (class "Default")
      (node (ref "J3") (pin "23") (pinfunction "S_23") (pintype "passive"))
      (node (ref "JP4") (pin "3") (pinfunction "3_3") (pintype "passive"))
      (node (ref "U9") (pin "41") (pinfunction "PA5/SPI1_SCK/OTG_HS_ULPI_CK/TIM2_CH1_ETR/TIM8_CHIN/EVENTOUT/ADC12_IN5/DAC2_OUT_41") (pintype "passive"))
    )
    (net (code "226") (name "TOUCH_YU") (class "Default")
      (node (ref "J3") (pin "21") (pinfunction "S_21") (pintype "passive"))
      (node (ref "JP4") (pin "1") (pinfunction "1_1") (pintype "passive"))
      (node (ref "U9") (pin "40") (pinfunction "PA4/SPI1_NSS/SPI3_NSS/USART2_CK/DCMI_HSYNC/OTG_HS_SOF/I2S3_WS/EVENTOUT/ADC12_IN4/DAC1_OUT_40") (pintype "passive"))
    )
    (net (code "227") (name "USB_DM") (class "Default")
      (node (ref "CON1") (pin "2") (pinfunction "DM_2") (pintype "passive"))
      (node (ref "U8") (pin "7") (pinfunction "USBDM_7") (pintype "input"))
      (node (ref "Z4") (pin "2") (pinfunction "I/O_2") (pintype "passive"))
    )
    (net (code "228") (name "USB_DP") (class "Default")
      (node (ref "CON1") (pin "3") (pinfunction "DP_3") (pintype "passive"))
      (node (ref "U8") (pin "6") (pinfunction "USBDP_6") (pintype "input"))
      (node (ref "Z4") (pin "3") (pinfunction "I/O_3") (pintype "passive"))
    )
    (net (code "229") (name "VBUS") (class "Default")
      (node (ref "C105") (pin "A") (pinfunction "A_A") (pintype "passive"))
      (node (ref "CON1") (pin "1") (pinfunction "VBUS_1") (pintype "passive"))
      (node (ref "L21") (pin "2") (pinfunction "2_2") (pintype "passive"))
      (node (ref "Z4") (pin "4") (pinfunction "REF_4") (pintype "passive"))
    )
    (net (code "230") (name "VPP_2V5") (class "Default")
      (node (ref "C16") (pin "1") (pinfunction "1_1") (pintype "passive"))
      (node (ref "R36") (pin "1") (pinfunction "1_1") (pintype "passive"))
      (node (ref "R49") (pin "1") (pinfunction "1_1") (pintype "passive"))
      (node (ref "U2") (pin "E12") (pinfunction "VPP_2V5_E12") (pintype "power_in"))
    )
    (net (code "231") (name "VPP_FAST") (class "Default")
      (node (ref "U2") (pin "D12") (pinfunction "VPP_FAST_D12") (pintype "power_in"))
    )
    (net (code "232") (name "WRB") (class "Default")
      (node (ref "J3") (pin "7") (pinfunction "S_7") (pintype "passive"))
      (node (ref "U2") (pin "B9") (pinfunction "IOT_199_B9") (pintype "bidirectional"))
    )
    (net (code "233") (name "unconnected-(CON1-ID-Pad4)") (class "Default")
      (node (ref "CON1") (pin "4") (pinfunction "ID_4") (pintype "passive"))
    )
    (net (code "234") (name "unconnected-(J1-NC-Pad7)") (class "Default")
      (node (ref "J1") (pin "7") (pinfunction "NC_7") (pintype "passive"))
    )
    (net (code "235") (name "unconnected-(J5-CD(1)-PadSW)") (class "Default")
      (node (ref "J5") (pin "SW") (pinfunction "CD(1)_SW") (pintype "bidirectional"))
    )
    (net (code "236") (name "unconnected-(J5-CD(2)-PadDET)") (class "Default")
      (node (ref "J5") (pin "DET") (pinfunction "CD(2)_DET") (pintype "bidirectional"))
    )
    (net (code "237") (name "unconnected-(JP1-Pad1)") (class "Default")
      (node (ref "JP1") (pin "1") (pinfunction "1_1") (pintype "passive"))
    )
    (net (code "238") (name "unconnected-(U2A-IOL_1A-PadE4)") (class "Default")
      (node (ref "U2") (pin "E4") (pinfunction "IOL_1A_E4") (pintype "bidirectional"))
    )
    (net (code "239") (name "unconnected-(U2A-IOL_2A-PadF5)") (class "Default")
      (node (ref "U2") (pin "F5") (pinfunction "IOL_2A_F5") (pintype "bidirectional"))
    )
    (net (code "240") (name "unconnected-(U2A-IOL_2B-PadB1)") (class "Default")
      (node (ref "U2") (pin "B1") (pinfunction "IOL_2B_B1") (pintype "bidirectional"))
    )
    (net (code "241") (name "unconnected-(U2A-IOL_3A-PadC1)") (class "Default")
      (node (ref "U2") (pin "C1") (pinfunction "IOL_3A_C1") (pintype "bidirectional"))
    )
    (net (code "242") (name "unconnected-(U2A-IOL_4A-PadF4)") (class "Default")
      (node (ref "U2") (pin "F4") (pinfunction "IOL_4A_F4") (pintype "bidirectional"))
    )
    (net (code "243") (name "unconnected-(U2A-IOL_5A-PadG5)") (class "Default")
      (node (ref "U2") (pin "G5") (pinfunction "IOL_5A_G5") (pintype "bidirectional"))
    )
    (net (code "244") (name "unconnected-(U2A-IOL_5B-PadD1)") (class "Default")
      (node (ref "U2") (pin "D1") (pinfunction "IOL_5B_D1") (pintype "bidirectional"))
    )
    (net (code "245") (name "unconnected-(U2A-IOL_6A-PadG4)") (class "Default")
      (node (ref "U2") (pin "G4") (pinfunction "IOL_6A_G4") (pintype "bidirectional"))
    )
    (net (code "246") (name "unconnected-(U2A-IOL_7A-PadH5)") (class "Default")
      (node (ref "U2") (pin "H5") (pinfunction "IOL_7A_H5") (pintype "bidirectional"))
    )
    (net (code "247") (name "unconnected-(U2A-IOL_8B-PadF3)") (class "Default")
      (node (ref "U2") (pin "F3") (pinfunction "IOL_8B_F3") (pintype "bidirectional"))
    )
    (net (code "248") (name "unconnected-(U2A-IOL_9A-PadH3)") (class "Default")
      (node (ref "U2") (pin "H3") (pinfunction "IOL_9A_H3") (pintype "bidirectional"))
    )
    (net (code "249") (name "unconnected-(U2A-IOL_10A-PadH6)") (class "Default")
      (node (ref "U2") (pin "H6") (pinfunction "IOL_10A_H6") (pintype "bidirectional"))
    )
    (net (code "250") (name "unconnected-(U2A-IOL_11A-PadH4)") (class "Default")
      (node (ref "U2") (pin "H4") (pinfunction "IOL_11A_H4") (pintype "bidirectional"))
    )
    (net (code "251") (name "unconnected-(U2A-IOL_12A-PadJ4)") (class "Default")
      (node (ref "U2") (pin "J4") (pinfunction "IOL_12A_J4") (pintype "bidirectional"))
    )
    (net (code "252") (name "unconnected-(U2A-IOL_13A-PadJ5)") (class "Default")
      (node (ref "U2") (pin "J5") (pinfunction "IOL_13A_J5") (pintype "bidirectional"))
    )
    (net (code "253") (name "unconnected-(U2A-IOL_18A-PadK4)") (class "Default")
      (node (ref "U2") (pin "K4") (pinfunction "IOL_18A_K4") (pintype "bidirectional"))
    )
    (net (code "254") (name "unconnected-(U2A-IOL_20A-PadK5)") (class "Default")
      (node (ref "U2") (pin "K5") (pinfunction "IOL_20A_K5") (pintype "bidirectional"))
    )
    (net (code "255") (name "unconnected-(U2A-IOT_191-PadC9)") (class "Default")
      (node (ref "U2") (pin "C9") (pinfunction "IOT_191_C9") (pintype "bidirectional"))
    )
    (net (code "256") (name "unconnected-(U2A-IOT_192-PadE9)") (class "Default")
      (node (ref "U2") (pin "E9") (pinfunction "IOT_192_E9") (pintype "bidirectional"))
    )
    (net (code "257") (name "unconnected-(U2A-IOT_193-PadD9)") (class "Default")
      (node (ref "U2") (pin "D9") (pinfunction "IOT_193_D9") (pintype "bidirectional"))
    )
    (net (code "258") (name "unconnected-(U2A-IOT_196-PadF9)") (class "Default")
      (node (ref "U2") (pin "F9") (pinfunction "IOT_196_F9") (pintype "bidirectional"))
    )
    (net (code "259") (name "unconnected-(U2A-IOT_200-PadD8)") (class "Default")
      (node (ref "U2") (pin "D8") (pinfunction "IOT_200_D8") (pintype "bidirectional"))
    )
    (net (code "260") (name "unconnected-(U2A-IOT_206-PadC7)") (class "Default")
      (node (ref "U2") (pin "C7") (pinfunction "IOT_206_C7") (pintype "bidirectional"))
    )
    (net (code "261") (name "unconnected-(U2A-IOT_209-PadC6)") (class "Default")
      (node (ref "U2") (pin "C6") (pinfunction "IOT_209_C6") (pintype "bidirectional"))
    )
    (net (code "262") (name "unconnected-(U2A-IOT_210-PadD7)") (class "Default")
      (node (ref "U2") (pin "D7") (pinfunction "IOT_210_D7") (pintype "bidirectional"))
    )
    (net (code "263") (name "unconnected-(U2A-IOT_212-PadD6)") (class "Default")
      (node (ref "U2") (pin "D6") (pinfunction "IOT_212_D6") (pintype "bidirectional"))
    )
    (net (code "264") (name "unconnected-(U2A-IOT_215-PadE6)") (class "Default")
      (node (ref "U2") (pin "E6") (pinfunction "IOT_215_E6") (pintype "bidirectional"))
    )
    (net (code "265") (name "unconnected-(U2A-IOT_219-PadD5)") (class "Default")
      (node (ref "U2") (pin "D5") (pinfunction "IOT_219_D5") (pintype "bidirectional"))
    )
    (net (code "266") (name "unconnected-(U2A-IOT_221-PadC5)") (class "Default")
      (node (ref "U2") (pin "C5") (pinfunction "IOT_221_C5") (pintype "bidirectional"))
    )
    (net (code "267") (name "unconnected-(U2A-IOT_222-PadC4)") (class "Default")
      (node (ref "U2") (pin "C4") (pinfunction "IOT_222_C4") (pintype "bidirectional"))
    )
    (net (code "268") (name "unconnected-(U2A-IOT_224-PadD4)") (class "Default")
      (node (ref "U2") (pin "D4") (pinfunction "IOT_224_D4") (pintype "bidirectional"))
    )
    (net (code "269") (name "unconnected-(U2A-IOT_225-PadE5)") (class "Default")
      (node (ref "U2") (pin "E5") (pinfunction "IOT_225_E5") (pintype "bidirectional"))
    )
    (net (code "270") (name "unconnected-(U2B-IOB_52-PadN6)") (class "Default")
      (node (ref "U2") (pin "N6") (pinfunction "IOB_52_N6") (pintype "bidirectional"))
    )
    (net (code "271") (name "unconnected-(U2B-IOB_54-PadP4)") (class "Default")
      (node (ref "U2") (pin "P4") (pinfunction "IOB_54_P4") (pintype "bidirectional"))
    )
    (net (code "272") (name "unconnected-(U2B-IOB_56-PadN5)") (class "Default")
      (node (ref "U2") (pin "N5") (pinfunction "IOB_56_N5") (pintype "bidirectional"))
    )
    (net (code "273") (name "unconnected-(U2B-IOB_58-PadP5)") (class "Default")
      (node (ref "U2") (pin "P5") (pinfunction "IOB_58_P5") (pintype "bidirectional"))
    )
    (net (code "274") (name "unconnected-(U2B-IOB_63-PadR4)") (class "Default")
      (node (ref "U2") (pin "R4") (pinfunction "IOB_63_R4") (pintype "bidirectional"))
    )
    (net (code "275") (name "unconnected-(U2B-IOB_64-PadM7)") (class "Default")
      (node (ref "U2") (pin "M7") (pinfunction "IOB_64_M7") (pintype "bidirectional"))
    )
    (net (code "276") (name "unconnected-(U2B-IOB_66-PadN7)") (class "Default")
      (node (ref "U2") (pin "N7") (pinfunction "IOB_66_N7") (pintype "bidirectional"))
    )
    (net (code "277") (name "unconnected-(U2B-IOB_67-PadP6)") (class "Default")
      (node (ref "U2") (pin "P6") (pinfunction "IOB_67_P6") (pintype "bidirectional"))
    )
    (net (code "278") (name "unconnected-(U2B-IOB_68-PadM8)") (class "Default")
      (node (ref "U2") (pin "M8") (pinfunction "IOB_68_M8") (pintype "bidirectional"))
    )
    (net (code "279") (name "unconnected-(U2B-IOB_72-PadP8)") (class "Default")
      (node (ref "U2") (pin "P8") (pinfunction "IOB_72_P8") (pintype "bidirectional"))
    )
    (net (code "280") (name "unconnected-(U2B-IOB_74-PadL9)") (class "Default")
      (node (ref "U2") (pin "L9") (pinfunction "IOB_74_L9") (pintype "bidirectional"))
    )
    (net (code "281") (name "unconnected-(U2B-IOB_77-PadP7)") (class "Default")
      (node (ref "U2") (pin "P7") (pinfunction "IOB_77_P7") (pintype "bidirectional"))
    )
    (net (code "282") (name "unconnected-(U2B-IOB_78-PadN9)") (class "Default")
      (node (ref "U2") (pin "N9") (pinfunction "IOB_78_N9") (pintype "bidirectional"))
    )
    (net (code "283") (name "unconnected-(U2B-IOB_79-PadT9)") (class "Default")
      (node (ref "U2") (pin "T9") (pinfunction "IOB_79_T9") (pintype "bidirectional"))
    )
    (net (code "284") (name "unconnected-(U2B-IOB_80-PadM9)") (class "Default")
      (node (ref "U2") (pin "M9") (pinfunction "IOB_80_M9") (pintype "bidirectional"))
    )
    (net (code "285") (name "unconnected-(U2B-IOB_83-PadP9)") (class "Default")
      (node (ref "U2") (pin "P9") (pinfunction "IOB_83_P9") (pintype "bidirectional"))
    )
    (net (code "286") (name "unconnected-(U2B-IOL_17A-PadL4)") (class "Default")
      (node (ref "U2") (pin "L4") (pinfunction "IOL_17A_L4") (pintype "bidirectional"))
    )
    (net (code "287") (name "unconnected-(U2B-IOL_19A-PadL6)") (class "Default")
      (node (ref "U2") (pin "L6") (pinfunction "IOL_19A_L6") (pintype "bidirectional"))
    )
    (net (code "288") (name "unconnected-(U2B-IOL_21A-PadL7)") (class "Default")
      (node (ref "U2") (pin "L7") (pinfunction "IOL_21A_L7") (pintype "bidirectional"))
    )
    (net (code "289") (name "unconnected-(U2B-IOL_22A-PadM6)") (class "Default")
      (node (ref "U2") (pin "M6") (pinfunction "IOL_22A_M6") (pintype "bidirectional"))
    )
    (net (code "290") (name "unconnected-(U2B-IOL_22B-PadM3)") (class "Default")
      (node (ref "U2") (pin "M3") (pinfunction "IOL_22B_M3") (pintype "bidirectional"))
    )
    (net (code "291") (name "unconnected-(U2B-IOL_23A-PadL5)") (class "Default")
      (node (ref "U2") (pin "L5") (pinfunction "IOL_23A_L5") (pintype "bidirectional"))
    )
    (net (code "292") (name "unconnected-(U2B-IOL_24B-PadM4)") (class "Default")
      (node (ref "U2") (pin "M4") (pinfunction "IOL_24B_M4") (pintype "bidirectional"))
    )
    (net (code "293") (name "unconnected-(U2B-IOL_25B-PadM5)") (class "Default")
      (node (ref "U2") (pin "M5") (pinfunction "IOL_25B_M5") (pintype "bidirectional"))
    )
    (net (code "294") (name "unconnected-(U2B-IOL_26B-PadN4)") (class "Default")
      (node (ref "U2") (pin "N4") (pinfunction "IOL_26B_N4") (pintype "bidirectional"))
    )
    (net (code "295") (name "unconnected-(U2B-IOT_170-PadD13)") (class "Default")
      (node (ref "U2") (pin "D13") (pinfunction "IOT_170_D13") (pintype "bidirectional"))
    )
    (net (code "296") (name "unconnected-(U2B-IOT_172-PadC12)") (class "Default")
      (node (ref "U2") (pin "C12") (pinfunction "IOT_172_C12") (pintype "bidirectional"))
    )
    (net (code "297") (name "unconnected-(U2B-IOT_174-PadC13)") (class "Default")
      (node (ref "U2") (pin "C13") (pinfunction "IOT_174_C13") (pintype "bidirectional"))
    )
    (net (code "298") (name "unconnected-(U2B-IOT_178-PadB13)") (class "Default")
      (node (ref "U2") (pin "B13") (pinfunction "IOT_178_B13") (pintype "bidirectional"))
    )
    (net (code "299") (name "unconnected-(U2B-IOT_180-PadC11)") (class "Default")
      (node (ref "U2") (pin "C11") (pinfunction "IOT_180_C11") (pintype "bidirectional"))
    )
    (net (code "300") (name "unconnected-(U2B-IOT_181-PadD11)") (class "Default")
      (node (ref "U2") (pin "D11") (pinfunction "IOT_181_D11") (pintype "bidirectional"))
    )
    (net (code "301") (name "unconnected-(U2B-IOT_182-PadB12)") (class "Default")
      (node (ref "U2") (pin "B12") (pinfunction "IOT_182_B12") (pintype "bidirectional"))
    )
    (net (code "302") (name "unconnected-(U2B-IOT_183-PadB10)") (class "Default")
      (node (ref "U2") (pin "B10") (pinfunction "IOT_183_B10") (pintype "bidirectional"))
    )
    (net (code "303") (name "unconnected-(U2B-IOT_185-PadC10)") (class "Default")
      (node (ref "U2") (pin "C10") (pinfunction "IOT_185_C10") (pintype "bidirectional"))
    )
    (net (code "304") (name "unconnected-(U2B-IOT_190-PadD10)") (class "Default")
      (node (ref "U2") (pin "D10") (pinfunction "IOT_190_D10") (pintype "bidirectional"))
    )
    (net (code "305") (name "unconnected-(U2C-IOB_85-PadL10)") (class "Default")
      (node (ref "U2") (pin "L10") (pinfunction "IOB_85_L10") (pintype "bidirectional"))
    )
    (net (code "306") (name "unconnected-(U2C-IOB_87-PadN10)") (class "Default")
      (node (ref "U2") (pin "N10") (pinfunction "IOB_87_N10") (pintype "bidirectional"))
    )
    (net (code "307") (name "unconnected-(U2C-IOB_88-PadT10)") (class "Default")
      (node (ref "U2") (pin "T10") (pinfunction "IOB_88_T10") (pintype "bidirectional"))
    )
    (net (code "308") (name "unconnected-(U2C-IOB_89-PadT11)") (class "Default")
      (node (ref "U2") (pin "T11") (pinfunction "IOB_89_T11") (pintype "bidirectional"))
    )
    (net (code "309") (name "unconnected-(U2C-IOB_93-PadM11)") (class "Default")
      (node (ref "U2") (pin "M11") (pinfunction "IOB_93_M11") (pintype "bidirectional"))
    )
    (net (code "310") (name "unconnected-(U2C-IOB_94-PadT13)") (class "Default")
      (node (ref "U2") (pin "T13") (pinfunction "IOB_94_T13") (pintype "bidirectional"))
    )
    (net (code "311") (name "unconnected-(U2C-IOB_99-PadL11)") (class "Default")
      (node (ref "U2") (pin "L11") (pinfunction "IOB_99_L11") (pintype "bidirectional"))
    )
    (net (code "312") (name "unconnected-(U2C-IOB_101-PadM12)") (class "Default")
      (node (ref "U2") (pin "M12") (pinfunction "IOB_101_M12") (pintype "bidirectional"))
    )
    (net (code "313") (name "unconnected-(U2C-IOB_103_CBSEL0-PadK11)") (class "Default")
      (node (ref "U2") (pin "K11") (pinfunction "IOB_103_CBSEL0_K11") (pintype "bidirectional"))
    )
    (net (code "314") (name "unconnected-(U2C-IOB_105_SDO-PadP12)") (class "Default")
      (node (ref "U2") (pin "P12") (pinfunction "IOB_105_SDO_P12") (pintype "bidirectional"))
    )
    (net (code "315") (name "unconnected-(U2C-IOR_114-PadM13)") (class "Default")
      (node (ref "U2") (pin "M13") (pinfunction "IOR_114_M13") (pintype "bidirectional"))
    )
    (net (code "316") (name "unconnected-(U2C-IOR_115-PadM14)") (class "Default")
      (node (ref "U2") (pin "M14") (pinfunction "IOR_115_M14") (pintype "bidirectional"))
    )
    (net (code "317") (name "unconnected-(U2C-IOR_116-PadL12)") (class "Default")
      (node (ref "U2") (pin "L12") (pinfunction "IOR_116_L12") (pintype "bidirectional"))
    )
    (net (code "318") (name "unconnected-(U2C-IOR_118-PadL13)") (class "Default")
      (node (ref "U2") (pin "L13") (pinfunction "IOR_118_L13") (pintype "bidirectional"))
    )
    (net (code "319") (name "unconnected-(U2C-IOR_120-PadK12)") (class "Default")
      (node (ref "U2") (pin "K12") (pinfunction "IOR_120_K12") (pintype "bidirectional"))
    )
    (net (code "320") (name "unconnected-(U2C-IOR_122-PadJ10)") (class "Default")
      (node (ref "U2") (pin "J10") (pinfunction "IOR_122_J10") (pintype "bidirectional"))
    )
    (net (code "321") (name "unconnected-(U2C-IOR_126-PadJ11)") (class "Default")
      (node (ref "U2") (pin "J11") (pinfunction "IOR_126_J11") (pintype "bidirectional"))
    )
    (net (code "322") (name "unconnected-(U2C-IOR_128-PadK13)") (class "Default")
      (node (ref "U2") (pin "K13") (pinfunction "IOR_128_K13") (pintype "bidirectional"))
    )
    (net (code "323") (name "unconnected-(U2C-IOR_136-PadJ12)") (class "Default")
      (node (ref "U2") (pin "J12") (pinfunction "IOR_136_J12") (pintype "bidirectional"))
    )
    (net (code "324") (name "unconnected-(U2C-IOR_137-PadJ13)") (class "Default")
      (node (ref "U2") (pin "J13") (pinfunction "IOR_137_J13") (pintype "bidirectional"))
    )
    (net (code "325") (name "unconnected-(U2C-IOR_139-PadH13)") (class "Default")
      (node (ref "U2") (pin "H13") (pinfunction "IOR_139_H13") (pintype "bidirectional"))
    )
    (net (code "326") (name "unconnected-(U2C-IOR_144-PadH12)") (class "Default")
      (node (ref "U2") (pin "H12") (pinfunction "IOR_144_H12") (pintype "bidirectional"))
    )
    (net (code "327") (name "unconnected-(U2C-IOR_146-PadG10)") (class "Default")
      (node (ref "U2") (pin "G10") (pinfunction "IOR_146_G10") (pintype "bidirectional"))
    )
    (net (code "328") (name "unconnected-(U2C-IOR_148-PadG11)") (class "Default")
      (node (ref "U2") (pin "G11") (pinfunction "IOR_148_G11") (pintype "bidirectional"))
    )
    (net (code "329") (name "unconnected-(U2C-IOR_152-PadG13)") (class "Default")
      (node (ref "U2") (pin "G13") (pinfunction "IOR_152_G13") (pintype "bidirectional"))
    )
    (net (code "330") (name "unconnected-(U2C-IOR_154-PadG12)") (class "Default")
      (node (ref "U2") (pin "G12") (pinfunction "IOR_154_G12") (pintype "bidirectional"))
    )
    (net (code "331") (name "unconnected-(U2C-IOR_156-PadF12)") (class "Default")
      (node (ref "U2") (pin "F12") (pinfunction "IOR_156_F12") (pintype "bidirectional"))
    )
    (net (code "332") (name "unconnected-(U2C-IOR_158-PadF11)") (class "Default")
      (node (ref "U2") (pin "F11") (pinfunction "IOR_158_F11") (pintype "bidirectional"))
    )
    (net (code "333") (name "unconnected-(U2C-IOR_162-PadF13)") (class "Default")
      (node (ref "U2") (pin "F13") (pinfunction "IOR_162_F13") (pintype "bidirectional"))
    )
    (net (code "334") (name "unconnected-(U2C-IOR_166-PadE13)") (class "Default")
      (node (ref "U2") (pin "E13") (pinfunction "IOR_166_E13") (pintype "bidirectional"))
    )
    (net (code "335") (name "unconnected-(U2C-IOT_173-PadE11)") (class "Default")
      (node (ref "U2") (pin "E11") (pinfunction "IOT_173_E11") (pintype "bidirectional"))
    )
    (net (code "336") (name "unconnected-(U2C-IOT_179-PadE10)") (class "Default")
      (node (ref "U2") (pin "E10") (pinfunction "IOT_179_E10") (pintype "bidirectional"))
    )
    (net (code "337") (name "unconnected-(U2C-NC-PadN14)") (class "Default")
      (node (ref "U2") (pin "N14") (pinfunction "NC_N14") (pintype "no_connect"))
    )
    (net (code "338") (name "unconnected-(U8-CBUS0-Pad12)") (class "Default")
      (node (ref "U8") (pin "12") (pinfunction "CBUS0_12") (pintype "bidirectional"))
    )
    (net (code "339") (name "unconnected-(U8-CBUS1-Pad11)") (class "Default")
      (node (ref "U8") (pin "11") (pinfunction "CBUS1_11") (pintype "bidirectional"))
    )
    (net (code "340") (name "unconnected-(U8-CBUS2-Pad5)") (class "Default")
      (node (ref "U8") (pin "5") (pinfunction "CBUS2_5") (pintype "bidirectional"))
    )
    (net (code "341") (name "unconnected-(U8-CBUS3-Pad14)") (class "Default")
      (node (ref "U8") (pin "14") (pinfunction "CBUS3_14") (pintype "bidirectional"))
    )
    (net (code "342") (name "unconnected-(U8-~{CTS}-Pad4)") (class "Default")
      (node (ref "U8") (pin "4") (pinfunction "~{CTS}_4") (pintype "input"))
    )
    (net (code "343") (name "unconnected-(U8-~{RTS}-Pad16)") (class "Default")
      (node (ref "U8") (pin "16") (pinfunction "~{RTS}_16") (pintype "output"))
    )
    (net (code "344") (name "unconnected-(U9A-PA6{slash}SPI1_MISO{slash}TIM8_BKIN{slash}TIM13_CH1{slash}DCMI_PIXCLK{slash}TIM3_CH1{slash}TIM1_BKIN{slash}EVENTOUT{slash}ADC12_IN6-Pad42)") (class "Default")
      (node (ref "U9") (pin "42") (pinfunction "PA6/SPI1_MISO/TIM8_BKIN/TIM13_CH1/DCMI_PIXCLK/TIM3_CH1/TIM1_BKIN/EVENTOUT/ADC12_IN6_42") (pintype "passive"))
    )
    (net (code "345") (name "unconnected-(U9A-PA8{slash}MC01{slash}USART1_CK{slash}TIM1_CH1{slash}I2C3_SCL{slash}OTG_FS_SOF{slash}EVENTOUT-Pad100)") (class "Default")
      (node (ref "U9") (pin "100") (pinfunction "PA8/MC01/USART1_CK/TIM1_CH1/I2C3_SCL/OTG_FS_SOF/EVENTOUT_100") (pintype "passive"))
    )
    (net (code "346") (name "unconnected-(U9A-PA9{slash}USART1_TX{slash}TIM1_CH2{slash}I2C3_SMBA{slash}DCMI_D0{slash}EVENTOUT-Pad101)") (class "Default")
      (node (ref "U9") (pin "101") (pinfunction "PA9/USART1_TX/TIM1_CH2/I2C3_SMBA/DCMI_D0/EVENTOUT_101") (pintype "passive"))
    )
    (net (code "347") (name "unconnected-(U9A-PA10{slash}USART1_RX{slash}TIM1_CH{slash}OTG_FS_ID{slash}DCMI_D1{slash}EVENTOUT-Pad102)") (class "Default")
      (node (ref "U9") (pin "102") (pinfunction "PA10/USART1_RX/TIM1_CH/OTG_FS_ID/DCMI_D1/EVENTOUT_102") (pintype "passive"))
    )
    (net (code "348") (name "unconnected-(U9A-PA11{slash}USART1_CTS{slash}CAN1_RX{slash}TIM1_CH4{slash}OTG_FS_DM{slash}EVENTOUT-Pad103)") (class "Default")
      (node (ref "U9") (pin "103") (pinfunction "PA11/USART1_CTS/CAN1_RX/TIM1_CH4/OTG_FS_DM/EVENTOUT_103") (pintype "passive"))
    )
    (net (code "349") (name "unconnected-(U9A-PA12{slash}USART1_RTS{slash}CAN1_TX{slash}TIM1_ETR{slash}OTG_FS_DP{slash}EVENTOUT-Pad104)") (class "Default")
      (node (ref "U9") (pin "104") (pinfunction "PA12/USART1_RTS/CAN1_TX/TIM1_ETR/OTG_FS_DP/EVENTOUT_104") (pintype "passive"))
    )
    (net (code "350") (name "unconnected-(U9A-PA15{slash}JTDI{slash}SPI3_NSS{slash}I2S3_WS{slash}TIM2_CH1_ETR{slash}SPI1_NSS{slash}EVENTOUT-Pad110)") (class "Default")
      (node (ref "U9") (pin "110") (pinfunction "PA15/JTDI/SPI3_NSS/I2S3_WS/TIM2_CH1_ETR/SPI1_NSS/EVENTOUT_110") (pintype "passive"))
    )
    (net (code "351") (name "unconnected-(U9A-PB0{slash}TIM3_CH3{slash}TIM8_CH2N{slash}OTG_HS_ULPI_D1{slash}ETH_MII_RXD2{slash}TIM1_CH2N{slash}EVENTOUT{slash}ADC12_IN8-Pad46)") (class "Default")
      (node (ref "U9") (pin "46") (pinfunction "PB0/TIM3_CH3/TIM8_CH2N/OTG_HS_ULPI_D1/ETH_MII_RXD2/TIM1_CH2N/EVENTOUT/ADC12_IN8_46") (pintype "passive"))
    )
    (net (code "352") (name "unconnected-(U9A-PB1{slash}TIM3_CH4{slash}TIM8_CH3N{slash}OTG_HS_ULPI_D2{slash}ETH_MII_RXD3{slash}TIM1_CH3N{slash}EVENTOUT{slash}ADC12_IN9-Pad47)") (class "Default")
      (node (ref "U9") (pin "47") (pinfunction "PB1/TIM3_CH4/TIM8_CH3N/OTG_HS_ULPI_D2/ETH_MII_RXD3/TIM1_CH3N/EVENTOUT/ADC12_IN9_47") (pintype "passive"))
    )
    (net (code "353") (name "unconnected-(U9A-PB2-BOOT1{slash}EVENTOUT-Pad48)") (class "Default")
      (node (ref "U9") (pin "48") (pinfunction "PB2-BOOT1/EVENTOUT_48") (pintype "passive"))
    )
    (net (code "354") (name "unconnected-(U9A-PB4{slash}NJTRST{slash}SPI3_MISO{slash}TIM3_CH1{slash}SPI1_MISO{slash}I2S3EXT_SD{slash}EVENTOUT-Pad134)") (class "Default")
      (node (ref "U9") (pin "134") (pinfunction "PB4/NJTRST/SPI3_MISO/TIM3_CH1/SPI1_MISO/I2S3EXT_SD/EVENTOUT_134") (pintype "passive"))
    )
    (net (code "355") (name "unconnected-(U9A-PB5{slash}I2C1_SMBA{slash}CAN2_RX{slash}OTG_HS_ULPI_D7{slash}ETH_PPS_OUT{slash}TIM3_CH2{slash}SPI1_MOSI{slash}SPI3_MOSI{slash}DCMI_D10{slash}I2S3_SD{slash}EVENTOUT-Pad135)") (class "Default")
      (node (ref "U9") (pin "135") (pinfunction "PB5/I2C1_SMBA/CAN2_RX/OTG_HS_ULPI_D7/ETH_PPS_OUT/TIM3_CH2/SPI1_MOSI/SPI3_MOSI/DCMI_D10/I2S3_SD/EVENTOUT_135") (pintype "passive"))
    )
    (net (code "356") (name "unconnected-(U9A-PB6{slash}I2C1_SCL{slash}TIM4_CH1{slash}CAN2_TX{slash}DCMI_D5{slash}USART1_TX{slash}EVENTOUT-Pad136)") (class "Default")
      (node (ref "U9") (pin "136") (pinfunction "PB6/I2C1_SCL/TIM4_CH1/CAN2_TX/DCMI_D5/USART1_TX/EVENTOUT_136") (pintype "passive"))
    )
    (net (code "357") (name "unconnected-(U9A-PB8{slash}TIM4_CH3{slash}SDIO_D4{slash}TIM10_CH1{slash}DCMI_D6{slash}ETH_MII_TXD3{slash}I2C1_SCL{slash}CAN1_RX{slash}EVENTOUT-Pad139)") (class "Default")
      (node (ref "U9") (pin "139") (pinfunction "PB8/TIM4_CH3/SDIO_D4/TIM10_CH1/DCMI_D6/ETH_MII_TXD3/I2C1_SCL/CAN1_RX/EVENTOUT_139") (pintype "passive"))
    )
    (net (code "358") (name "unconnected-(U9A-PB9{slash}SPI2_NSS{slash}I2S2_WS{slash}TIM4_CH4{slash}TIM11_CH1{slash}SDIO_D5{slash}DCMI_D7{slash}I2C1_SDA{slash}CAN1_TX{slash}EVENTOUT-Pad140)") (class "Default")
      (node (ref "U9") (pin "140") (pinfunction "PB9/SPI2_NSS/I2S2_WS/TIM4_CH4/TIM11_CH1/SDIO_D5/DCMI_D7/I2C1_SDA/CAN1_TX/EVENTOUT_140") (pintype "passive"))
    )
    (net (code "359") (name "unconnected-(U9A-PC0{slash}OTG_HS_ULPI_STP{slash}EVENTOUT{slash}ADC123_IN10-Pad26)") (class "Default")
      (node (ref "U9") (pin "26") (pinfunction "PC0/OTG_HS_ULPI_STP/EVENTOUT/ADC123_IN10_26") (pintype "passive"))
    )
    (net (code "360") (name "unconnected-(U9A-PC13_DNU_{slash}EVENTOUT{slash}RTC_AF2{slash}-Pad7)") (class "Default")
      (node (ref "U9") (pin "7") (pinfunction "PC13_DNU_/EVENTOUT/RTC_AF2/_7") (pintype "passive"))
    )
    (net (code "361") (name "unconnected-(U9A-PC14-OSC32_IN_DNU_{slash}EVENTOUT-Pad8)") (class "Default")
      (node (ref "U9") (pin "8") (pinfunction "PC14-OSC32_IN_DNU_/EVENTOUT_8") (pintype "passive"))
    )
    (net (code "362") (name "unconnected-(U9A-PC15-OSC32_OUT_DNU_{slash}EVENTOUT-Pad9)") (class "Default")
      (node (ref "U9") (pin "9") (pinfunction "PC15-OSC32_OUT_DNU_/EVENTOUT_9") (pintype "passive"))
    )
    (net (code "363") (name "unconnected-(U9B-PD2{slash}TIM3_ETR{slash}UART5_RX{slash}SDIO_CMD{slash}DCMI_D11{slash}EVENTOUT-Pad116)") (class "Default")
      (node (ref "U9") (pin "116") (pinfunction "PD2/TIM3_ETR/UART5_RX/SDIO_CMD/DCMI_D11/EVENTOUT_116") (pintype "passive"))
    )
    (net (code "364") (name "unconnected-(U9B-PD11{slash}FSMC_CLE{slash}FSMC_A16{slash}USART3_CTS{slash}EVENTOUT-Pad80)") (class "Default")
      (node (ref "U9") (pin "80") (pinfunction "PD11/FSMC_CLE/FSMC_A16/USART3_CTS/EVENTOUT_80") (pintype "passive"))
    )
    (net (code "365") (name "unconnected-(U9B-PD12{slash}FSMC_ALE{slash}FSMC_A17{slash}TIM4_CH1{slash}USART3_RTS{slash}EVENTOUT-Pad81)") (class "Default")
      (node (ref "U9") (pin "81") (pinfunction "PD12/FSMC_ALE/FSMC_A17/TIM4_CH1/USART3_RTS/EVENTOUT_81") (pintype "passive"))
    )
    (net (code "366") (name "unconnected-(U9B-PD13{slash}FSMC_A18{slash}TIM4_CH2{slash}EVENTOUT-Pad82)") (class "Default")
      (node (ref "U9") (pin "82") (pinfunction "PD13/FSMC_A18/TIM4_CH2/EVENTOUT_82") (pintype "passive"))
    )
    (net (code "367") (name "unconnected-(U9B-PE0{slash}TIM4_ETR{slash}FSMC_NBLO{slash}DCMI_D2{slash}EVENTOUT-Pad141)") (class "Default")
      (node (ref "U9") (pin "141") (pinfunction "PE0/TIM4_ETR/FSMC_NBLO/DCMI_D2/EVENTOUT_141") (pintype "passive"))
    )
    (net (code "368") (name "unconnected-(U9B-PE1{slash}FSMC_NBL1{slash}DMI_D3{slash}EVENTOUT-Pad142)") (class "Default")
      (node (ref "U9") (pin "142") (pinfunction "PE1/FSMC_NBL1/DMI_D3/EVENTOUT_142") (pintype "passive"))
    )
    (net (code "369") (name "unconnected-(U9B-PE6{slash}TRACED3{slash}FSMC_A22{slash}TIM9_CH2{slash}DCMI_D7{slash}EVENTOUT-Pad5)") (class "Default")
      (node (ref "U9") (pin "5") (pinfunction "PE6/TRACED3/FSMC_A22/TIM9_CH2/DCMI_D7/EVENTOUT_5") (pintype "passive"))
    )
    (net (code "370") (name "unconnected-(U9B-PF6{slash}TIM10_CH1{slash}FSMC_NIORD{slash}EVENTOUT{slash}ADC3_IN4-Pad18)") (class "Default")
      (node (ref "U9") (pin "18") (pinfunction "PF6/TIM10_CH1/FSMC_NIORD/EVENTOUT/ADC3_IN4_18") (pintype "passive"))
    )
    (net (code "371") (name "unconnected-(U9B-PF7{slash}TIM11_CH1{slash}FSMC_NREG{slash}EVENTOUT{slash}ADC3_IN5-Pad19)") (class "Default")
      (node (ref "U9") (pin "19") (pinfunction "PF7/TIM11_CH1/FSMC_NREG/EVENTOUT/ADC3_IN5_19") (pintype "passive"))
    )
    (net (code "372") (name "unconnected-(U9B-PF8{slash}TIM13_CH1{slash}FSMC_NIOWR{slash}EVENTOUT{slash}ADC3_IN6-Pad20)") (class "Default")
      (node (ref "U9") (pin "20") (pinfunction "PF8/TIM13_CH1/FSMC_NIOWR/EVENTOUT/ADC3_IN6_20") (pintype "passive"))
    )
    (net (code "373") (name "unconnected-(U9B-PF9{slash}TIM14_CH1{slash}FSMC_CD{slash}EVENTOUT{slash}ADC3_IN7-Pad21)") (class "Default")
      (node (ref "U9") (pin "21") (pinfunction "PF9/TIM14_CH1/FSMC_CD/EVENTOUT/ADC3_IN7_21") (pintype "passive"))
    )
    (net (code "374") (name "unconnected-(U9B-PF10{slash}FSMC_INTR{slash}EVENTOUT{slash}ADC3_IN8-Pad22)") (class "Default")
      (node (ref "U9") (pin "22") (pinfunction "PF10/FSMC_INTR/EVENTOUT/ADC3_IN8_22") (pintype "passive"))
    )
    (net (code "375") (name "unconnected-(U9B-PF11{slash}DCMI_12{slash}EVENTOUT-Pad49)") (class "Default")
      (node (ref "U9") (pin "49") (pinfunction "PF11/DCMI_12/EVENTOUT_49") (pintype "passive"))
    )
    (net (code "376") (name "unconnected-(U9B-PG9{slash}USART6_RX{slash}FSMC_NE2{slash}FSMC_NCE3{slash}EVENTOUT-Pad124)") (class "Default")
      (node (ref "U9") (pin "124") (pinfunction "PG9/USART6_RX/FSMC_NE2/FSMC_NCE3/EVENTOUT_124") (pintype "passive"))
    )
    (net (code "377") (name "unconnected-(U9B-PG10{slash}FSMC_NCE4_1{slash}FSMC_NE3{slash}EVENTOUT-Pad125)") (class "Default")
      (node (ref "U9") (pin "125") (pinfunction "PG10/FSMC_NCE4_1/FSMC_NE3/EVENTOUT_125") (pintype "passive"))
    )
    (net (code "378") (name "unconnected-(U9B-PG15{slash}USART6_CTS{slash}DCMI_D13{slash}EVENTOUT-Pad132)") (class "Default")
      (node (ref "U9") (pin "132") (pinfunction "PG15/USART6_CTS/DCMI_D13/EVENTOUT_132") (pintype "passive"))
    )
    (net (code "379") (name "unconnected-(U9C-VBAT-Pad6)") (class "Default")
      (node (ref "U9") (pin "6") (pinfunction "VBAT_6") (pintype "passive"))
    )
    (net (code "380") (name "~{RESET}") (class "Default")
      (node (ref "JP1") (pin "5") (pinfunction "5_5") (pintype "passive"))
      (node (ref "R56") (pin "2") (pinfunction "2_2") (pintype "passive"))
      (node (ref "SW3") (pin "2") (pinfunction "2_2") (pintype "passive"))
      (node (ref "SW3") (pin "3") (pinfunction "3_3") (pintype "passive"))
      (node (ref "U18") (pin "15") (pinfunction "~{RST}_15") (pintype "passive"))
      (node (ref "U9") (pin "25") (pinfunction "NRST_25") (pintype "passive"))
      (node (ref "Z3") (pin "2") (pinfunction "I/O_2") (pintype "passive"))
      (node (ref "Z3") (pin "3") (pinfunction "I/O_3") (pintype "passive"))
    )
    (net (code "381") (name "~{RUN_BOOTL}") (class "Default")
      (node (ref "JP3") (pin "1") (pinfunction "1_1") (pintype "passive"))
      (node (ref "R63") (pin "2") (pinfunction "2_2") (pintype "passive"))
      (node (ref "U9") (pin "4") (pinfunction "PE5/TRACED2/FSMC_A21/TIM9_CH1/DCMI_D6/EVENTOUT_4") (pintype "passive"))
    )
  )
)
